# TRISTATE_BANK.net
KiCad netlist of a schematic drawn in Altium Designer
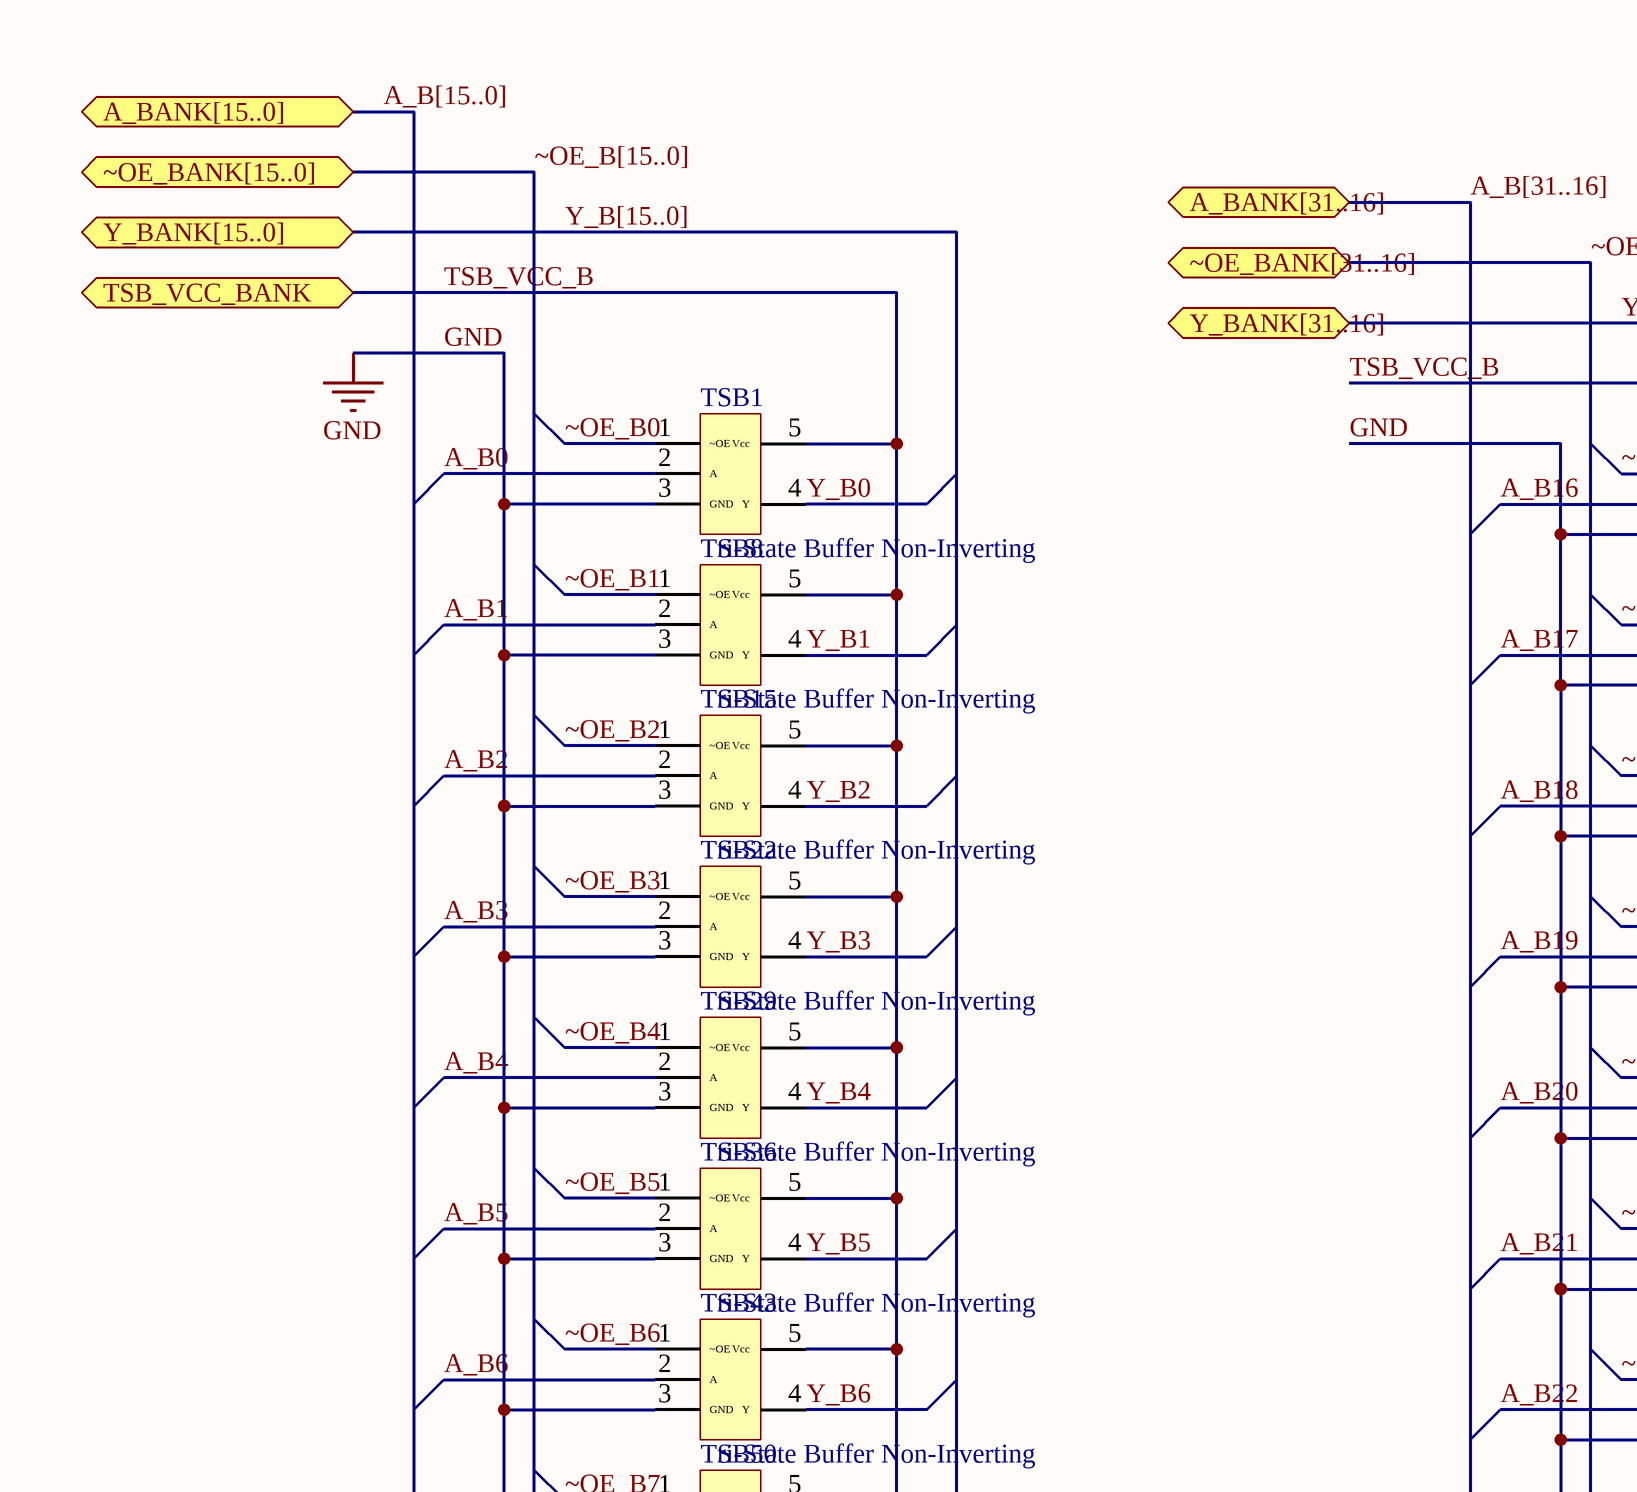
[diagram p0: TRISTATE_BANK.SchDoc, top column 1 of 5]
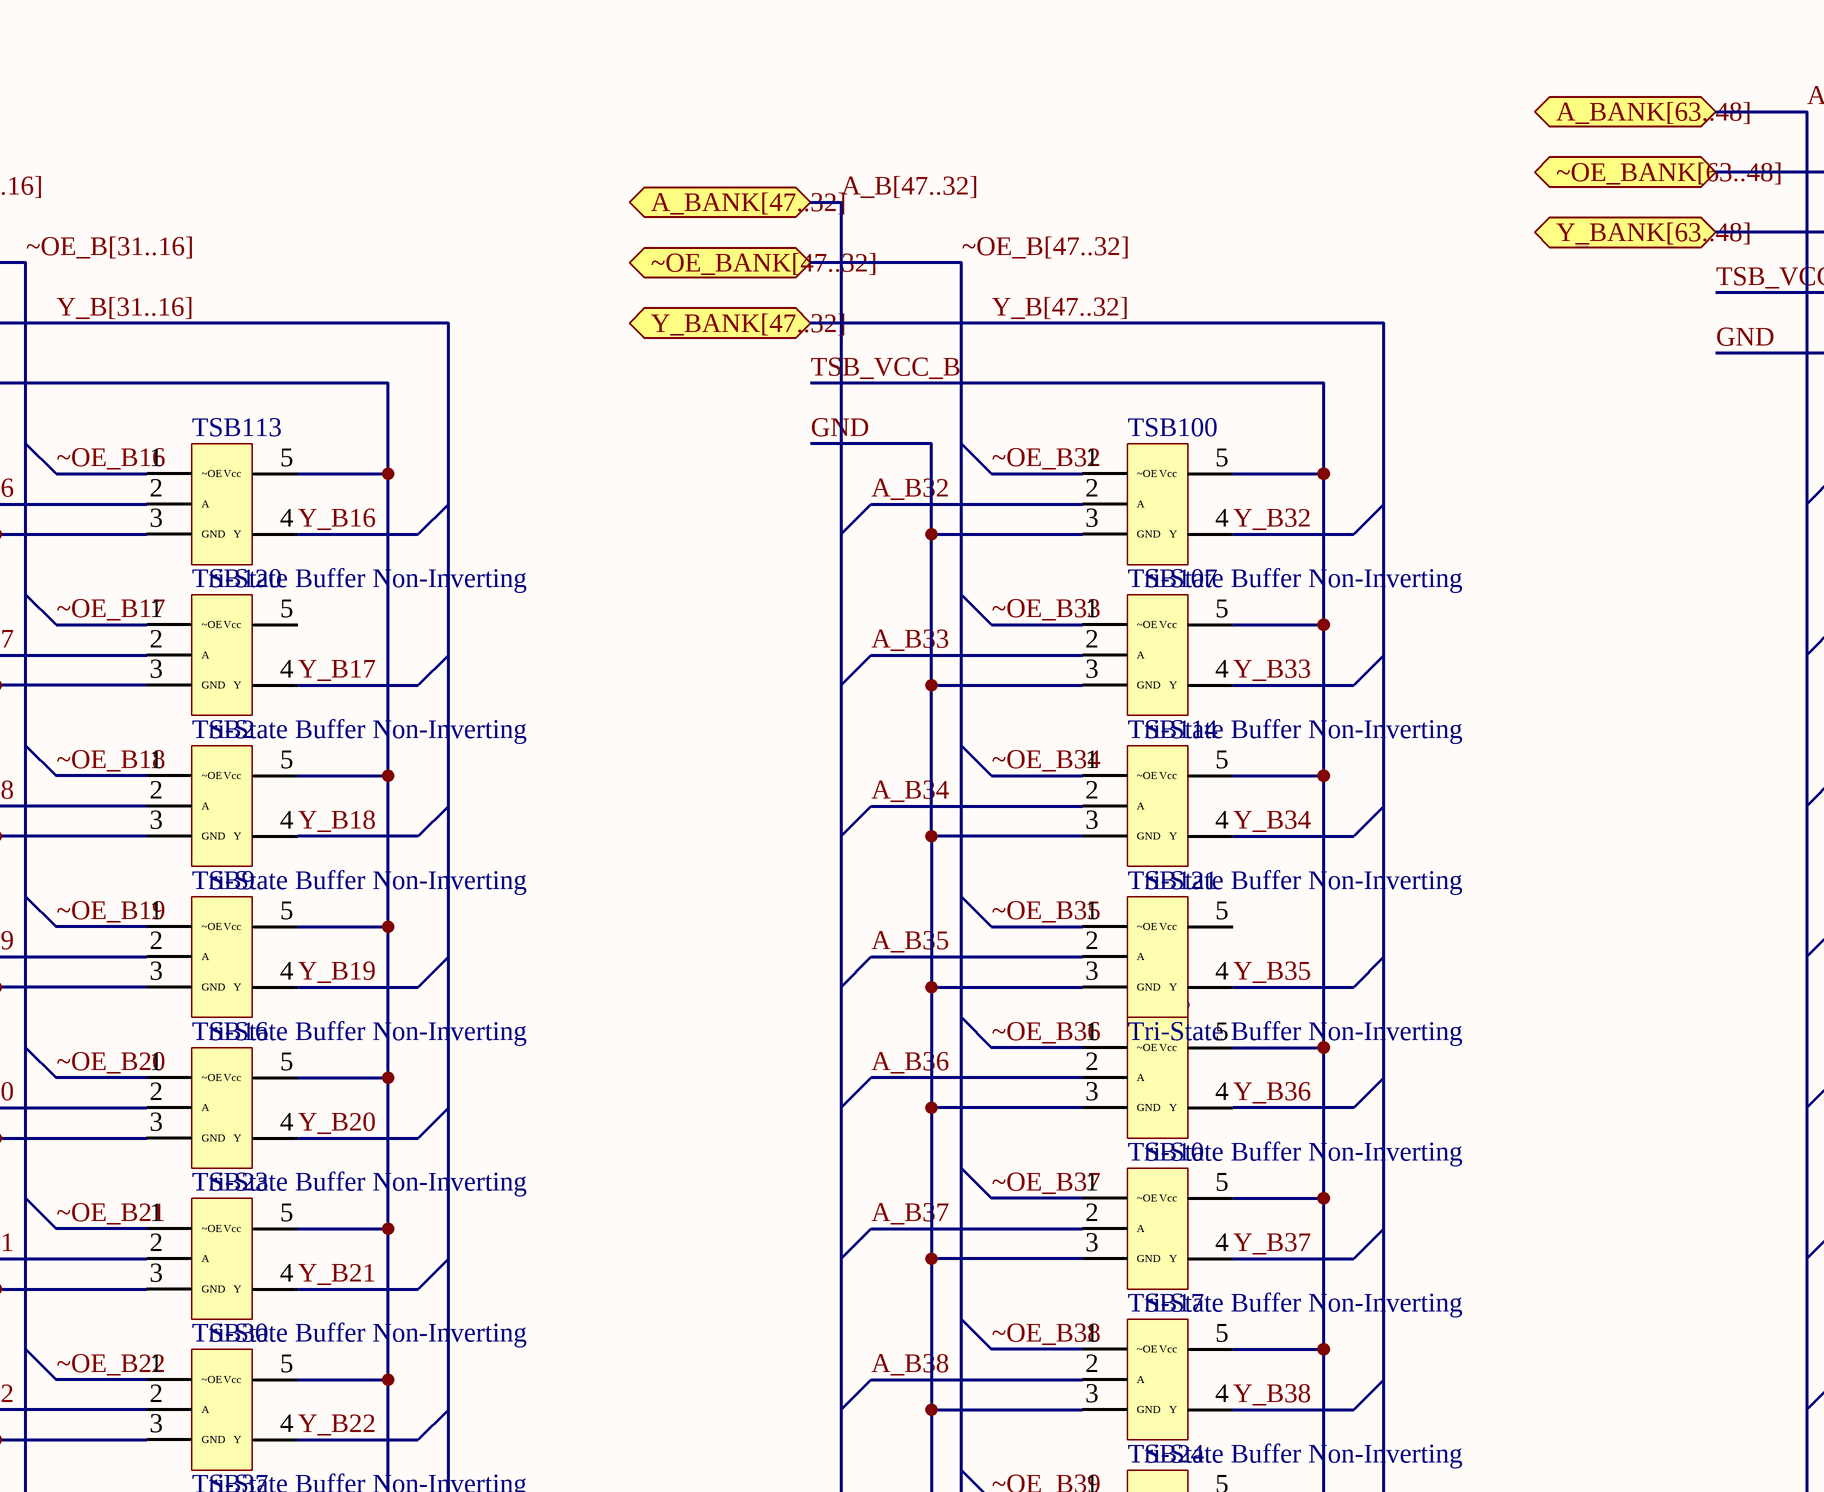
[diagram p1: TRISTATE_BANK.SchDoc, top column 2 of 5]
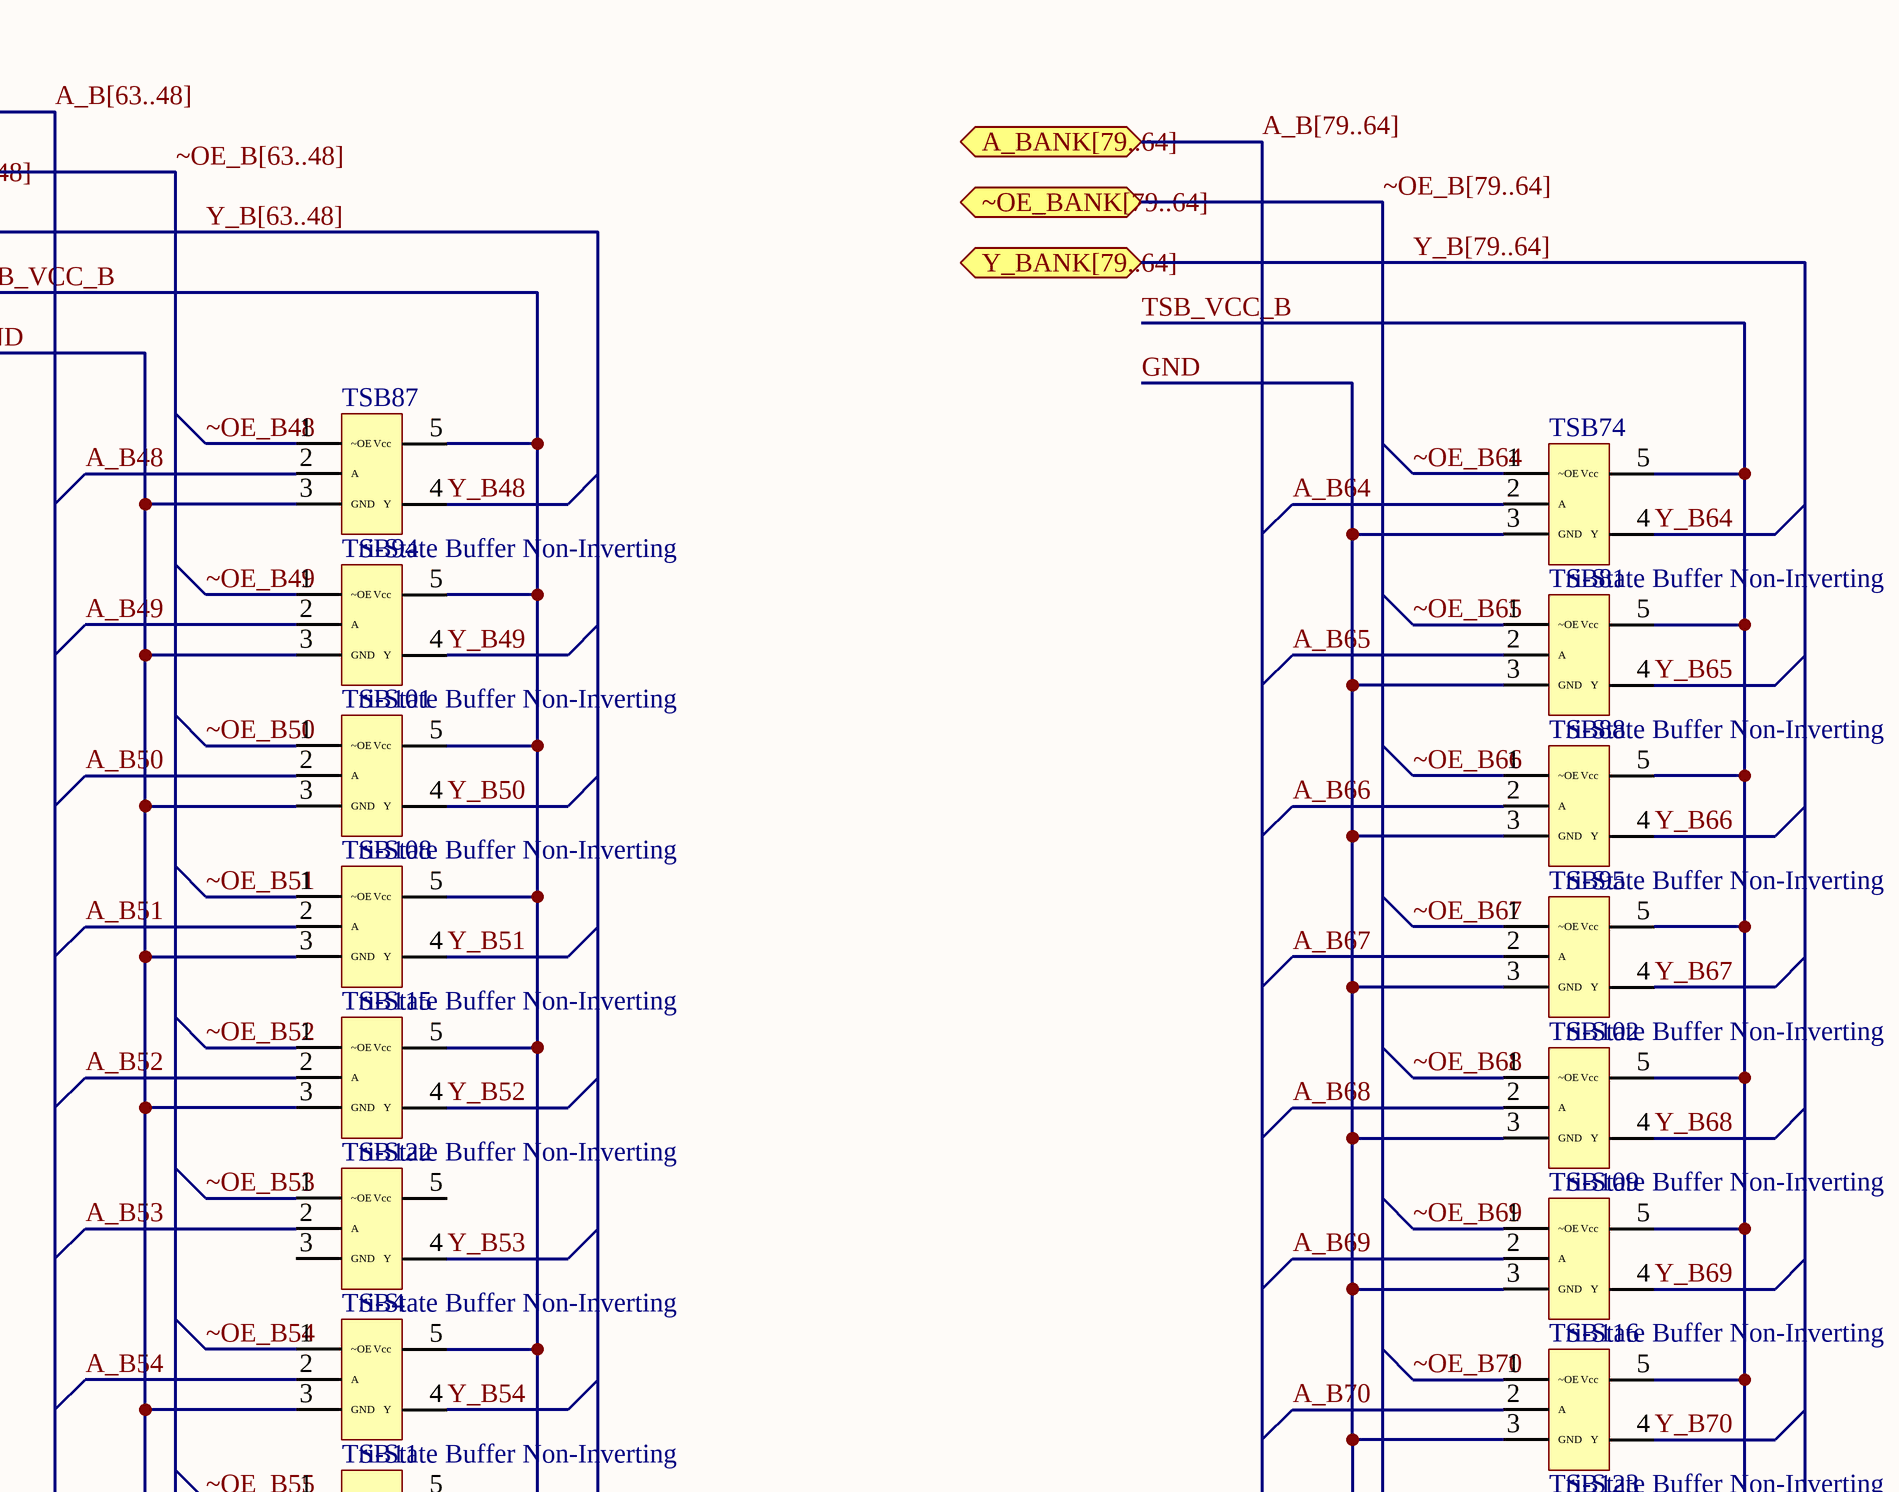
[diagram p2: TRISTATE_BANK.SchDoc, top column 3 of 5]
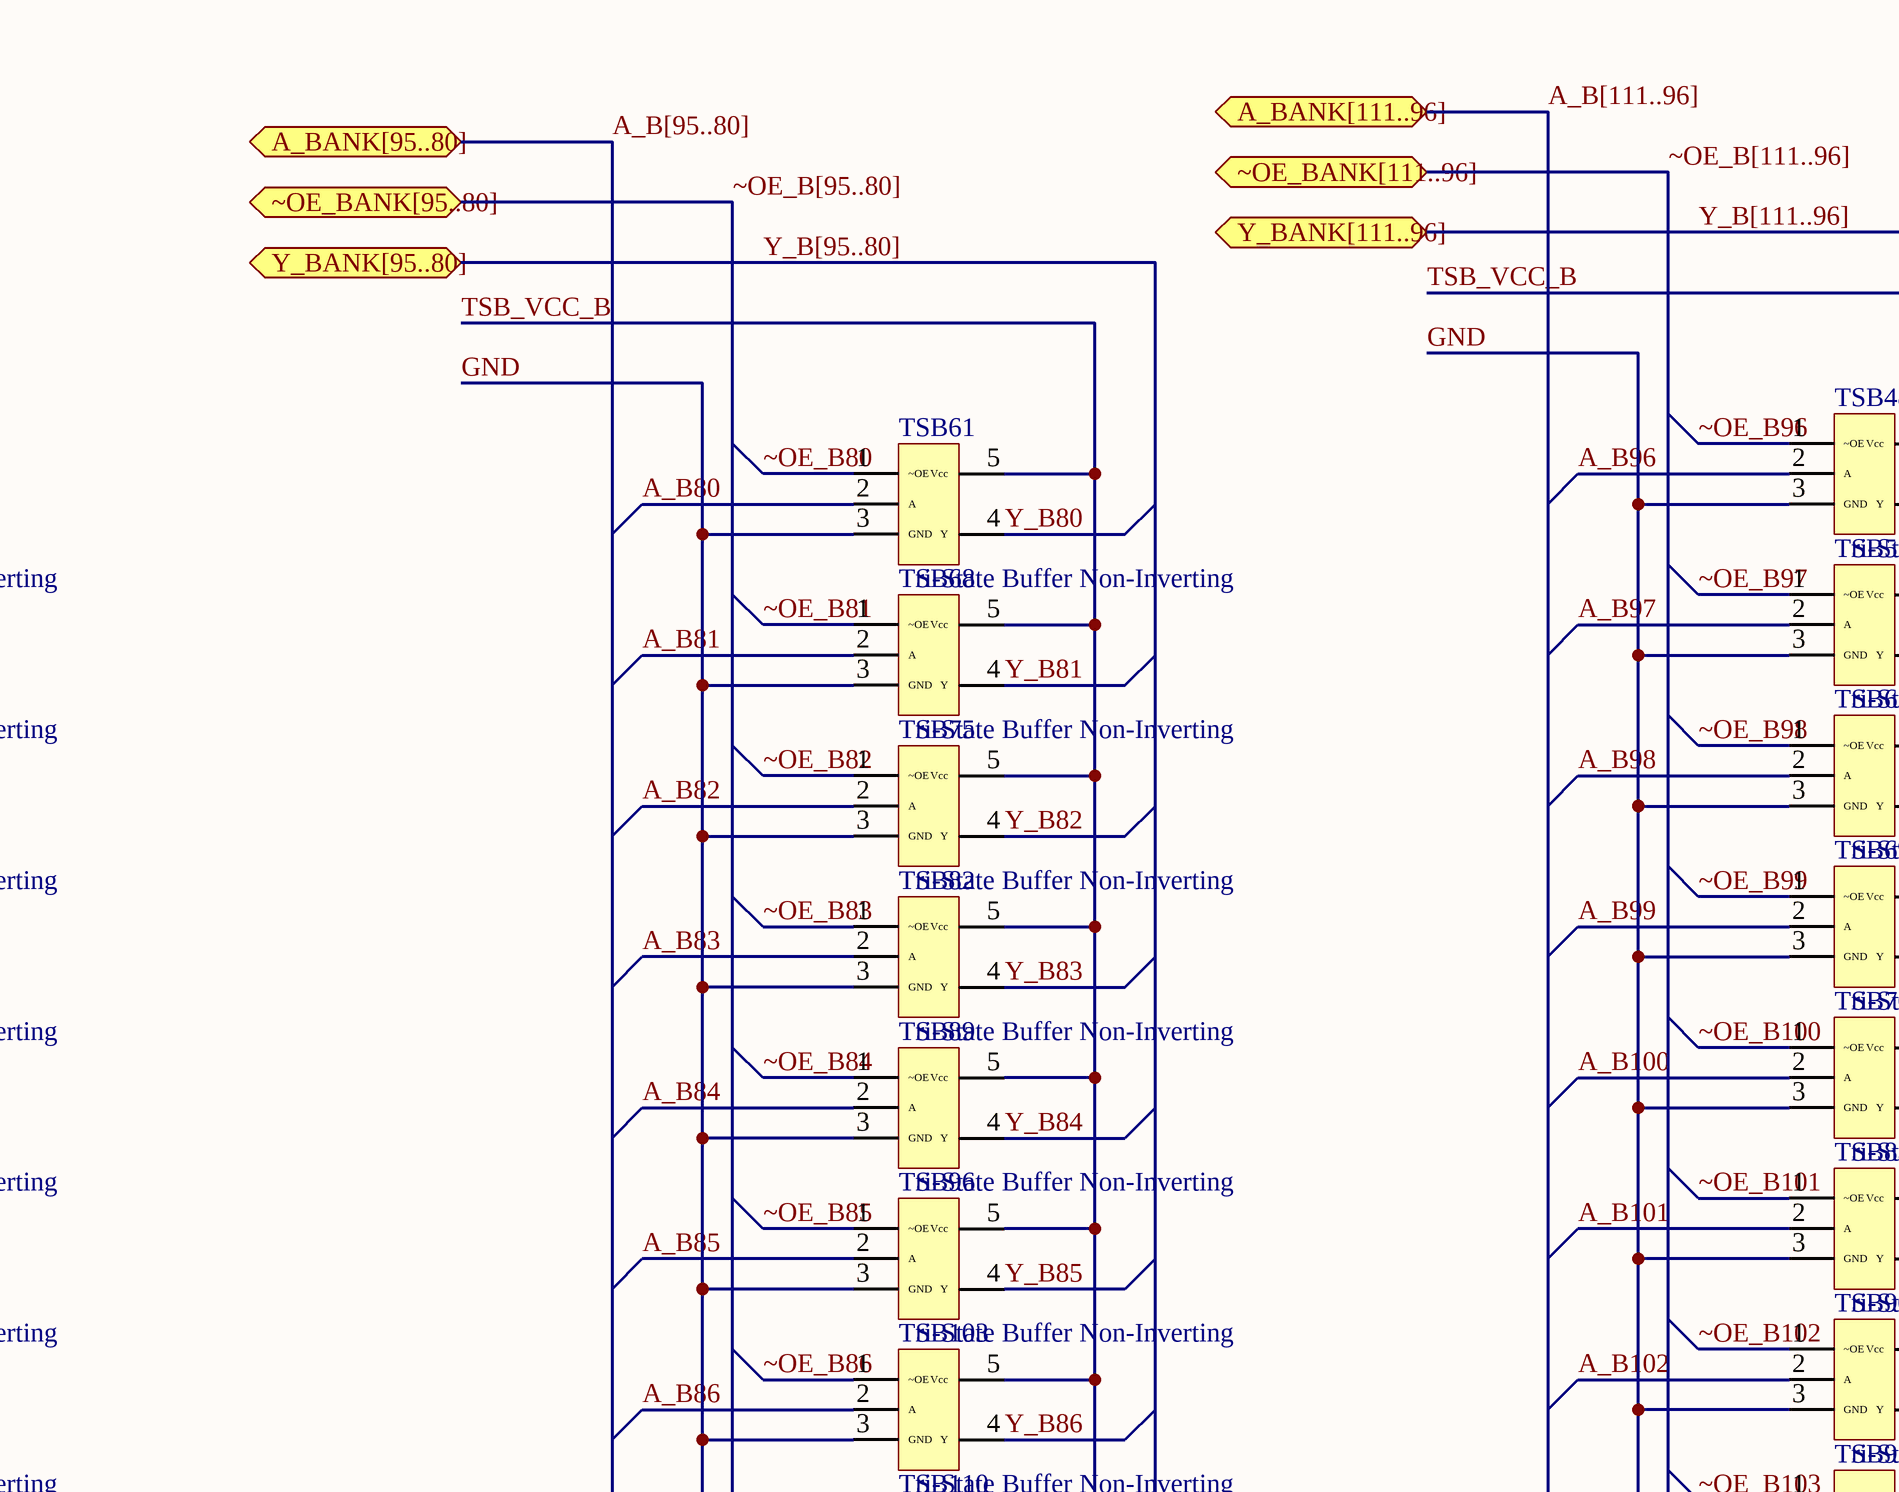
[diagram p3: TRISTATE_BANK.SchDoc, top column 4 of 5]
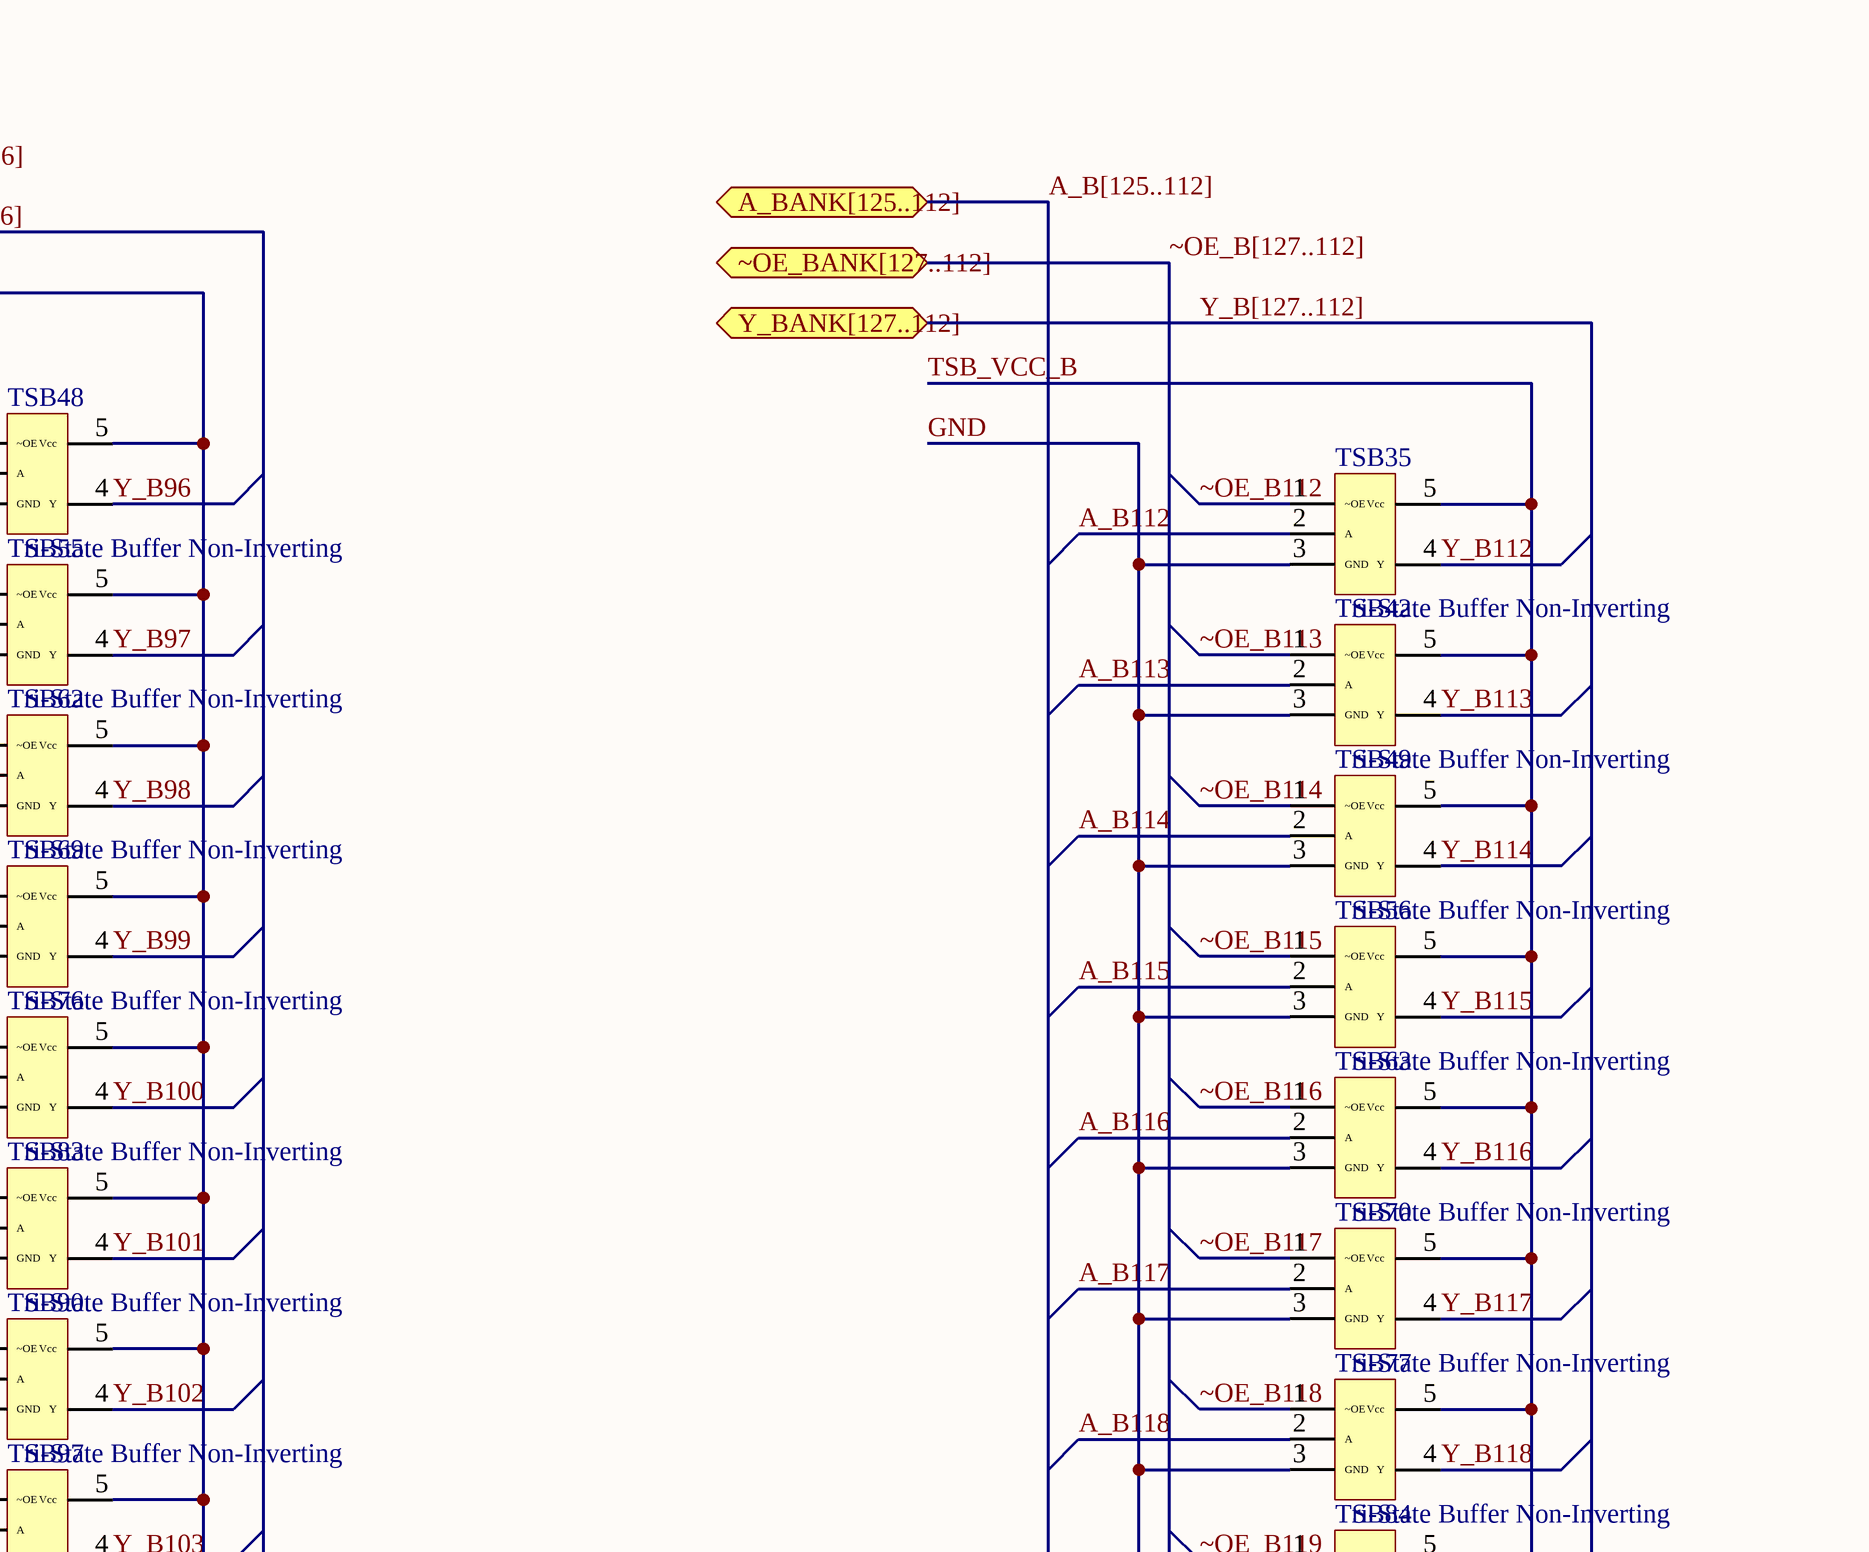
[diagram p4: TRISTATE_BANK.SchDoc, top column 5 of 5]
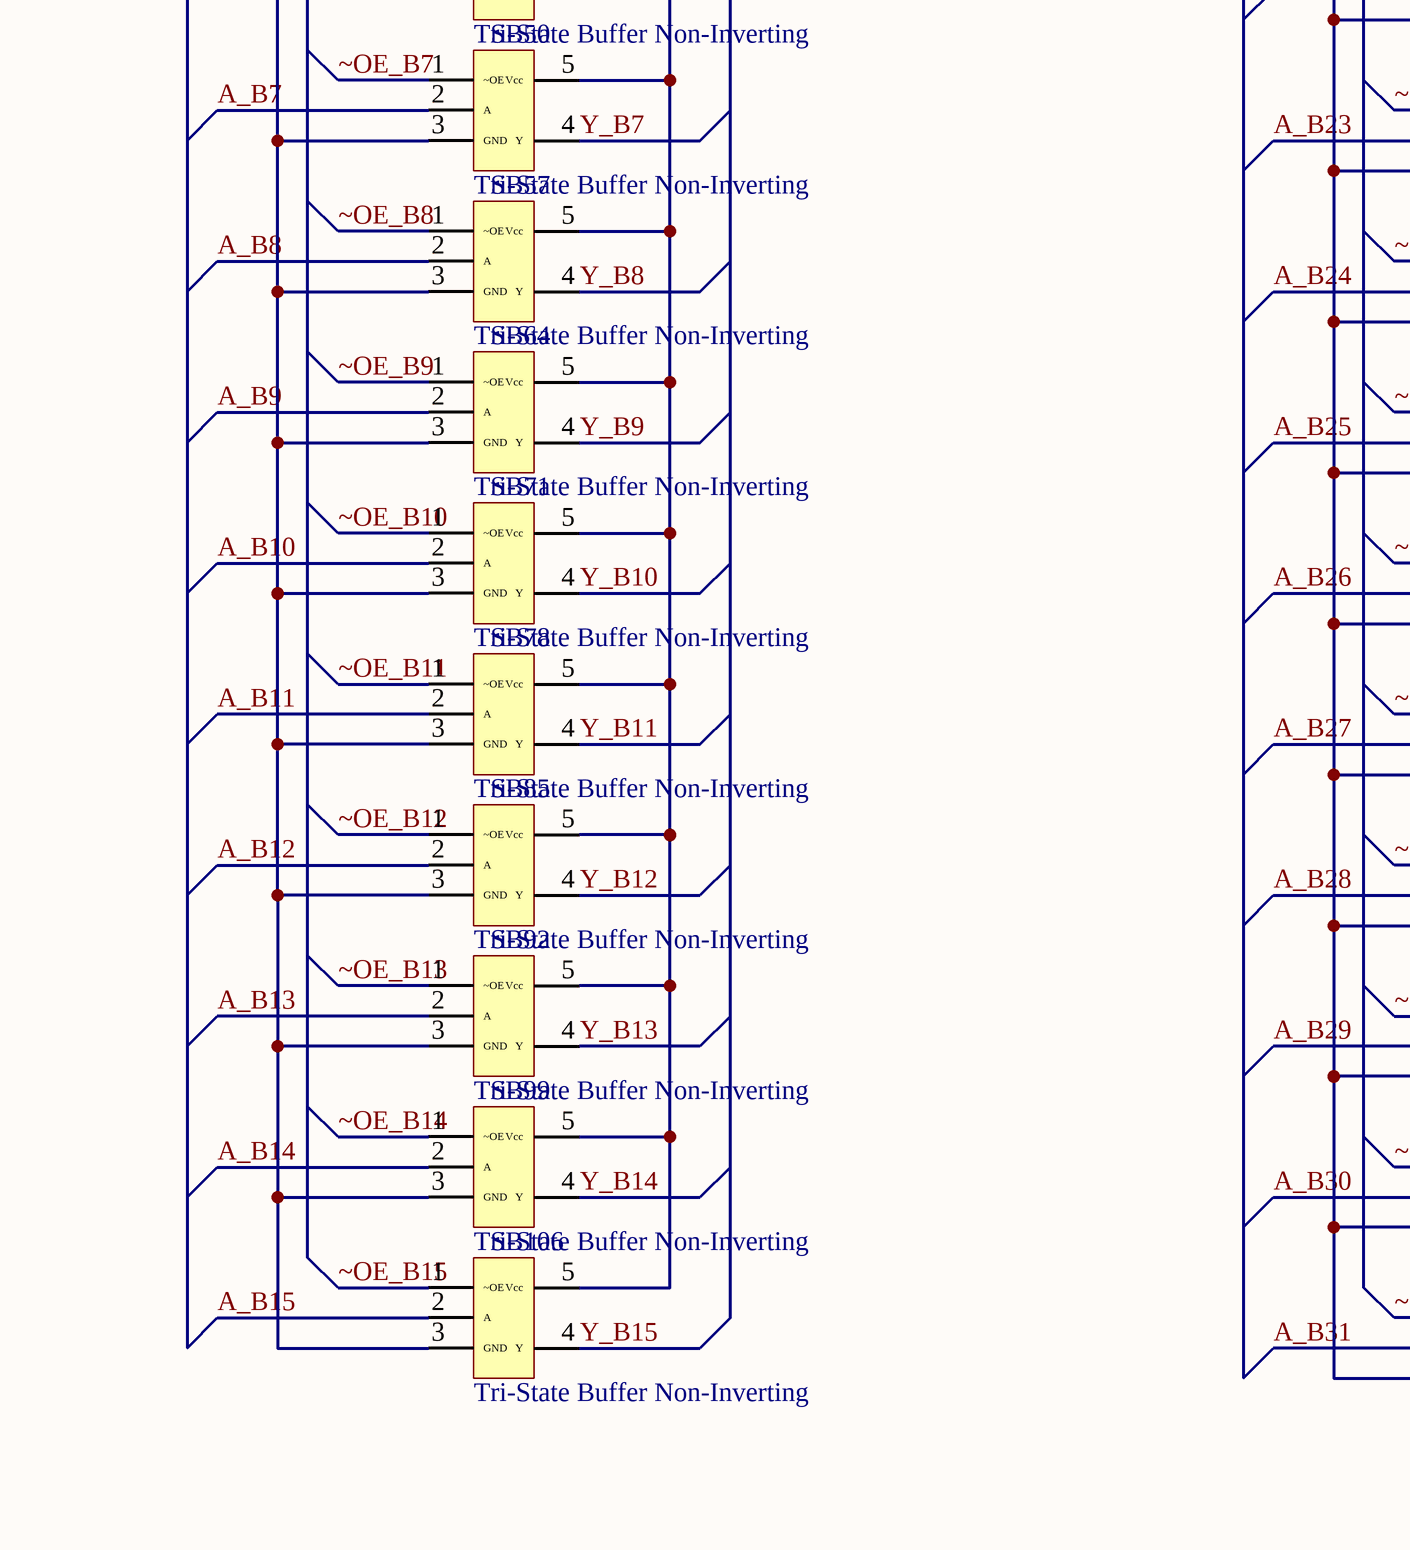
[diagram p5: TRISTATE_BANK.SchDoc, bottom column 1 of 5]
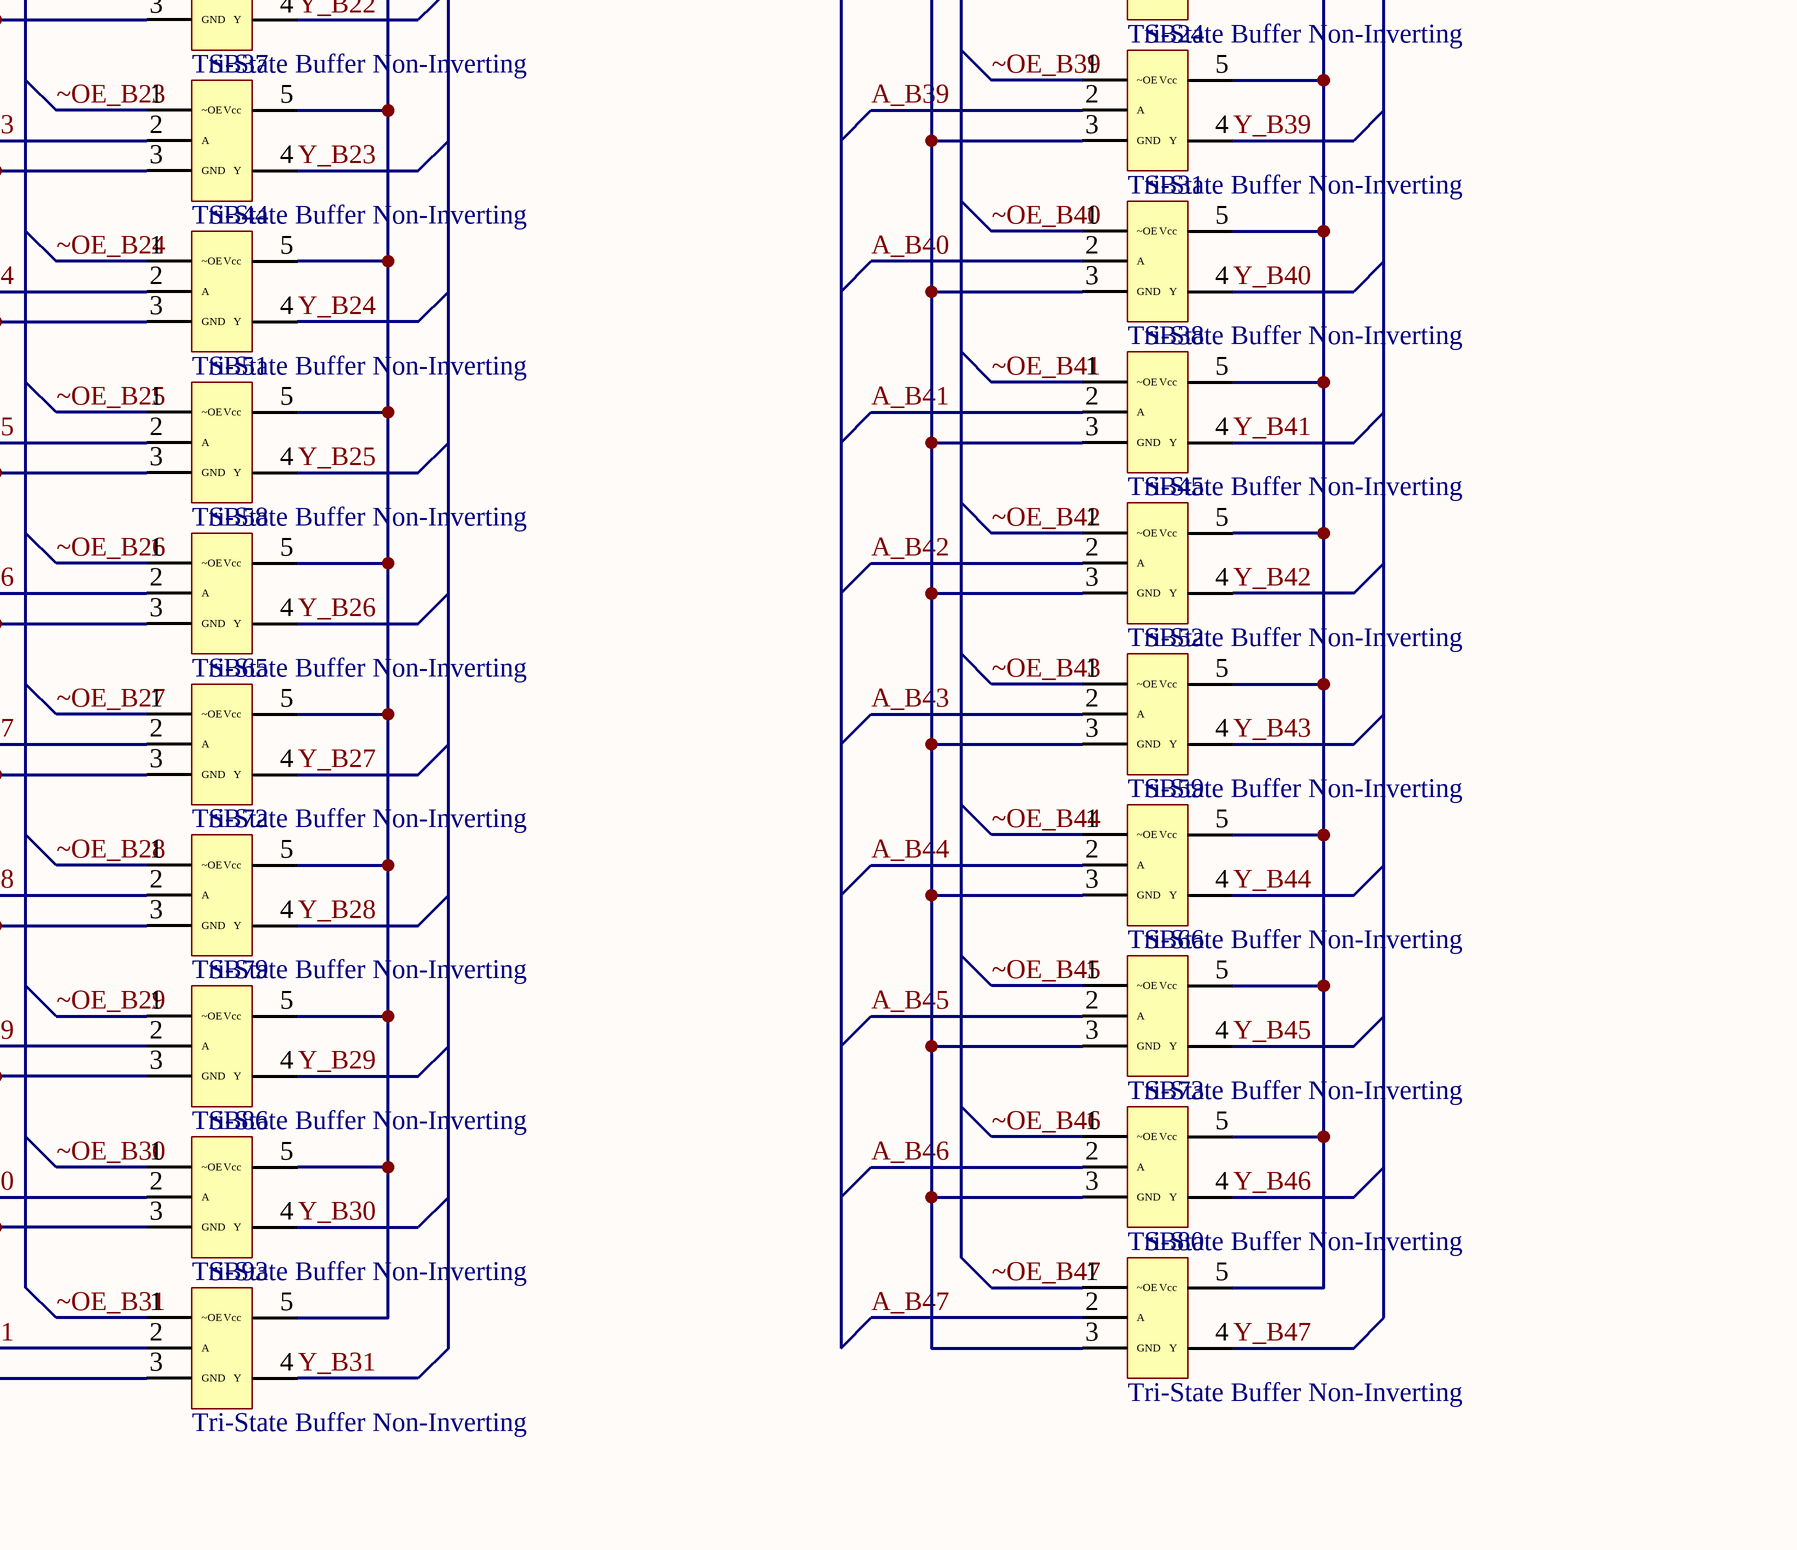
[diagram p6: TRISTATE_BANK.SchDoc, bottom column 2 of 5]
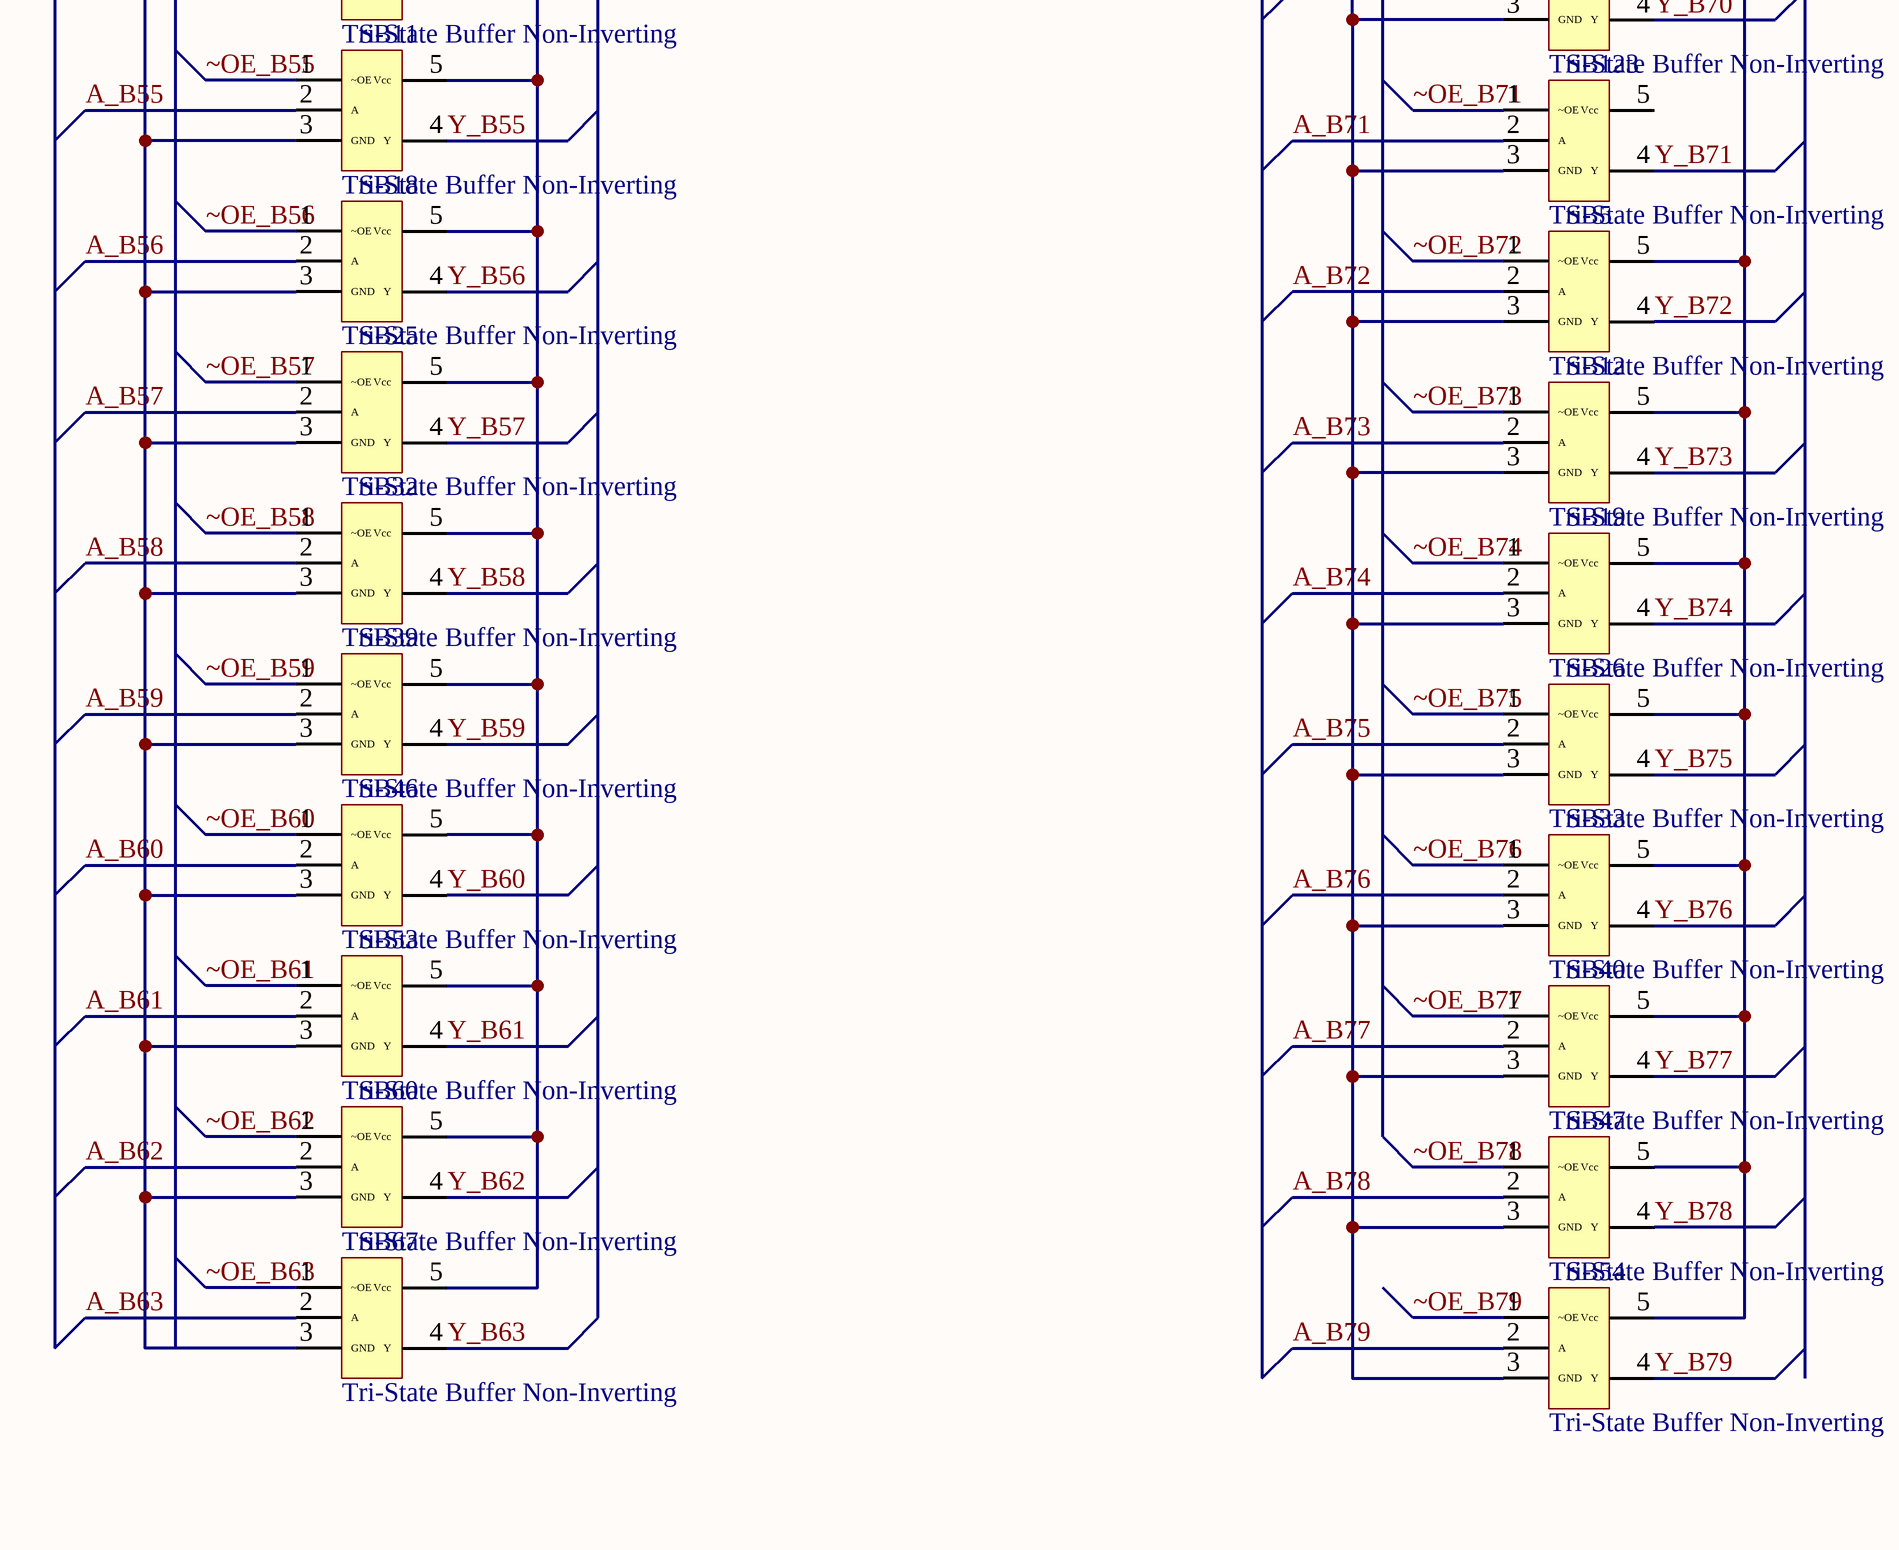
[diagram p7: TRISTATE_BANK.SchDoc, bottom column 3 of 5]
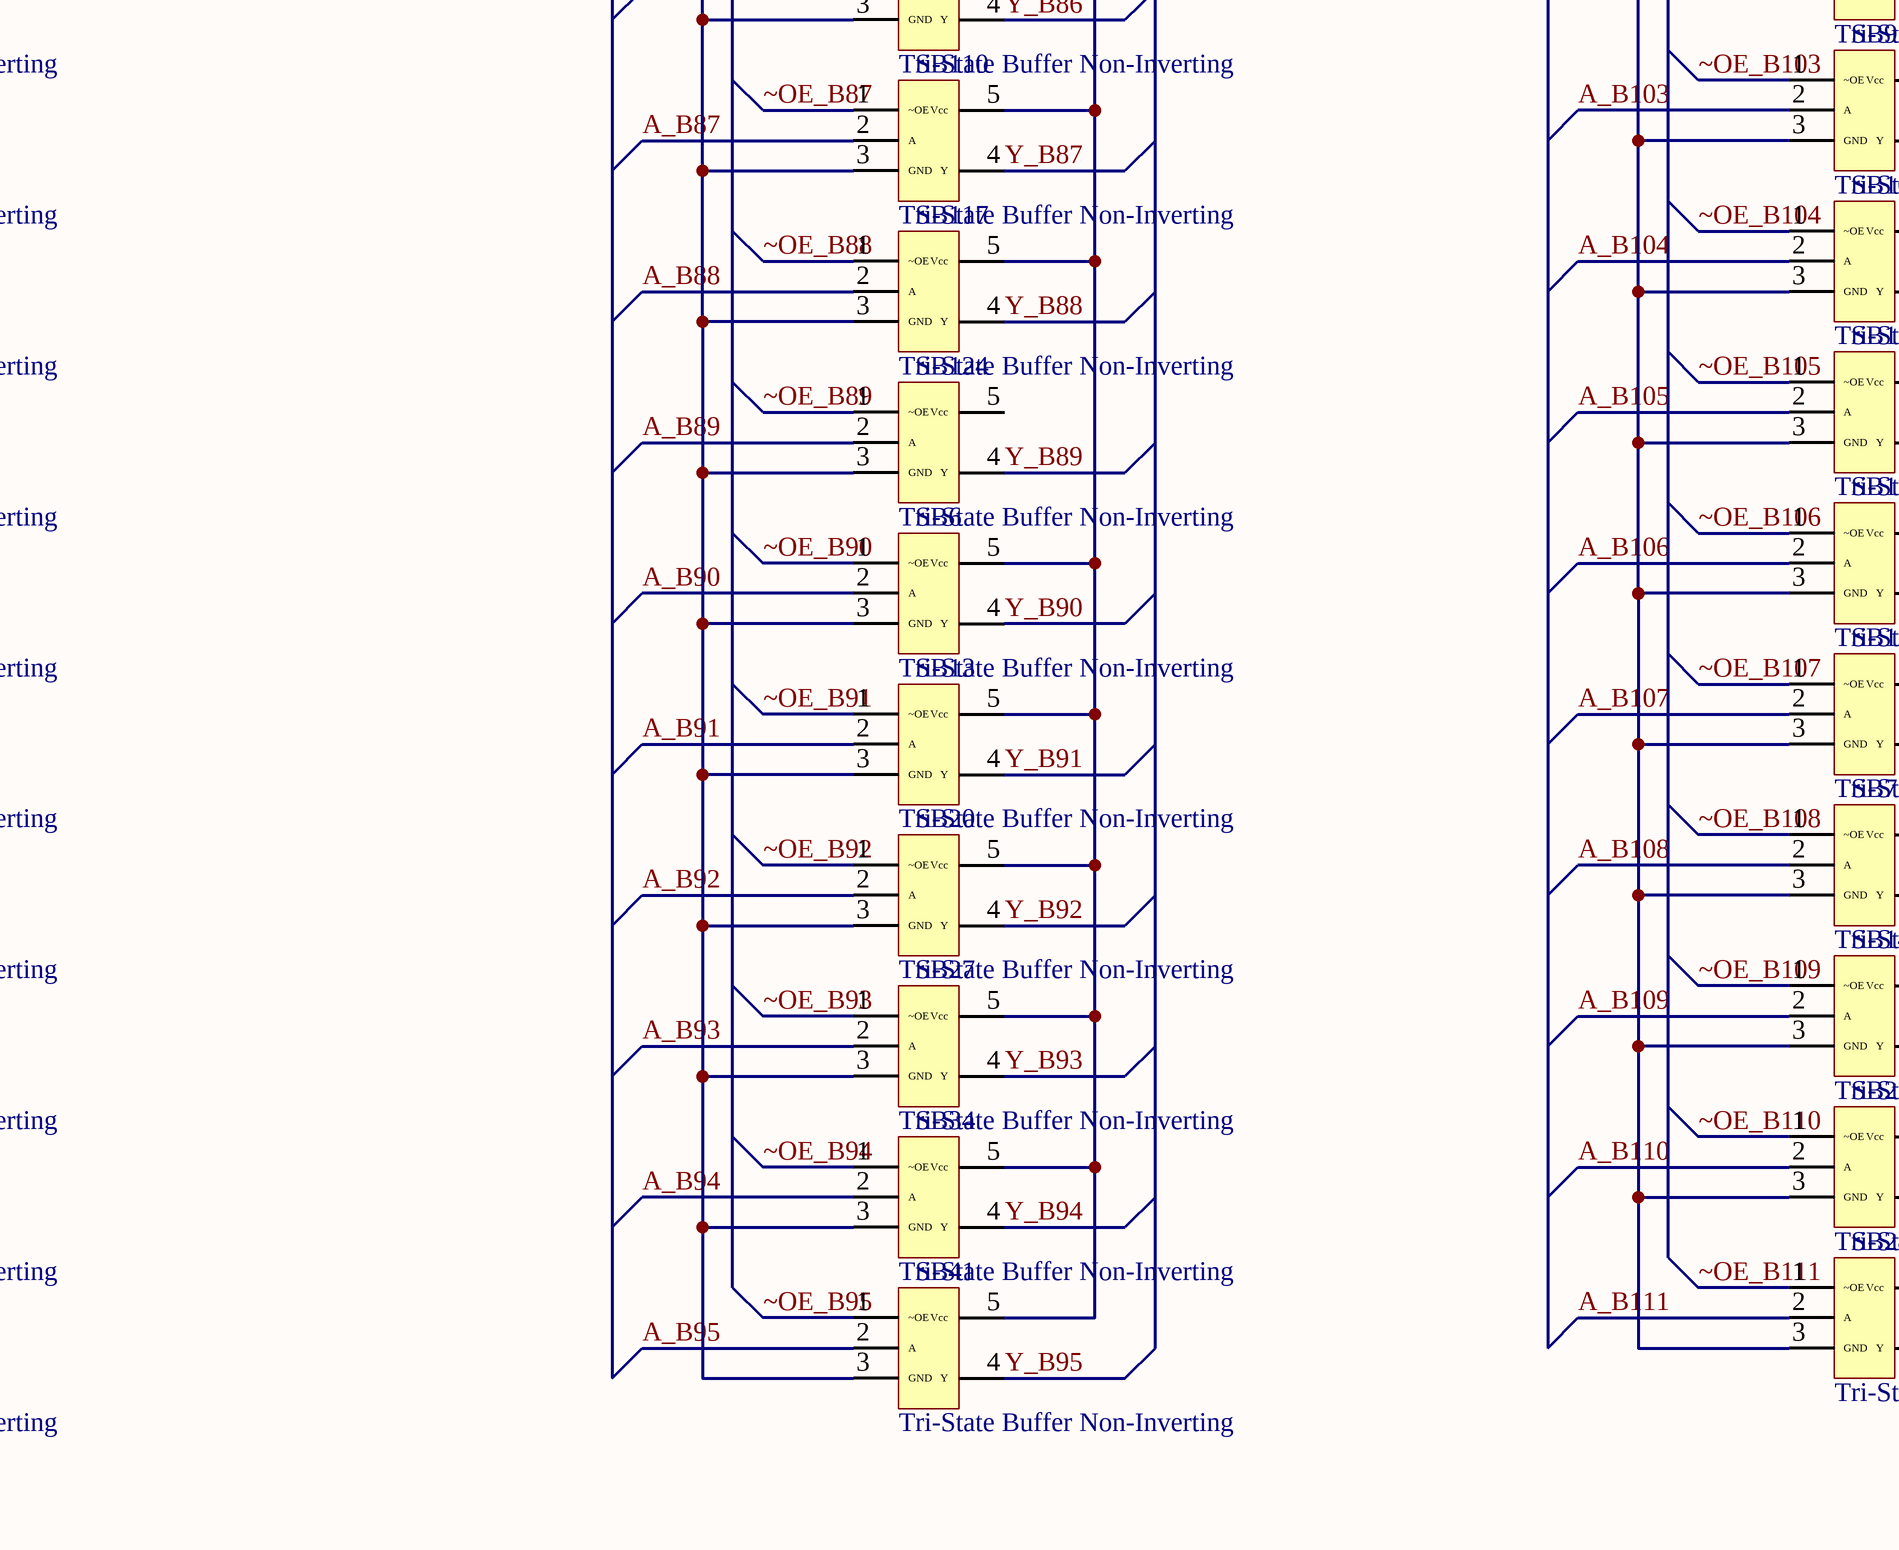
[diagram p8: TRISTATE_BANK.SchDoc, bottom column 4 of 5]
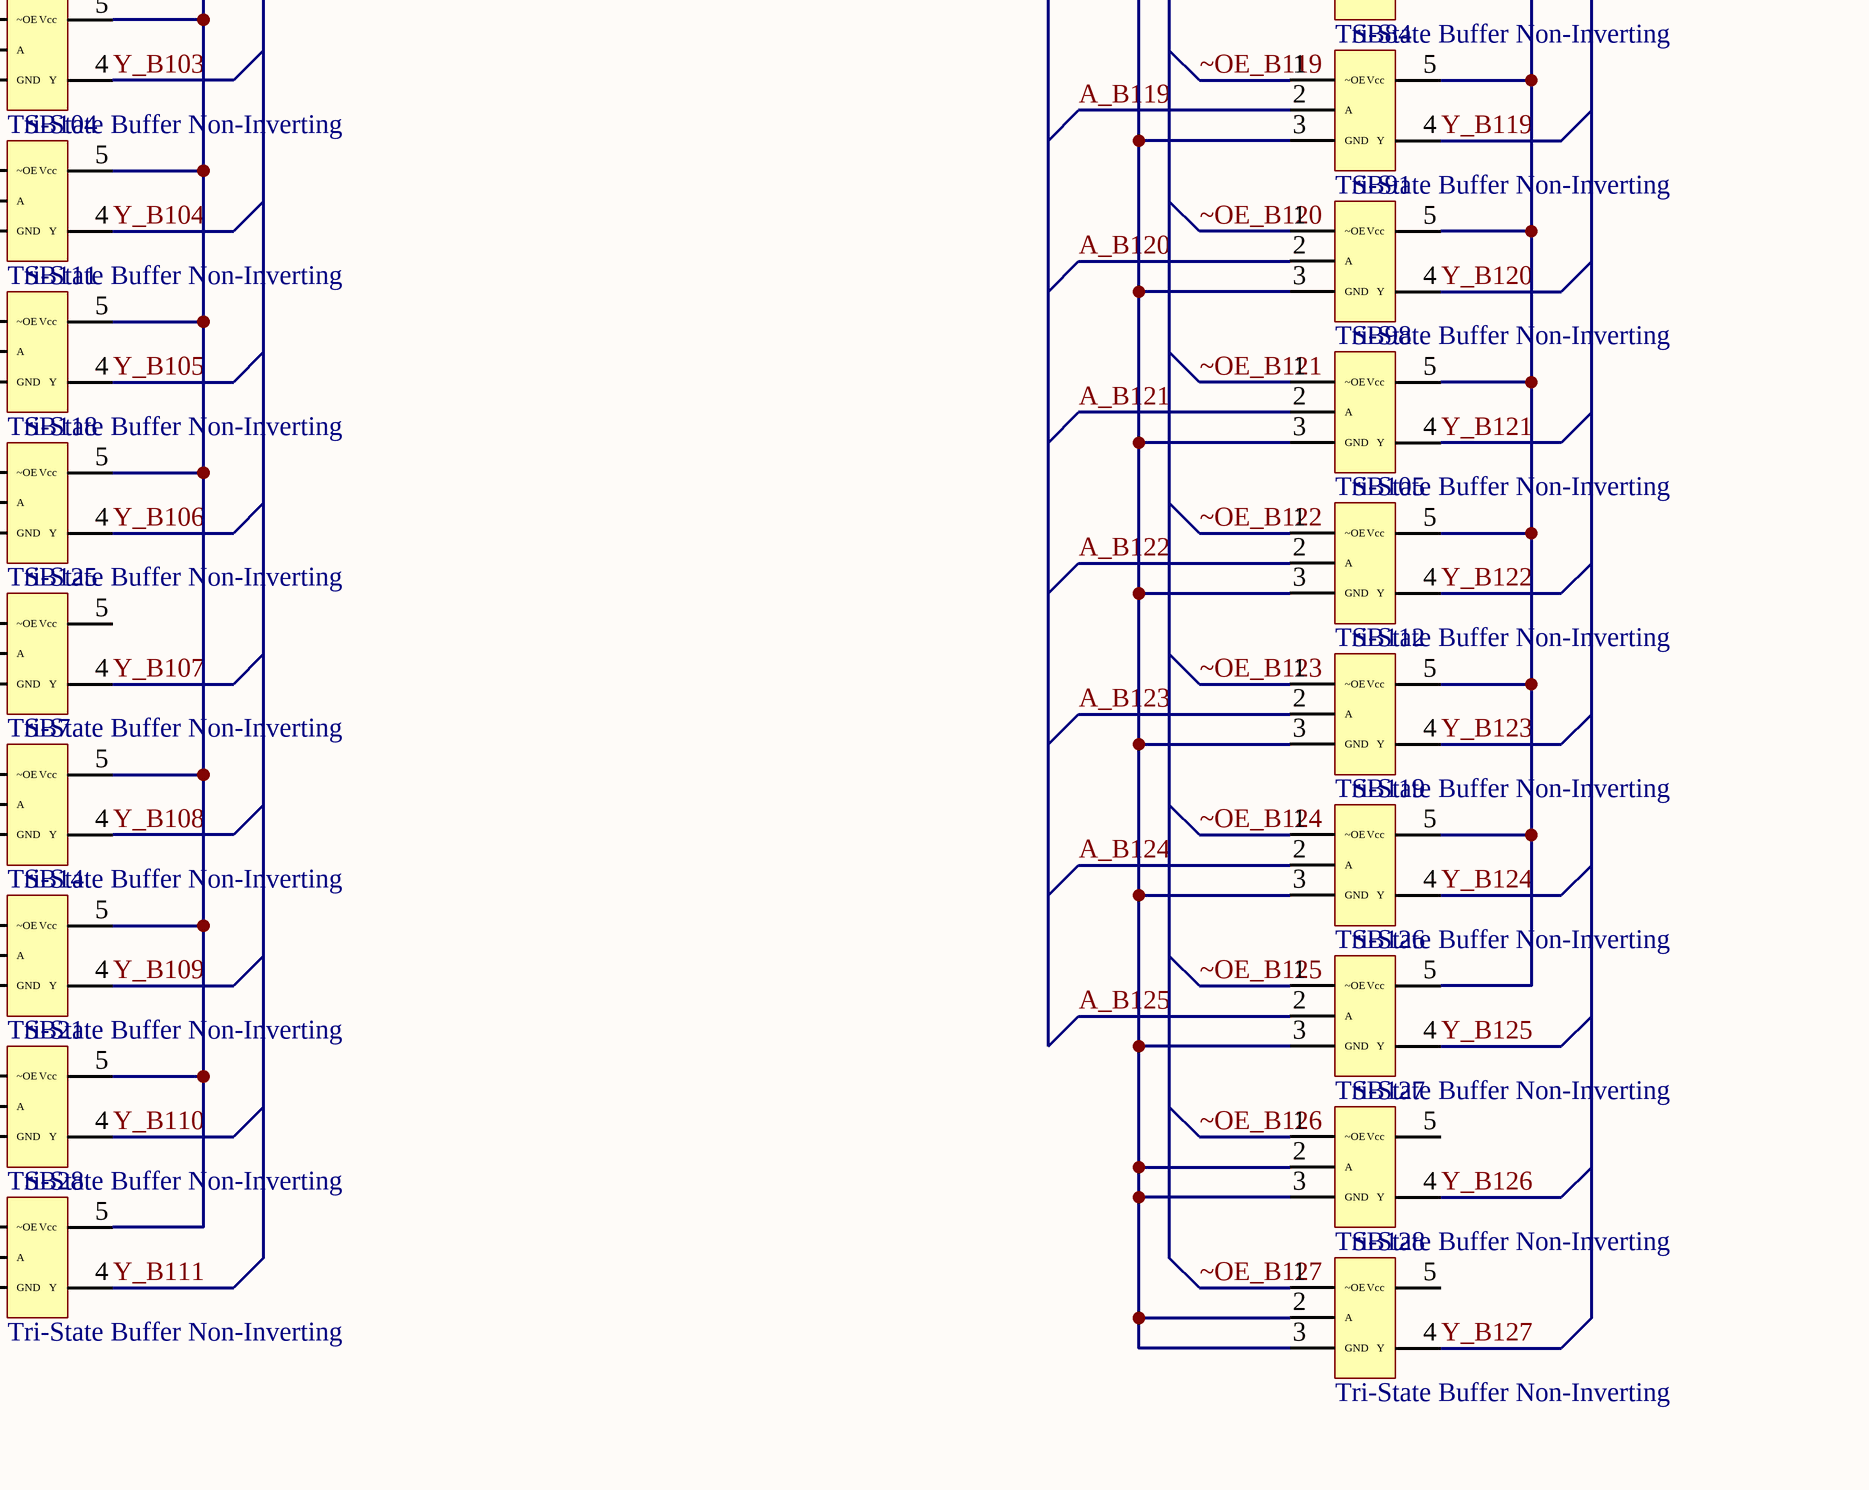
[diagram p9: TRISTATE_BANK.SchDoc, bottom column 5 of 5]

(export (version "E")
  (design (tool "Eeschema 10.0.6"))
  (components
    (comp (ref "TSB1")
      (value "Tri-State Buffer Non-Inverting")
      (footprint "tri_state")
      (description "IC BUFF DVR TRI-ST N-INV 5TSSOP")
      (fields
        (field (name "MANUFACTURER") "NXP Semiconductors")
        (field (name "MANUFACTURER PART NUMBER") "74LVC1G125GW,125")
      )
      (libsource (lib "BBB_Board") (part "Tri-State Buffer Non-Inverting"))
    )
    (comp (ref "TSB2")
      (value "Tri-State Buffer Non-Inverting")
      (footprint "tri_state")
      (description "IC BUFF DVR TRI-ST N-INV 5TSSOP")
      (fields
        (field (name "MANUFACTURER") "NXP Semiconductors")
        (field (name "MANUFACTURER PART NUMBER") "74LVC1G125GW,125")
      )
      (libsource (lib "BBB_Board") (part "Tri-State Buffer Non-Inverting"))
    )
    (comp (ref "TSB3")
      (value "Tri-State Buffer Non-Inverting")
      (footprint "tri_state")
      (description "IC BUFF DVR TRI-ST N-INV 5TSSOP")
      (fields
        (field (name "MANUFACTURER") "NXP Semiconductors")
        (field (name "MANUFACTURER PART NUMBER") "74LVC1G125GW,125")
      )
      (libsource (lib "BBB_Board") (part "Tri-State Buffer Non-Inverting"))
    )
    (comp (ref "TSB4")
      (value "Tri-State Buffer Non-Inverting")
      (footprint "tri_state")
      (description "IC BUFF DVR TRI-ST N-INV 5TSSOP")
      (fields
        (field (name "MANUFACTURER") "NXP Semiconductors")
        (field (name "MANUFACTURER PART NUMBER") "74LVC1G125GW,125")
      )
      (libsource (lib "BBB_Board") (part "Tri-State Buffer Non-Inverting"))
    )
    (comp (ref "TSB5")
      (value "Tri-State Buffer Non-Inverting")
      (footprint "tri_state")
      (description "IC BUFF DVR TRI-ST N-INV 5TSSOP")
      (fields
        (field (name "MANUFACTURER") "NXP Semiconductors")
        (field (name "MANUFACTURER PART NUMBER") "74LVC1G125GW,125")
      )
      (libsource (lib "BBB_Board") (part "Tri-State Buffer Non-Inverting"))
    )
    (comp (ref "TSB6")
      (value "Tri-State Buffer Non-Inverting")
      (footprint "tri_state")
      (description "IC BUFF DVR TRI-ST N-INV 5TSSOP")
      (fields
        (field (name "MANUFACTURER") "NXP Semiconductors")
        (field (name "MANUFACTURER PART NUMBER") "74LVC1G125GW,125")
      )
      (libsource (lib "BBB_Board") (part "Tri-State Buffer Non-Inverting"))
    )
    (comp (ref "TSB7")
      (value "Tri-State Buffer Non-Inverting")
      (footprint "tri_state")
      (description "IC BUFF DVR TRI-ST N-INV 5TSSOP")
      (fields
        (field (name "MANUFACTURER") "NXP Semiconductors")
        (field (name "MANUFACTURER PART NUMBER") "74LVC1G125GW,125")
      )
      (libsource (lib "BBB_Board") (part "Tri-State Buffer Non-Inverting"))
    )
    (comp (ref "TSB8")
      (value "Tri-State Buffer Non-Inverting")
      (footprint "tri_state")
      (description "IC BUFF DVR TRI-ST N-INV 5TSSOP")
      (fields
        (field (name "MANUFACTURER") "NXP Semiconductors")
        (field (name "MANUFACTURER PART NUMBER") "74LVC1G125GW,125")
      )
      (libsource (lib "BBB_Board") (part "Tri-State Buffer Non-Inverting"))
    )
    (comp (ref "TSB9")
      (value "Tri-State Buffer Non-Inverting")
      (footprint "tri_state")
      (description "IC BUFF DVR TRI-ST N-INV 5TSSOP")
      (fields
        (field (name "MANUFACTURER") "NXP Semiconductors")
        (field (name "MANUFACTURER PART NUMBER") "74LVC1G125GW,125")
      )
      (libsource (lib "BBB_Board") (part "Tri-State Buffer Non-Inverting"))
    )
    (comp (ref "TSB10")
      (value "Tri-State Buffer Non-Inverting")
      (footprint "tri_state")
      (description "IC BUFF DVR TRI-ST N-INV 5TSSOP")
      (fields
        (field (name "MANUFACTURER") "NXP Semiconductors")
        (field (name "MANUFACTURER PART NUMBER") "74LVC1G125GW,125")
      )
      (libsource (lib "BBB_Board") (part "Tri-State Buffer Non-Inverting"))
    )
    (comp (ref "TSB11")
      (value "Tri-State Buffer Non-Inverting")
      (footprint "tri_state")
      (description "IC BUFF DVR TRI-ST N-INV 5TSSOP")
      (fields
        (field (name "MANUFACTURER") "NXP Semiconductors")
        (field (name "MANUFACTURER PART NUMBER") "74LVC1G125GW,125")
      )
      (libsource (lib "BBB_Board") (part "Tri-State Buffer Non-Inverting"))
    )
    (comp (ref "TSB12")
      (value "Tri-State Buffer Non-Inverting")
      (footprint "tri_state")
      (description "IC BUFF DVR TRI-ST N-INV 5TSSOP")
      (fields
        (field (name "MANUFACTURER") "NXP Semiconductors")
        (field (name "MANUFACTURER PART NUMBER") "74LVC1G125GW,125")
      )
      (libsource (lib "BBB_Board") (part "Tri-State Buffer Non-Inverting"))
    )
    (comp (ref "TSB13")
      (value "Tri-State Buffer Non-Inverting")
      (footprint "tri_state")
      (description "IC BUFF DVR TRI-ST N-INV 5TSSOP")
      (fields
        (field (name "MANUFACTURER") "NXP Semiconductors")
        (field (name "MANUFACTURER PART NUMBER") "74LVC1G125GW,125")
      )
      (libsource (lib "BBB_Board") (part "Tri-State Buffer Non-Inverting"))
    )
    (comp (ref "TSB14")
      (value "Tri-State Buffer Non-Inverting")
      (footprint "tri_state")
      (description "IC BUFF DVR TRI-ST N-INV 5TSSOP")
      (fields
        (field (name "MANUFACTURER") "NXP Semiconductors")
        (field (name "MANUFACTURER PART NUMBER") "74LVC1G125GW,125")
      )
      (libsource (lib "BBB_Board") (part "Tri-State Buffer Non-Inverting"))
    )
    (comp (ref "TSB15")
      (value "Tri-State Buffer Non-Inverting")
      (footprint "tri_state")
      (description "IC BUFF DVR TRI-ST N-INV 5TSSOP")
      (fields
        (field (name "MANUFACTURER") "NXP Semiconductors")
        (field (name "MANUFACTURER PART NUMBER") "74LVC1G125GW,125")
      )
      (libsource (lib "BBB_Board") (part "Tri-State Buffer Non-Inverting"))
    )
    (comp (ref "TSB16")
      (value "Tri-State Buffer Non-Inverting")
      (footprint "tri_state")
      (description "IC BUFF DVR TRI-ST N-INV 5TSSOP")
      (fields
        (field (name "MANUFACTURER") "NXP Semiconductors")
        (field (name "MANUFACTURER PART NUMBER") "74LVC1G125GW,125")
      )
      (libsource (lib "BBB_Board") (part "Tri-State Buffer Non-Inverting"))
    )
    (comp (ref "TSB17")
      (value "Tri-State Buffer Non-Inverting")
      (footprint "tri_state")
      (description "IC BUFF DVR TRI-ST N-INV 5TSSOP")
      (fields
        (field (name "MANUFACTURER") "NXP Semiconductors")
        (field (name "MANUFACTURER PART NUMBER") "74LVC1G125GW,125")
      )
      (libsource (lib "BBB_Board") (part "Tri-State Buffer Non-Inverting"))
    )
    (comp (ref "TSB18")
      (value "Tri-State Buffer Non-Inverting")
      (footprint "tri_state")
      (description "IC BUFF DVR TRI-ST N-INV 5TSSOP")
      (fields
        (field (name "MANUFACTURER") "NXP Semiconductors")
        (field (name "MANUFACTURER PART NUMBER") "74LVC1G125GW,125")
      )
      (libsource (lib "BBB_Board") (part "Tri-State Buffer Non-Inverting"))
    )
    (comp (ref "TSB19")
      (value "Tri-State Buffer Non-Inverting")
      (footprint "tri_state")
      (description "IC BUFF DVR TRI-ST N-INV 5TSSOP")
      (fields
        (field (name "MANUFACTURER") "NXP Semiconductors")
        (field (name "MANUFACTURER PART NUMBER") "74LVC1G125GW,125")
      )
      (libsource (lib "BBB_Board") (part "Tri-State Buffer Non-Inverting"))
    )
    (comp (ref "TSB20")
      (value "Tri-State Buffer Non-Inverting")
      (footprint "tri_state")
      (description "IC BUFF DVR TRI-ST N-INV 5TSSOP")
      (fields
        (field (name "MANUFACTURER") "NXP Semiconductors")
        (field (name "MANUFACTURER PART NUMBER") "74LVC1G125GW,125")
      )
      (libsource (lib "BBB_Board") (part "Tri-State Buffer Non-Inverting"))
    )
    (comp (ref "TSB21")
      (value "Tri-State Buffer Non-Inverting")
      (footprint "tri_state")
      (description "IC BUFF DVR TRI-ST N-INV 5TSSOP")
      (fields
        (field (name "MANUFACTURER") "NXP Semiconductors")
        (field (name "MANUFACTURER PART NUMBER") "74LVC1G125GW,125")
      )
      (libsource (lib "BBB_Board") (part "Tri-State Buffer Non-Inverting"))
    )
    (comp (ref "TSB22")
      (value "Tri-State Buffer Non-Inverting")
      (footprint "tri_state")
      (description "IC BUFF DVR TRI-ST N-INV 5TSSOP")
      (fields
        (field (name "MANUFACTURER") "NXP Semiconductors")
        (field (name "MANUFACTURER PART NUMBER") "74LVC1G125GW,125")
      )
      (libsource (lib "BBB_Board") (part "Tri-State Buffer Non-Inverting"))
    )
    (comp (ref "TSB23")
      (value "Tri-State Buffer Non-Inverting")
      (footprint "tri_state")
      (description "IC BUFF DVR TRI-ST N-INV 5TSSOP")
      (fields
        (field (name "MANUFACTURER") "NXP Semiconductors")
        (field (name "MANUFACTURER PART NUMBER") "74LVC1G125GW,125")
      )
      (libsource (lib "BBB_Board") (part "Tri-State Buffer Non-Inverting"))
    )
    (comp (ref "TSB24")
      (value "Tri-State Buffer Non-Inverting")
      (footprint "tri_state")
      (description "IC BUFF DVR TRI-ST N-INV 5TSSOP")
      (fields
        (field (name "MANUFACTURER") "NXP Semiconductors")
        (field (name "MANUFACTURER PART NUMBER") "74LVC1G125GW,125")
      )
      (libsource (lib "BBB_Board") (part "Tri-State Buffer Non-Inverting"))
    )
    (comp (ref "TSB25")
      (value "Tri-State Buffer Non-Inverting")
      (footprint "tri_state")
      (description "IC BUFF DVR TRI-ST N-INV 5TSSOP")
      (fields
        (field (name "MANUFACTURER") "NXP Semiconductors")
        (field (name "MANUFACTURER PART NUMBER") "74LVC1G125GW,125")
      )
      (libsource (lib "BBB_Board") (part "Tri-State Buffer Non-Inverting"))
    )
    (comp (ref "TSB26")
      (value "Tri-State Buffer Non-Inverting")
      (footprint "tri_state")
      (description "IC BUFF DVR TRI-ST N-INV 5TSSOP")
      (fields
        (field (name "MANUFACTURER") "NXP Semiconductors")
        (field (name "MANUFACTURER PART NUMBER") "74LVC1G125GW,125")
      )
      (libsource (lib "BBB_Board") (part "Tri-State Buffer Non-Inverting"))
    )
    (comp (ref "TSB27")
      (value "Tri-State Buffer Non-Inverting")
      (footprint "tri_state")
      (description "IC BUFF DVR TRI-ST N-INV 5TSSOP")
      (fields
        (field (name "MANUFACTURER") "NXP Semiconductors")
        (field (name "MANUFACTURER PART NUMBER") "74LVC1G125GW,125")
      )
      (libsource (lib "BBB_Board") (part "Tri-State Buffer Non-Inverting"))
    )
    (comp (ref "TSB28")
      (value "Tri-State Buffer Non-Inverting")
      (footprint "tri_state")
      (description "IC BUFF DVR TRI-ST N-INV 5TSSOP")
      (fields
        (field (name "MANUFACTURER") "NXP Semiconductors")
        (field (name "MANUFACTURER PART NUMBER") "74LVC1G125GW,125")
      )
      (libsource (lib "BBB_Board") (part "Tri-State Buffer Non-Inverting"))
    )
    (comp (ref "TSB29")
      (value "Tri-State Buffer Non-Inverting")
      (footprint "tri_state")
      (description "IC BUFF DVR TRI-ST N-INV 5TSSOP")
      (fields
        (field (name "MANUFACTURER") "NXP Semiconductors")
        (field (name "MANUFACTURER PART NUMBER") "74LVC1G125GW,125")
      )
      (libsource (lib "BBB_Board") (part "Tri-State Buffer Non-Inverting"))
    )
    (comp (ref "TSB30")
      (value "Tri-State Buffer Non-Inverting")
      (footprint "tri_state")
      (description "IC BUFF DVR TRI-ST N-INV 5TSSOP")
      (fields
        (field (name "MANUFACTURER") "NXP Semiconductors")
        (field (name "MANUFACTURER PART NUMBER") "74LVC1G125GW,125")
      )
      (libsource (lib "BBB_Board") (part "Tri-State Buffer Non-Inverting"))
    )
    (comp (ref "TSB31")
      (value "Tri-State Buffer Non-Inverting")
      (footprint "tri_state")
      (description "IC BUFF DVR TRI-ST N-INV 5TSSOP")
      (fields
        (field (name "MANUFACTURER") "NXP Semiconductors")
        (field (name "MANUFACTURER PART NUMBER") "74LVC1G125GW,125")
      )
      (libsource (lib "BBB_Board") (part "Tri-State Buffer Non-Inverting"))
    )
    (comp (ref "TSB32")
      (value "Tri-State Buffer Non-Inverting")
      (footprint "tri_state")
      (description "IC BUFF DVR TRI-ST N-INV 5TSSOP")
      (fields
        (field (name "MANUFACTURER") "NXP Semiconductors")
        (field (name "MANUFACTURER PART NUMBER") "74LVC1G125GW,125")
      )
      (libsource (lib "BBB_Board") (part "Tri-State Buffer Non-Inverting"))
    )
    (comp (ref "TSB33")
      (value "Tri-State Buffer Non-Inverting")
      (footprint "tri_state")
      (description "IC BUFF DVR TRI-ST N-INV 5TSSOP")
      (fields
        (field (name "MANUFACTURER") "NXP Semiconductors")
        (field (name "MANUFACTURER PART NUMBER") "74LVC1G125GW,125")
      )
      (libsource (lib "BBB_Board") (part "Tri-State Buffer Non-Inverting"))
    )
    (comp (ref "TSB34")
      (value "Tri-State Buffer Non-Inverting")
      (footprint "tri_state")
      (description "IC BUFF DVR TRI-ST N-INV 5TSSOP")
      (fields
        (field (name "MANUFACTURER") "NXP Semiconductors")
        (field (name "MANUFACTURER PART NUMBER") "74LVC1G125GW,125")
      )
      (libsource (lib "BBB_Board") (part "Tri-State Buffer Non-Inverting"))
    )
    (comp (ref "TSB35")
      (value "Tri-State Buffer Non-Inverting")
      (footprint "tri_state")
      (description "IC BUFF DVR TRI-ST N-INV 5TSSOP")
      (fields
        (field (name "MANUFACTURER") "NXP Semiconductors")
        (field (name "MANUFACTURER PART NUMBER") "74LVC1G125GW,125")
      )
      (libsource (lib "BBB_Board") (part "Tri-State Buffer Non-Inverting"))
    )
    (comp (ref "TSB36")
      (value "Tri-State Buffer Non-Inverting")
      (footprint "tri_state")
      (description "IC BUFF DVR TRI-ST N-INV 5TSSOP")
      (fields
        (field (name "MANUFACTURER") "NXP Semiconductors")
        (field (name "MANUFACTURER PART NUMBER") "74LVC1G125GW,125")
      )
      (libsource (lib "BBB_Board") (part "Tri-State Buffer Non-Inverting"))
    )
    (comp (ref "TSB37")
      (value "Tri-State Buffer Non-Inverting")
      (footprint "tri_state")
      (description "IC BUFF DVR TRI-ST N-INV 5TSSOP")
      (fields
        (field (name "MANUFACTURER") "NXP Semiconductors")
        (field (name "MANUFACTURER PART NUMBER") "74LVC1G125GW,125")
      )
      (libsource (lib "BBB_Board") (part "Tri-State Buffer Non-Inverting"))
    )
    (comp (ref "TSB38")
      (value "Tri-State Buffer Non-Inverting")
      (footprint "tri_state")
      (description "IC BUFF DVR TRI-ST N-INV 5TSSOP")
      (fields
        (field (name "MANUFACTURER") "NXP Semiconductors")
        (field (name "MANUFACTURER PART NUMBER") "74LVC1G125GW,125")
      )
      (libsource (lib "BBB_Board") (part "Tri-State Buffer Non-Inverting"))
    )
    (comp (ref "TSB39")
      (value "Tri-State Buffer Non-Inverting")
      (footprint "tri_state")
      (description "IC BUFF DVR TRI-ST N-INV 5TSSOP")
      (fields
        (field (name "MANUFACTURER") "NXP Semiconductors")
        (field (name "MANUFACTURER PART NUMBER") "74LVC1G125GW,125")
      )
      (libsource (lib "BBB_Board") (part "Tri-State Buffer Non-Inverting"))
    )
    (comp (ref "TSB40")
      (value "Tri-State Buffer Non-Inverting")
      (footprint "tri_state")
      (description "IC BUFF DVR TRI-ST N-INV 5TSSOP")
      (fields
        (field (name "MANUFACTURER") "NXP Semiconductors")
        (field (name "MANUFACTURER PART NUMBER") "74LVC1G125GW,125")
      )
      (libsource (lib "BBB_Board") (part "Tri-State Buffer Non-Inverting"))
    )
    (comp (ref "TSB41")
      (value "Tri-State Buffer Non-Inverting")
      (footprint "tri_state")
      (description "IC BUFF DVR TRI-ST N-INV 5TSSOP")
      (fields
        (field (name "MANUFACTURER") "NXP Semiconductors")
        (field (name "MANUFACTURER PART NUMBER") "74LVC1G125GW,125")
      )
      (libsource (lib "BBB_Board") (part "Tri-State Buffer Non-Inverting"))
    )
    (comp (ref "TSB42")
      (value "Tri-State Buffer Non-Inverting")
      (footprint "tri_state")
      (description "IC BUFF DVR TRI-ST N-INV 5TSSOP")
      (fields
        (field (name "MANUFACTURER") "NXP Semiconductors")
        (field (name "MANUFACTURER PART NUMBER") "74LVC1G125GW,125")
      )
      (libsource (lib "BBB_Board") (part "Tri-State Buffer Non-Inverting"))
    )
    (comp (ref "TSB43")
      (value "Tri-State Buffer Non-Inverting")
      (footprint "tri_state")
      (description "IC BUFF DVR TRI-ST N-INV 5TSSOP")
      (fields
        (field (name "MANUFACTURER") "NXP Semiconductors")
        (field (name "MANUFACTURER PART NUMBER") "74LVC1G125GW,125")
      )
      (libsource (lib "BBB_Board") (part "Tri-State Buffer Non-Inverting"))
    )
    (comp (ref "TSB44")
      (value "Tri-State Buffer Non-Inverting")
      (footprint "tri_state")
      (description "IC BUFF DVR TRI-ST N-INV 5TSSOP")
      (fields
        (field (name "MANUFACTURER") "NXP Semiconductors")
        (field (name "MANUFACTURER PART NUMBER") "74LVC1G125GW,125")
      )
      (libsource (lib "BBB_Board") (part "Tri-State Buffer Non-Inverting"))
    )
    (comp (ref "TSB45")
      (value "Tri-State Buffer Non-Inverting")
      (footprint "tri_state")
      (description "IC BUFF DVR TRI-ST N-INV 5TSSOP")
      (fields
        (field (name "MANUFACTURER") "NXP Semiconductors")
        (field (name "MANUFACTURER PART NUMBER") "74LVC1G125GW,125")
      )
      (libsource (lib "BBB_Board") (part "Tri-State Buffer Non-Inverting"))
    )
    (comp (ref "TSB46")
      (value "Tri-State Buffer Non-Inverting")
      (footprint "tri_state")
      (description "IC BUFF DVR TRI-ST N-INV 5TSSOP")
      (fields
        (field (name "MANUFACTURER") "NXP Semiconductors")
        (field (name "MANUFACTURER PART NUMBER") "74LVC1G125GW,125")
      )
      (libsource (lib "BBB_Board") (part "Tri-State Buffer Non-Inverting"))
    )
    (comp (ref "TSB47")
      (value "Tri-State Buffer Non-Inverting")
      (footprint "tri_state")
      (description "IC BUFF DVR TRI-ST N-INV 5TSSOP")
      (fields
        (field (name "MANUFACTURER") "NXP Semiconductors")
        (field (name "MANUFACTURER PART NUMBER") "74LVC1G125GW,125")
      )
      (libsource (lib "BBB_Board") (part "Tri-State Buffer Non-Inverting"))
    )
    (comp (ref "TSB48")
      (value "Tri-State Buffer Non-Inverting")
      (footprint "tri_state")
      (description "IC BUFF DVR TRI-ST N-INV 5TSSOP")
      (fields
        (field (name "MANUFACTURER") "NXP Semiconductors")
        (field (name "MANUFACTURER PART NUMBER") "74LVC1G125GW,125")
      )
      (libsource (lib "BBB_Board") (part "Tri-State Buffer Non-Inverting"))
    )
    (comp (ref "TSB49")
      (value "Tri-State Buffer Non-Inverting")
      (footprint "tri_state")
      (description "IC BUFF DVR TRI-ST N-INV 5TSSOP")
      (fields
        (field (name "MANUFACTURER") "NXP Semiconductors")
        (field (name "MANUFACTURER PART NUMBER") "74LVC1G125GW,125")
      )
      (libsource (lib "BBB_Board") (part "Tri-State Buffer Non-Inverting"))
    )
    (comp (ref "TSB50")
      (value "Tri-State Buffer Non-Inverting")
      (footprint "tri_state")
      (description "IC BUFF DVR TRI-ST N-INV 5TSSOP")
      (fields
        (field (name "MANUFACTURER") "NXP Semiconductors")
        (field (name "MANUFACTURER PART NUMBER") "74LVC1G125GW,125")
      )
      (libsource (lib "BBB_Board") (part "Tri-State Buffer Non-Inverting"))
    )
    (comp (ref "TSB51")
      (value "Tri-State Buffer Non-Inverting")
      (footprint "tri_state")
      (description "IC BUFF DVR TRI-ST N-INV 5TSSOP")
      (fields
        (field (name "MANUFACTURER") "NXP Semiconductors")
        (field (name "MANUFACTURER PART NUMBER") "74LVC1G125GW,125")
      )
      (libsource (lib "BBB_Board") (part "Tri-State Buffer Non-Inverting"))
    )
    (comp (ref "TSB52")
      (value "Tri-State Buffer Non-Inverting")
      (footprint "tri_state")
      (description "IC BUFF DVR TRI-ST N-INV 5TSSOP")
      (fields
        (field (name "MANUFACTURER") "NXP Semiconductors")
        (field (name "MANUFACTURER PART NUMBER") "74LVC1G125GW,125")
      )
      (libsource (lib "BBB_Board") (part "Tri-State Buffer Non-Inverting"))
    )
    (comp (ref "TSB53")
      (value "Tri-State Buffer Non-Inverting")
      (footprint "tri_state")
      (description "IC BUFF DVR TRI-ST N-INV 5TSSOP")
      (fields
        (field (name "MANUFACTURER") "NXP Semiconductors")
        (field (name "MANUFACTURER PART NUMBER") "74LVC1G125GW,125")
      )
      (libsource (lib "BBB_Board") (part "Tri-State Buffer Non-Inverting"))
    )
    (comp (ref "TSB54")
      (value "Tri-State Buffer Non-Inverting")
      (footprint "tri_state")
      (description "IC BUFF DVR TRI-ST N-INV 5TSSOP")
      (fields
        (field (name "MANUFACTURER") "NXP Semiconductors")
        (field (name "MANUFACTURER PART NUMBER") "74LVC1G125GW,125")
      )
      (libsource (lib "BBB_Board") (part "Tri-State Buffer Non-Inverting"))
    )
    (comp (ref "TSB55")
      (value "Tri-State Buffer Non-Inverting")
      (footprint "tri_state")
      (description "IC BUFF DVR TRI-ST N-INV 5TSSOP")
      (fields
        (field (name "MANUFACTURER") "NXP Semiconductors")
        (field (name "MANUFACTURER PART NUMBER") "74LVC1G125GW,125")
      )
      (libsource (lib "BBB_Board") (part "Tri-State Buffer Non-Inverting"))
    )
    (comp (ref "TSB56")
      (value "Tri-State Buffer Non-Inverting")
      (footprint "tri_state")
      (description "IC BUFF DVR TRI-ST N-INV 5TSSOP")
      (fields
        (field (name "MANUFACTURER") "NXP Semiconductors")
        (field (name "MANUFACTURER PART NUMBER") "74LVC1G125GW,125")
      )
      (libsource (lib "BBB_Board") (part "Tri-State Buffer Non-Inverting"))
    )
    (comp (ref "TSB57")
      (value "Tri-State Buffer Non-Inverting")
      (footprint "tri_state")
      (description "IC BUFF DVR TRI-ST N-INV 5TSSOP")
      (fields
        (field (name "MANUFACTURER") "NXP Semiconductors")
        (field (name "MANUFACTURER PART NUMBER") "74LVC1G125GW,125")
      )
      (libsource (lib "BBB_Board") (part "Tri-State Buffer Non-Inverting"))
    )
    (comp (ref "TSB58")
      (value "Tri-State Buffer Non-Inverting")
      (footprint "tri_state")
      (description "IC BUFF DVR TRI-ST N-INV 5TSSOP")
      (fields
        (field (name "MANUFACTURER") "NXP Semiconductors")
        (field (name "MANUFACTURER PART NUMBER") "74LVC1G125GW,125")
      )
      (libsource (lib "BBB_Board") (part "Tri-State Buffer Non-Inverting"))
    )
    (comp (ref "TSB59")
      (value "Tri-State Buffer Non-Inverting")
      (footprint "tri_state")
      (description "IC BUFF DVR TRI-ST N-INV 5TSSOP")
      (fields
        (field (name "MANUFACTURER") "NXP Semiconductors")
        (field (name "MANUFACTURER PART NUMBER") "74LVC1G125GW,125")
      )
      (libsource (lib "BBB_Board") (part "Tri-State Buffer Non-Inverting"))
    )
    (comp (ref "TSB60")
      (value "Tri-State Buffer Non-Inverting")
      (footprint "tri_state")
      (description "IC BUFF DVR TRI-ST N-INV 5TSSOP")
      (fields
        (field (name "MANUFACTURER") "NXP Semiconductors")
        (field (name "MANUFACTURER PART NUMBER") "74LVC1G125GW,125")
      )
      (libsource (lib "BBB_Board") (part "Tri-State Buffer Non-Inverting"))
    )
    (comp (ref "TSB61")
      (value "Tri-State Buffer Non-Inverting")
      (footprint "tri_state")
      (description "IC BUFF DVR TRI-ST N-INV 5TSSOP")
      (fields
        (field (name "MANUFACTURER") "NXP Semiconductors")
        (field (name "MANUFACTURER PART NUMBER") "74LVC1G125GW,125")
      )
      (libsource (lib "BBB_Board") (part "Tri-State Buffer Non-Inverting"))
    )
    (comp (ref "TSB62")
      (value "Tri-State Buffer Non-Inverting")
      (footprint "tri_state")
      (description "IC BUFF DVR TRI-ST N-INV 5TSSOP")
      (fields
        (field (name "MANUFACTURER") "NXP Semiconductors")
        (field (name "MANUFACTURER PART NUMBER") "74LVC1G125GW,125")
      )
      (libsource (lib "BBB_Board") (part "Tri-State Buffer Non-Inverting"))
    )
    (comp (ref "TSB63")
      (value "Tri-State Buffer Non-Inverting")
      (footprint "tri_state")
      (description "IC BUFF DVR TRI-ST N-INV 5TSSOP")
      (fields
        (field (name "MANUFACTURER") "NXP Semiconductors")
        (field (name "MANUFACTURER PART NUMBER") "74LVC1G125GW,125")
      )
      (libsource (lib "BBB_Board") (part "Tri-State Buffer Non-Inverting"))
    )
    (comp (ref "TSB64")
      (value "Tri-State Buffer Non-Inverting")
      (footprint "tri_state")
      (description "IC BUFF DVR TRI-ST N-INV 5TSSOP")
      (fields
        (field (name "MANUFACTURER") "NXP Semiconductors")
        (field (name "MANUFACTURER PART NUMBER") "74LVC1G125GW,125")
      )
      (libsource (lib "BBB_Board") (part "Tri-State Buffer Non-Inverting"))
    )
    (comp (ref "TSB65")
      (value "Tri-State Buffer Non-Inverting")
      (footprint "tri_state")
      (description "IC BUFF DVR TRI-ST N-INV 5TSSOP")
      (fields
        (field (name "MANUFACTURER") "NXP Semiconductors")
        (field (name "MANUFACTURER PART NUMBER") "74LVC1G125GW,125")
      )
      (libsource (lib "BBB_Board") (part "Tri-State Buffer Non-Inverting"))
    )
    (comp (ref "TSB66")
      (value "Tri-State Buffer Non-Inverting")
      (footprint "tri_state")
      (description "IC BUFF DVR TRI-ST N-INV 5TSSOP")
      (fields
        (field (name "MANUFACTURER") "NXP Semiconductors")
        (field (name "MANUFACTURER PART NUMBER") "74LVC1G125GW,125")
      )
      (libsource (lib "BBB_Board") (part "Tri-State Buffer Non-Inverting"))
    )
    (comp (ref "TSB67")
      (value "Tri-State Buffer Non-Inverting")
      (footprint "tri_state")
      (description "IC BUFF DVR TRI-ST N-INV 5TSSOP")
      (fields
        (field (name "MANUFACTURER") "NXP Semiconductors")
        (field (name "MANUFACTURER PART NUMBER") "74LVC1G125GW,125")
      )
      (libsource (lib "BBB_Board") (part "Tri-State Buffer Non-Inverting"))
    )
    (comp (ref "TSB68")
      (value "Tri-State Buffer Non-Inverting")
      (footprint "tri_state")
      (description "IC BUFF DVR TRI-ST N-INV 5TSSOP")
      (fields
        (field (name "MANUFACTURER") "NXP Semiconductors")
        (field (name "MANUFACTURER PART NUMBER") "74LVC1G125GW,125")
      )
      (libsource (lib "BBB_Board") (part "Tri-State Buffer Non-Inverting"))
    )
    (comp (ref "TSB69")
      (value "Tri-State Buffer Non-Inverting")
      (footprint "tri_state")
      (description "IC BUFF DVR TRI-ST N-INV 5TSSOP")
      (fields
        (field (name "MANUFACTURER") "NXP Semiconductors")
        (field (name "MANUFACTURER PART NUMBER") "74LVC1G125GW,125")
      )
      (libsource (lib "BBB_Board") (part "Tri-State Buffer Non-Inverting"))
    )
    (comp (ref "TSB70")
      (value "Tri-State Buffer Non-Inverting")
      (footprint "tri_state")
      (description "IC BUFF DVR TRI-ST N-INV 5TSSOP")
      (fields
        (field (name "MANUFACTURER") "NXP Semiconductors")
        (field (name "MANUFACTURER PART NUMBER") "74LVC1G125GW,125")
      )
      (libsource (lib "BBB_Board") (part "Tri-State Buffer Non-Inverting"))
    )
    (comp (ref "TSB71")
      (value "Tri-State Buffer Non-Inverting")
      (footprint "tri_state")
      (description "IC BUFF DVR TRI-ST N-INV 5TSSOP")
      (fields
        (field (name "MANUFACTURER") "NXP Semiconductors")
        (field (name "MANUFACTURER PART NUMBER") "74LVC1G125GW,125")
      )
      (libsource (lib "BBB_Board") (part "Tri-State Buffer Non-Inverting"))
    )
    (comp (ref "TSB72")
      (value "Tri-State Buffer Non-Inverting")
      (footprint "tri_state")
      (description "IC BUFF DVR TRI-ST N-INV 5TSSOP")
      (fields
        (field (name "MANUFACTURER") "NXP Semiconductors")
        (field (name "MANUFACTURER PART NUMBER") "74LVC1G125GW,125")
      )
      (libsource (lib "BBB_Board") (part "Tri-State Buffer Non-Inverting"))
    )
    (comp (ref "TSB73")
      (value "Tri-State Buffer Non-Inverting")
      (footprint "tri_state")
      (description "IC BUFF DVR TRI-ST N-INV 5TSSOP")
      (fields
        (field (name "MANUFACTURER") "NXP Semiconductors")
        (field (name "MANUFACTURER PART NUMBER") "74LVC1G125GW,125")
      )
      (libsource (lib "BBB_Board") (part "Tri-State Buffer Non-Inverting"))
    )
    (comp (ref "TSB74")
      (value "Tri-State Buffer Non-Inverting")
      (footprint "tri_state")
      (description "IC BUFF DVR TRI-ST N-INV 5TSSOP")
      (fields
        (field (name "MANUFACTURER") "NXP Semiconductors")
        (field (name "MANUFACTURER PART NUMBER") "74LVC1G125GW,125")
      )
      (libsource (lib "BBB_Board") (part "Tri-State Buffer Non-Inverting"))
    )
    (comp (ref "TSB75")
      (value "Tri-State Buffer Non-Inverting")
      (footprint "tri_state")
      (description "IC BUFF DVR TRI-ST N-INV 5TSSOP")
      (fields
        (field (name "MANUFACTURER") "NXP Semiconductors")
        (field (name "MANUFACTURER PART NUMBER") "74LVC1G125GW,125")
      )
      (libsource (lib "BBB_Board") (part "Tri-State Buffer Non-Inverting"))
    )
    (comp (ref "TSB76")
      (value "Tri-State Buffer Non-Inverting")
      (footprint "tri_state")
      (description "IC BUFF DVR TRI-ST N-INV 5TSSOP")
      (fields
        (field (name "MANUFACTURER") "NXP Semiconductors")
        (field (name "MANUFACTURER PART NUMBER") "74LVC1G125GW,125")
      )
      (libsource (lib "BBB_Board") (part "Tri-State Buffer Non-Inverting"))
    )
    (comp (ref "TSB77")
      (value "Tri-State Buffer Non-Inverting")
      (footprint "tri_state")
      (description "IC BUFF DVR TRI-ST N-INV 5TSSOP")
      (fields
        (field (name "MANUFACTURER") "NXP Semiconductors")
        (field (name "MANUFACTURER PART NUMBER") "74LVC1G125GW,125")
      )
      (libsource (lib "BBB_Board") (part "Tri-State Buffer Non-Inverting"))
    )
    (comp (ref "TSB78")
      (value "Tri-State Buffer Non-Inverting")
      (footprint "tri_state")
      (description "IC BUFF DVR TRI-ST N-INV 5TSSOP")
      (fields
        (field (name "MANUFACTURER") "NXP Semiconductors")
        (field (name "MANUFACTURER PART NUMBER") "74LVC1G125GW,125")
      )
      (libsource (lib "BBB_Board") (part "Tri-State Buffer Non-Inverting"))
    )
    (comp (ref "TSB79")
      (value "Tri-State Buffer Non-Inverting")
      (footprint "tri_state")
      (description "IC BUFF DVR TRI-ST N-INV 5TSSOP")
      (fields
        (field (name "MANUFACTURER") "NXP Semiconductors")
        (field (name "MANUFACTURER PART NUMBER") "74LVC1G125GW,125")
      )
      (libsource (lib "BBB_Board") (part "Tri-State Buffer Non-Inverting"))
    )
    (comp (ref "TSB80")
      (value "Tri-State Buffer Non-Inverting")
      (footprint "tri_state")
      (description "IC BUFF DVR TRI-ST N-INV 5TSSOP")
      (fields
        (field (name "MANUFACTURER") "NXP Semiconductors")
        (field (name "MANUFACTURER PART NUMBER") "74LVC1G125GW,125")
      )
      (libsource (lib "BBB_Board") (part "Tri-State Buffer Non-Inverting"))
    )
    (comp (ref "TSB81")
      (value "Tri-State Buffer Non-Inverting")
      (footprint "tri_state")
      (description "IC BUFF DVR TRI-ST N-INV 5TSSOP")
      (fields
        (field (name "MANUFACTURER") "NXP Semiconductors")
        (field (name "MANUFACTURER PART NUMBER") "74LVC1G125GW,125")
      )
      (libsource (lib "BBB_Board") (part "Tri-State Buffer Non-Inverting"))
    )
    (comp (ref "TSB82")
      (value "Tri-State Buffer Non-Inverting")
      (footprint "tri_state")
      (description "IC BUFF DVR TRI-ST N-INV 5TSSOP")
      (fields
        (field (name "MANUFACTURER") "NXP Semiconductors")
        (field (name "MANUFACTURER PART NUMBER") "74LVC1G125GW,125")
      )
      (libsource (lib "BBB_Board") (part "Tri-State Buffer Non-Inverting"))
    )
    (comp (ref "TSB83")
      (value "Tri-State Buffer Non-Inverting")
      (footprint "tri_state")
      (description "IC BUFF DVR TRI-ST N-INV 5TSSOP")
      (fields
        (field (name "MANUFACTURER") "NXP Semiconductors")
        (field (name "MANUFACTURER PART NUMBER") "74LVC1G125GW,125")
      )
      (libsource (lib "BBB_Board") (part "Tri-State Buffer Non-Inverting"))
    )
    (comp (ref "TSB84")
      (value "Tri-State Buffer Non-Inverting")
      (footprint "tri_state")
      (description "IC BUFF DVR TRI-ST N-INV 5TSSOP")
      (fields
        (field (name "MANUFACTURER") "NXP Semiconductors")
        (field (name "MANUFACTURER PART NUMBER") "74LVC1G125GW,125")
      )
      (libsource (lib "BBB_Board") (part "Tri-State Buffer Non-Inverting"))
    )
    (comp (ref "TSB85")
      (value "Tri-State Buffer Non-Inverting")
      (footprint "tri_state")
      (description "IC BUFF DVR TRI-ST N-INV 5TSSOP")
      (fields
        (field (name "MANUFACTURER") "NXP Semiconductors")
        (field (name "MANUFACTURER PART NUMBER") "74LVC1G125GW,125")
      )
      (libsource (lib "BBB_Board") (part "Tri-State Buffer Non-Inverting"))
    )
    (comp (ref "TSB86")
      (value "Tri-State Buffer Non-Inverting")
      (footprint "tri_state")
      (description "IC BUFF DVR TRI-ST N-INV 5TSSOP")
      (fields
        (field (name "MANUFACTURER") "NXP Semiconductors")
        (field (name "MANUFACTURER PART NUMBER") "74LVC1G125GW,125")
      )
      (libsource (lib "BBB_Board") (part "Tri-State Buffer Non-Inverting"))
    )
    (comp (ref "TSB87")
      (value "Tri-State Buffer Non-Inverting")
      (footprint "tri_state")
      (description "IC BUFF DVR TRI-ST N-INV 5TSSOP")
      (fields
        (field (name "MANUFACTURER") "NXP Semiconductors")
        (field (name "MANUFACTURER PART NUMBER") "74LVC1G125GW,125")
      )
      (libsource (lib "BBB_Board") (part "Tri-State Buffer Non-Inverting"))
    )
    (comp (ref "TSB88")
      (value "Tri-State Buffer Non-Inverting")
      (footprint "tri_state")
      (description "IC BUFF DVR TRI-ST N-INV 5TSSOP")
      (fields
        (field (name "MANUFACTURER") "NXP Semiconductors")
        (field (name "MANUFACTURER PART NUMBER") "74LVC1G125GW,125")
      )
      (libsource (lib "BBB_Board") (part "Tri-State Buffer Non-Inverting"))
    )
    (comp (ref "TSB89")
      (value "Tri-State Buffer Non-Inverting")
      (footprint "tri_state")
      (description "IC BUFF DVR TRI-ST N-INV 5TSSOP")
      (fields
        (field (name "MANUFACTURER") "NXP Semiconductors")
        (field (name "MANUFACTURER PART NUMBER") "74LVC1G125GW,125")
      )
      (libsource (lib "BBB_Board") (part "Tri-State Buffer Non-Inverting"))
    )
    (comp (ref "TSB90")
      (value "Tri-State Buffer Non-Inverting")
      (footprint "tri_state")
      (description "IC BUFF DVR TRI-ST N-INV 5TSSOP")
      (fields
        (field (name "MANUFACTURER") "NXP Semiconductors")
        (field (name "MANUFACTURER PART NUMBER") "74LVC1G125GW,125")
      )
      (libsource (lib "BBB_Board") (part "Tri-State Buffer Non-Inverting"))
    )
    (comp (ref "TSB91")
      (value "Tri-State Buffer Non-Inverting")
      (footprint "tri_state")
      (description "IC BUFF DVR TRI-ST N-INV 5TSSOP")
      (fields
        (field (name "MANUFACTURER") "NXP Semiconductors")
        (field (name "MANUFACTURER PART NUMBER") "74LVC1G125GW,125")
      )
      (libsource (lib "BBB_Board") (part "Tri-State Buffer Non-Inverting"))
    )
    (comp (ref "TSB92")
      (value "Tri-State Buffer Non-Inverting")
      (footprint "tri_state")
      (description "IC BUFF DVR TRI-ST N-INV 5TSSOP")
      (fields
        (field (name "MANUFACTURER") "NXP Semiconductors")
        (field (name "MANUFACTURER PART NUMBER") "74LVC1G125GW,125")
      )
      (libsource (lib "BBB_Board") (part "Tri-State Buffer Non-Inverting"))
    )
    (comp (ref "TSB93")
      (value "Tri-State Buffer Non-Inverting")
      (footprint "tri_state")
      (description "IC BUFF DVR TRI-ST N-INV 5TSSOP")
      (fields
        (field (name "MANUFACTURER") "NXP Semiconductors")
        (field (name "MANUFACTURER PART NUMBER") "74LVC1G125GW,125")
      )
      (libsource (lib "BBB_Board") (part "Tri-State Buffer Non-Inverting"))
    )
    (comp (ref "TSB94")
      (value "Tri-State Buffer Non-Inverting")
      (footprint "tri_state")
      (description "IC BUFF DVR TRI-ST N-INV 5TSSOP")
      (fields
        (field (name "MANUFACTURER") "NXP Semiconductors")
        (field (name "MANUFACTURER PART NUMBER") "74LVC1G125GW,125")
      )
      (libsource (lib "BBB_Board") (part "Tri-State Buffer Non-Inverting"))
    )
    (comp (ref "TSB95")
      (value "Tri-State Buffer Non-Inverting")
      (footprint "tri_state")
      (description "IC BUFF DVR TRI-ST N-INV 5TSSOP")
      (fields
        (field (name "MANUFACTURER") "NXP Semiconductors")
        (field (name "MANUFACTURER PART NUMBER") "74LVC1G125GW,125")
      )
      (libsource (lib "BBB_Board") (part "Tri-State Buffer Non-Inverting"))
    )
    (comp (ref "TSB96")
      (value "Tri-State Buffer Non-Inverting")
      (footprint "tri_state")
      (description "IC BUFF DVR TRI-ST N-INV 5TSSOP")
      (fields
        (field (name "MANUFACTURER") "NXP Semiconductors")
        (field (name "MANUFACTURER PART NUMBER") "74LVC1G125GW,125")
      )
      (libsource (lib "BBB_Board") (part "Tri-State Buffer Non-Inverting"))
    )
    (comp (ref "TSB97")
      (value "Tri-State Buffer Non-Inverting")
      (footprint "tri_state")
      (description "IC BUFF DVR TRI-ST N-INV 5TSSOP")
      (fields
        (field (name "MANUFACTURER") "NXP Semiconductors")
        (field (name "MANUFACTURER PART NUMBER") "74LVC1G125GW,125")
      )
      (libsource (lib "BBB_Board") (part "Tri-State Buffer Non-Inverting"))
    )
    (comp (ref "TSB98")
      (value "Tri-State Buffer Non-Inverting")
      (footprint "tri_state")
      (description "IC BUFF DVR TRI-ST N-INV 5TSSOP")
      (fields
        (field (name "MANUFACTURER") "NXP Semiconductors")
        (field (name "MANUFACTURER PART NUMBER") "74LVC1G125GW,125")
      )
      (libsource (lib "BBB_Board") (part "Tri-State Buffer Non-Inverting"))
    )
    (comp (ref "TSB99")
      (value "Tri-State Buffer Non-Inverting")
      (footprint "tri_state")
      (description "IC BUFF DVR TRI-ST N-INV 5TSSOP")
      (fields
        (field (name "MANUFACTURER") "NXP Semiconductors")
        (field (name "MANUFACTURER PART NUMBER") "74LVC1G125GW,125")
      )
      (libsource (lib "BBB_Board") (part "Tri-State Buffer Non-Inverting"))
    )
    (comp (ref "TSB100")
      (value "Tri-State Buffer Non-Inverting")
      (footprint "tri_state")
      (description "IC BUFF DVR TRI-ST N-INV 5TSSOP")
      (fields
        (field (name "MANUFACTURER") "NXP Semiconductors")
        (field (name "MANUFACTURER PART NUMBER") "74LVC1G125GW,125")
      )
      (libsource (lib "BBB_Board") (part "Tri-State Buffer Non-Inverting"))
    )
    (comp (ref "TSB101")
      (value "Tri-State Buffer Non-Inverting")
      (footprint "tri_state")
      (description "IC BUFF DVR TRI-ST N-INV 5TSSOP")
      (fields
        (field (name "MANUFACTURER") "NXP Semiconductors")
        (field (name "MANUFACTURER PART NUMBER") "74LVC1G125GW,125")
      )
      (libsource (lib "BBB_Board") (part "Tri-State Buffer Non-Inverting"))
    )
    (comp (ref "TSB102")
      (value "Tri-State Buffer Non-Inverting")
      (footprint "tri_state")
      (description "IC BUFF DVR TRI-ST N-INV 5TSSOP")
      (fields
        (field (name "MANUFACTURER") "NXP Semiconductors")
        (field (name "MANUFACTURER PART NUMBER") "74LVC1G125GW,125")
      )
      (libsource (lib "BBB_Board") (part "Tri-State Buffer Non-Inverting"))
    )
    (comp (ref "TSB103")
      (value "Tri-State Buffer Non-Inverting")
      (footprint "tri_state")
      (description "IC BUFF DVR TRI-ST N-INV 5TSSOP")
      (fields
        (field (name "MANUFACTURER") "NXP Semiconductors")
        (field (name "MANUFACTURER PART NUMBER") "74LVC1G125GW,125")
      )
      (libsource (lib "BBB_Board") (part "Tri-State Buffer Non-Inverting"))
    )
    (comp (ref "TSB104")
      (value "Tri-State Buffer Non-Inverting")
      (footprint "tri_state")
      (description "IC BUFF DVR TRI-ST N-INV 5TSSOP")
      (fields
        (field (name "MANUFACTURER") "NXP Semiconductors")
        (field (name "MANUFACTURER PART NUMBER") "74LVC1G125GW,125")
      )
      (libsource (lib "BBB_Board") (part "Tri-State Buffer Non-Inverting"))
    )
    (comp (ref "TSB105")
      (value "Tri-State Buffer Non-Inverting")
      (footprint "tri_state")
      (description "IC BUFF DVR TRI-ST N-INV 5TSSOP")
      (fields
        (field (name "MANUFACTURER") "NXP Semiconductors")
        (field (name "MANUFACTURER PART NUMBER") "74LVC1G125GW,125")
      )
      (libsource (lib "BBB_Board") (part "Tri-State Buffer Non-Inverting"))
    )
    (comp (ref "TSB106")
      (value "Tri-State Buffer Non-Inverting")
      (footprint "tri_state")
      (description "IC BUFF DVR TRI-ST N-INV 5TSSOP")
      (fields
        (field (name "MANUFACTURER") "NXP Semiconductors")
        (field (name "MANUFACTURER PART NUMBER") "74LVC1G125GW,125")
      )
      (libsource (lib "BBB_Board") (part "Tri-State Buffer Non-Inverting"))
    )
    (comp (ref "TSB107")
      (value "Tri-State Buffer Non-Inverting")
      (footprint "tri_state")
      (description "IC BUFF DVR TRI-ST N-INV 5TSSOP")
      (fields
        (field (name "MANUFACTURER") "NXP Semiconductors")
        (field (name "MANUFACTURER PART NUMBER") "74LVC1G125GW,125")
      )
      (libsource (lib "BBB_Board") (part "Tri-State Buffer Non-Inverting"))
    )
    (comp (ref "TSB108")
      (value "Tri-State Buffer Non-Inverting")
      (footprint "tri_state")
      (description "IC BUFF DVR TRI-ST N-INV 5TSSOP")
      (fields
        (field (name "MANUFACTURER") "NXP Semiconductors")
        (field (name "MANUFACTURER PART NUMBER") "74LVC1G125GW,125")
      )
      (libsource (lib "BBB_Board") (part "Tri-State Buffer Non-Inverting"))
    )
    (comp (ref "TSB109")
      (value "Tri-State Buffer Non-Inverting")
      (footprint "tri_state")
      (description "IC BUFF DVR TRI-ST N-INV 5TSSOP")
      (fields
        (field (name "MANUFACTURER") "NXP Semiconductors")
        (field (name "MANUFACTURER PART NUMBER") "74LVC1G125GW,125")
      )
      (libsource (lib "BBB_Board") (part "Tri-State Buffer Non-Inverting"))
    )
    (comp (ref "TSB110")
      (value "Tri-State Buffer Non-Inverting")
      (footprint "tri_state")
      (description "IC BUFF DVR TRI-ST N-INV 5TSSOP")
      (fields
        (field (name "MANUFACTURER") "NXP Semiconductors")
        (field (name "MANUFACTURER PART NUMBER") "74LVC1G125GW,125")
      )
      (libsource (lib "BBB_Board") (part "Tri-State Buffer Non-Inverting"))
    )
    (comp (ref "TSB111")
      (value "Tri-State Buffer Non-Inverting")
      (footprint "tri_state")
      (description "IC BUFF DVR TRI-ST N-INV 5TSSOP")
      (fields
        (field (name "MANUFACTURER") "NXP Semiconductors")
        (field (name "MANUFACTURER PART NUMBER") "74LVC1G125GW,125")
      )
      (libsource (lib "BBB_Board") (part "Tri-State Buffer Non-Inverting"))
    )
    (comp (ref "TSB112")
      (value "Tri-State Buffer Non-Inverting")
      (footprint "tri_state")
      (description "IC BUFF DVR TRI-ST N-INV 5TSSOP")
      (fields
        (field (name "MANUFACTURER") "NXP Semiconductors")
        (field (name "MANUFACTURER PART NUMBER") "74LVC1G125GW,125")
      )
      (libsource (lib "BBB_Board") (part "Tri-State Buffer Non-Inverting"))
    )
    (comp (ref "TSB113")
      (value "Tri-State Buffer Non-Inverting")
      (footprint "tri_state")
      (description "IC BUFF DVR TRI-ST N-INV 5TSSOP")
      (fields
        (field (name "MANUFACTURER") "NXP Semiconductors")
        (field (name "MANUFACTURER PART NUMBER") "74LVC1G125GW,125")
      )
      (libsource (lib "BBB_Board") (part "Tri-State Buffer Non-Inverting"))
    )
    (comp (ref "TSB114")
      (value "Tri-State Buffer Non-Inverting")
      (footprint "tri_state")
      (description "IC BUFF DVR TRI-ST N-INV 5TSSOP")
      (fields
        (field (name "MANUFACTURER") "NXP Semiconductors")
        (field (name "MANUFACTURER PART NUMBER") "74LVC1G125GW,125")
      )
      (libsource (lib "BBB_Board") (part "Tri-State Buffer Non-Inverting"))
    )
    (comp (ref "TSB115")
      (value "Tri-State Buffer Non-Inverting")
      (footprint "tri_state")
      (description "IC BUFF DVR TRI-ST N-INV 5TSSOP")
      (fields
        (field (name "MANUFACTURER") "NXP Semiconductors")
        (field (name "MANUFACTURER PART NUMBER") "74LVC1G125GW,125")
      )
      (libsource (lib "BBB_Board") (part "Tri-State Buffer Non-Inverting"))
    )
    (comp (ref "TSB116")
      (value "Tri-State Buffer Non-Inverting")
      (footprint "tri_state")
      (description "IC BUFF DVR TRI-ST N-INV 5TSSOP")
      (fields
        (field (name "MANUFACTURER") "NXP Semiconductors")
        (field (name "MANUFACTURER PART NUMBER") "74LVC1G125GW,125")
      )
      (libsource (lib "BBB_Board") (part "Tri-State Buffer Non-Inverting"))
    )
    (comp (ref "TSB117")
      (value "Tri-State Buffer Non-Inverting")
      (footprint "tri_state")
      (description "IC BUFF DVR TRI-ST N-INV 5TSSOP")
      (fields
        (field (name "MANUFACTURER") "NXP Semiconductors")
        (field (name "MANUFACTURER PART NUMBER") "74LVC1G125GW,125")
      )
      (libsource (lib "BBB_Board") (part "Tri-State Buffer Non-Inverting"))
    )
    (comp (ref "TSB118")
      (value "Tri-State Buffer Non-Inverting")
      (footprint "tri_state")
      (description "IC BUFF DVR TRI-ST N-INV 5TSSOP")
      (fields
        (field (name "MANUFACTURER") "NXP Semiconductors")
        (field (name "MANUFACTURER PART NUMBER") "74LVC1G125GW,125")
      )
      (libsource (lib "BBB_Board") (part "Tri-State Buffer Non-Inverting"))
    )
    (comp (ref "TSB119")
      (value "Tri-State Buffer Non-Inverting")
      (footprint "tri_state")
      (description "IC BUFF DVR TRI-ST N-INV 5TSSOP")
      (fields
        (field (name "MANUFACTURER") "NXP Semiconductors")
        (field (name "MANUFACTURER PART NUMBER") "74LVC1G125GW,125")
      )
      (libsource (lib "BBB_Board") (part "Tri-State Buffer Non-Inverting"))
    )
    (comp (ref "TSB120")
      (value "Tri-State Buffer Non-Inverting")
      (footprint "tri_state")
      (description "IC BUFF DVR TRI-ST N-INV 5TSSOP")
      (fields
        (field (name "MANUFACTURER") "NXP Semiconductors")
        (field (name "MANUFACTURER PART NUMBER") "74LVC1G125GW,125")
      )
      (libsource (lib "BBB_Board") (part "Tri-State Buffer Non-Inverting"))
    )
    (comp (ref "TSB121")
      (value "Tri-State Buffer Non-Inverting")
      (footprint "tri_state")
      (description "IC BUFF DVR TRI-ST N-INV 5TSSOP")
      (fields
        (field (name "MANUFACTURER") "NXP Semiconductors")
        (field (name "MANUFACTURER PART NUMBER") "74LVC1G125GW,125")
      )
      (libsource (lib "BBB_Board") (part "Tri-State Buffer Non-Inverting"))
    )
    (comp (ref "TSB122")
      (value "Tri-State Buffer Non-Inverting")
      (footprint "tri_state")
      (description "IC BUFF DVR TRI-ST N-INV 5TSSOP")
      (fields
        (field (name "MANUFACTURER") "NXP Semiconductors")
        (field (name "MANUFACTURER PART NUMBER") "74LVC1G125GW,125")
      )
      (libsource (lib "BBB_Board") (part "Tri-State Buffer Non-Inverting"))
    )
    (comp (ref "TSB123")
      (value "Tri-State Buffer Non-Inverting")
      (footprint "tri_state")
      (description "IC BUFF DVR TRI-ST N-INV 5TSSOP")
      (fields
        (field (name "MANUFACTURER") "NXP Semiconductors")
        (field (name "MANUFACTURER PART NUMBER") "74LVC1G125GW,125")
      )
      (libsource (lib "BBB_Board") (part "Tri-State Buffer Non-Inverting"))
    )
    (comp (ref "TSB124")
      (value "Tri-State Buffer Non-Inverting")
      (footprint "tri_state")
      (description "IC BUFF DVR TRI-ST N-INV 5TSSOP")
      (fields
        (field (name "MANUFACTURER") "NXP Semiconductors")
        (field (name "MANUFACTURER PART NUMBER") "74LVC1G125GW,125")
      )
      (libsource (lib "BBB_Board") (part "Tri-State Buffer Non-Inverting"))
    )
    (comp (ref "TSB125")
      (value "Tri-State Buffer Non-Inverting")
      (footprint "tri_state")
      (description "IC BUFF DVR TRI-ST N-INV 5TSSOP")
      (fields
        (field (name "MANUFACTURER") "NXP Semiconductors")
        (field (name "MANUFACTURER PART NUMBER") "74LVC1G125GW,125")
      )
      (libsource (lib "BBB_Board") (part "Tri-State Buffer Non-Inverting"))
    )
    (comp (ref "TSB126")
      (value "Tri-State Buffer Non-Inverting")
      (footprint "tri_state")
      (description "IC BUFF DVR TRI-ST N-INV 5TSSOP")
      (fields
        (field (name "MANUFACTURER") "NXP Semiconductors")
        (field (name "MANUFACTURER PART NUMBER") "74LVC1G125GW,125")
      )
      (libsource (lib "BBB_Board") (part "Tri-State Buffer Non-Inverting"))
    )
    (comp (ref "TSB127")
      (value "Tri-State Buffer Non-Inverting")
      (footprint "tri_state")
      (description "IC BUFF DVR TRI-ST N-INV 5TSSOP")
      (fields
        (field (name "MANUFACTURER") "NXP Semiconductors")
        (field (name "MANUFACTURER PART NUMBER") "74LVC1G125GW,125")
      )
      (libsource (lib "BBB_Board") (part "Tri-State Buffer Non-Inverting"))
    )
    (comp (ref "TSB128")
      (value "Tri-State Buffer Non-Inverting")
      (footprint "tri_state")
      (description "IC BUFF DVR TRI-ST N-INV 5TSSOP")
      (fields
        (field (name "MANUFACTURER") "NXP Semiconductors")
        (field (name "MANUFACTURER PART NUMBER") "74LVC1G125GW,125")
      )
      (libsource (lib "BBB_Board") (part "Tri-State Buffer Non-Inverting"))
    )
  )
  (nets
    (net (code "1") (name "/A_B0") (class "Default")
      (node (ref "TSB1") (pin "2") (pinfunction "A_2") (pintype "passive"))
    )
    (net (code "2") (name "/A_B1") (class "Default")
      (node (ref "TSB8") (pin "2") (pinfunction "A_2") (pintype "passive"))
    )
    (net (code "3") (name "/A_B2") (class "Default")
      (node (ref "TSB15") (pin "2") (pinfunction "A_2") (pintype "passive"))
    )
    (net (code "4") (name "/A_B3") (class "Default")
      (node (ref "TSB22") (pin "2") (pinfunction "A_2") (pintype "passive"))
    )
    (net (code "5") (name "/A_B4") (class "Default")
      (node (ref "TSB29") (pin "2") (pinfunction "A_2") (pintype "passive"))
    )
    (net (code "6") (name "/A_B5") (class "Default")
      (node (ref "TSB36") (pin "2") (pinfunction "A_2") (pintype "passive"))
    )
    (net (code "7") (name "/A_B6") (class "Default")
      (node (ref "TSB43") (pin "2") (pinfunction "A_2") (pintype "passive"))
    )
    (net (code "8") (name "/A_B7") (class "Default")
      (node (ref "TSB50") (pin "2") (pinfunction "A_2") (pintype "passive"))
    )
    (net (code "9") (name "/A_B8") (class "Default")
      (node (ref "TSB57") (pin "2") (pinfunction "A_2") (pintype "passive"))
    )
    (net (code "10") (name "/A_B9") (class "Default")
      (node (ref "TSB64") (pin "2") (pinfunction "A_2") (pintype "passive"))
    )
    (net (code "11") (name "/A_B10") (class "Default")
      (node (ref "TSB71") (pin "2") (pinfunction "A_2") (pintype "passive"))
    )
    (net (code "12") (name "/A_B11") (class "Default")
      (node (ref "TSB78") (pin "2") (pinfunction "A_2") (pintype "passive"))
    )
    (net (code "13") (name "/A_B12") (class "Default")
      (node (ref "TSB85") (pin "2") (pinfunction "A_2") (pintype "passive"))
    )
    (net (code "14") (name "/A_B13") (class "Default")
      (node (ref "TSB92") (pin "2") (pinfunction "A_2") (pintype "passive"))
    )
    (net (code "15") (name "/A_B14") (class "Default")
      (node (ref "TSB99") (pin "2") (pinfunction "A_2") (pintype "passive"))
    )
    (net (code "16") (name "/A_B15") (class "Default")
      (node (ref "TSB106") (pin "2") (pinfunction "A_2") (pintype "passive"))
    )
    (net (code "17") (name "/A_B16") (class "Default")
      (node (ref "TSB113") (pin "2") (pinfunction "A_2") (pintype "passive"))
    )
    (net (code "18") (name "/A_B17") (class "Default")
      (node (ref "TSB120") (pin "2") (pinfunction "A_2") (pintype "passive"))
    )
    (net (code "19") (name "/A_B18") (class "Default")
      (node (ref "TSB2") (pin "2") (pinfunction "A_2") (pintype "passive"))
    )
    (net (code "20") (name "/A_B19") (class "Default")
      (node (ref "TSB9") (pin "2") (pinfunction "A_2") (pintype "passive"))
    )
    (net (code "21") (name "/A_B20") (class "Default")
      (node (ref "TSB16") (pin "2") (pinfunction "A_2") (pintype "passive"))
    )
    (net (code "22") (name "/A_B21") (class "Default")
      (node (ref "TSB23") (pin "2") (pinfunction "A_2") (pintype "passive"))
    )
    (net (code "23") (name "/A_B22") (class "Default")
      (node (ref "TSB30") (pin "2") (pinfunction "A_2") (pintype "passive"))
    )
    (net (code "24") (name "/A_B23") (class "Default")
      (node (ref "TSB37") (pin "2") (pinfunction "A_2") (pintype "passive"))
    )
    (net (code "25") (name "/A_B24") (class "Default")
      (node (ref "TSB44") (pin "2") (pinfunction "A_2") (pintype "passive"))
    )
    (net (code "26") (name "/A_B25") (class "Default")
      (node (ref "TSB51") (pin "2") (pinfunction "A_2") (pintype "passive"))
    )
    (net (code "27") (name "/A_B26") (class "Default")
      (node (ref "TSB58") (pin "2") (pinfunction "A_2") (pintype "passive"))
    )
    (net (code "28") (name "/A_B27") (class "Default")
      (node (ref "TSB65") (pin "2") (pinfunction "A_2") (pintype "passive"))
    )
    (net (code "29") (name "/A_B28") (class "Default")
      (node (ref "TSB72") (pin "2") (pinfunction "A_2") (pintype "passive"))
    )
    (net (code "30") (name "/A_B29") (class "Default")
      (node (ref "TSB79") (pin "2") (pinfunction "A_2") (pintype "passive"))
    )
    (net (code "31") (name "/A_B30") (class "Default")
      (node (ref "TSB86") (pin "2") (pinfunction "A_2") (pintype "passive"))
    )
    (net (code "32") (name "/A_B31") (class "Default")
      (node (ref "TSB93") (pin "2") (pinfunction "A_2") (pintype "passive"))
    )
    (net (code "33") (name "/A_B32") (class "Default")
      (node (ref "TSB100") (pin "2") (pinfunction "A_2") (pintype "passive"))
    )
    (net (code "34") (name "/A_B33") (class "Default")
      (node (ref "TSB107") (pin "2") (pinfunction "A_2") (pintype "passive"))
    )
    (net (code "35") (name "/A_B34") (class "Default")
      (node (ref "TSB114") (pin "2") (pinfunction "A_2") (pintype "passive"))
    )
    (net (code "36") (name "/A_B35") (class "Default")
      (node (ref "TSB121") (pin "2") (pinfunction "A_2") (pintype "passive"))
    )
    (net (code "37") (name "/A_B36") (class "Default")
      (node (ref "TSB3") (pin "2") (pinfunction "A_2") (pintype "passive"))
    )
    (net (code "38") (name "/A_B37") (class "Default")
      (node (ref "TSB10") (pin "2") (pinfunction "A_2") (pintype "passive"))
    )
    (net (code "39") (name "/A_B38") (class "Default")
      (node (ref "TSB17") (pin "2") (pinfunction "A_2") (pintype "passive"))
    )
    (net (code "40") (name "/A_B39") (class "Default")
      (node (ref "TSB24") (pin "2") (pinfunction "A_2") (pintype "passive"))
    )
    (net (code "41") (name "/A_B40") (class "Default")
      (node (ref "TSB31") (pin "2") (pinfunction "A_2") (pintype "passive"))
    )
    (net (code "42") (name "/A_B41") (class "Default")
      (node (ref "TSB38") (pin "2") (pinfunction "A_2") (pintype "passive"))
    )
    (net (code "43") (name "/A_B42") (class "Default")
      (node (ref "TSB45") (pin "2") (pinfunction "A_2") (pintype "passive"))
    )
    (net (code "44") (name "/A_B43") (class "Default")
      (node (ref "TSB52") (pin "2") (pinfunction "A_2") (pintype "passive"))
    )
    (net (code "45") (name "/A_B44") (class "Default")
      (node (ref "TSB59") (pin "2") (pinfunction "A_2") (pintype "passive"))
    )
    (net (code "46") (name "/A_B45") (class "Default")
      (node (ref "TSB66") (pin "2") (pinfunction "A_2") (pintype "passive"))
    )
    (net (code "47") (name "/A_B46") (class "Default")
      (node (ref "TSB73") (pin "2") (pinfunction "A_2") (pintype "passive"))
    )
    (net (code "48") (name "/A_B47") (class "Default")
      (node (ref "TSB80") (pin "2") (pinfunction "A_2") (pintype "passive"))
    )
    (net (code "49") (name "/A_B48") (class "Default")
      (node (ref "TSB87") (pin "2") (pinfunction "A_2") (pintype "passive"))
    )
    (net (code "50") (name "/A_B49") (class "Default")
      (node (ref "TSB94") (pin "2") (pinfunction "A_2") (pintype "passive"))
    )
    (net (code "51") (name "/A_B50") (class "Default")
      (node (ref "TSB101") (pin "2") (pinfunction "A_2") (pintype "passive"))
    )
    (net (code "52") (name "/A_B51") (class "Default")
      (node (ref "TSB108") (pin "2") (pinfunction "A_2") (pintype "passive"))
    )
    (net (code "53") (name "/A_B52") (class "Default")
      (node (ref "TSB115") (pin "2") (pinfunction "A_2") (pintype "passive"))
    )
    (net (code "54") (name "/A_B53") (class "Default")
      (node (ref "TSB122") (pin "2") (pinfunction "A_2") (pintype "passive"))
    )
    (net (code "55") (name "/A_B54") (class "Default")
      (node (ref "TSB4") (pin "2") (pinfunction "A_2") (pintype "passive"))
    )
    (net (code "56") (name "/A_B55") (class "Default")
      (node (ref "TSB11") (pin "2") (pinfunction "A_2") (pintype "passive"))
    )
    (net (code "57") (name "/A_B56") (class "Default")
      (node (ref "TSB18") (pin "2") (pinfunction "A_2") (pintype "passive"))
    )
    (net (code "58") (name "/A_B57") (class "Default")
      (node (ref "TSB25") (pin "2") (pinfunction "A_2") (pintype "passive"))
    )
    (net (code "59") (name "/A_B58") (class "Default")
      (node (ref "TSB32") (pin "2") (pinfunction "A_2") (pintype "passive"))
    )
    (net (code "60") (name "/A_B59") (class "Default")
      (node (ref "TSB39") (pin "2") (pinfunction "A_2") (pintype "passive"))
    )
    (net (code "61") (name "/A_B60") (class "Default")
      (node (ref "TSB46") (pin "2") (pinfunction "A_2") (pintype "passive"))
    )
    (net (code "62") (name "/A_B61") (class "Default")
      (node (ref "TSB53") (pin "2") (pinfunction "A_2") (pintype "passive"))
    )
    (net (code "63") (name "/A_B62") (class "Default")
      (node (ref "TSB60") (pin "2") (pinfunction "A_2") (pintype "passive"))
    )
    (net (code "64") (name "/A_B63") (class "Default")
      (node (ref "TSB67") (pin "2") (pinfunction "A_2") (pintype "passive"))
    )
    (net (code "65") (name "/A_B64") (class "Default")
      (node (ref "TSB74") (pin "2") (pinfunction "A_2") (pintype "passive"))
    )
    (net (code "66") (name "/A_B65") (class "Default")
      (node (ref "TSB81") (pin "2") (pinfunction "A_2") (pintype "passive"))
    )
    (net (code "67") (name "/A_B66") (class "Default")
      (node (ref "TSB88") (pin "2") (pinfunction "A_2") (pintype "passive"))
    )
    (net (code "68") (name "/A_B67") (class "Default")
      (node (ref "TSB95") (pin "2") (pinfunction "A_2") (pintype "passive"))
    )
    (net (code "69") (name "/A_B68") (class "Default")
      (node (ref "TSB102") (pin "2") (pinfunction "A_2") (pintype "passive"))
    )
    (net (code "70") (name "/A_B69") (class "Default")
      (node (ref "TSB109") (pin "2") (pinfunction "A_2") (pintype "passive"))
    )
    (net (code "71") (name "/A_B70") (class "Default")
      (node (ref "TSB116") (pin "2") (pinfunction "A_2") (pintype "passive"))
    )
    (net (code "72") (name "/A_B71") (class "Default")
      (node (ref "TSB123") (pin "2") (pinfunction "A_2") (pintype "passive"))
    )
    (net (code "73") (name "/A_B72") (class "Default")
      (node (ref "TSB5") (pin "2") (pinfunction "A_2") (pintype "passive"))
    )
    (net (code "74") (name "/A_B73") (class "Default")
      (node (ref "TSB12") (pin "2") (pinfunction "A_2") (pintype "passive"))
    )
    (net (code "75") (name "/A_B74") (class "Default")
      (node (ref "TSB19") (pin "2") (pinfunction "A_2") (pintype "passive"))
    )
    (net (code "76") (name "/A_B75") (class "Default")
      (node (ref "TSB26") (pin "2") (pinfunction "A_2") (pintype "passive"))
    )
    (net (code "77") (name "/A_B76") (class "Default")
      (node (ref "TSB33") (pin "2") (pinfunction "A_2") (pintype "passive"))
    )
    (net (code "78") (name "/A_B77") (class "Default")
      (node (ref "TSB40") (pin "2") (pinfunction "A_2") (pintype "passive"))
    )
    (net (code "79") (name "/A_B78") (class "Default")
      (node (ref "TSB47") (pin "2") (pinfunction "A_2") (pintype "passive"))
    )
    (net (code "80") (name "/A_B79") (class "Default")
      (node (ref "TSB54") (pin "2") (pinfunction "A_2") (pintype "passive"))
    )
    (net (code "81") (name "/A_B80") (class "Default")
      (node (ref "TSB61") (pin "2") (pinfunction "A_2") (pintype "passive"))
    )
    (net (code "82") (name "/A_B81") (class "Default")
      (node (ref "TSB68") (pin "2") (pinfunction "A_2") (pintype "passive"))
    )
    (net (code "83") (name "/A_B82") (class "Default")
      (node (ref "TSB75") (pin "2") (pinfunction "A_2") (pintype "passive"))
    )
    (net (code "84") (name "/A_B83") (class "Default")
      (node (ref "TSB82") (pin "2") (pinfunction "A_2") (pintype "passive"))
    )
    (net (code "85") (name "/A_B84") (class "Default")
      (node (ref "TSB89") (pin "2") (pinfunction "A_2") (pintype "passive"))
    )
    (net (code "86") (name "/A_B85") (class "Default")
      (node (ref "TSB96") (pin "2") (pinfunction "A_2") (pintype "passive"))
    )
    (net (code "87") (name "/A_B86") (class "Default")
      (node (ref "TSB103") (pin "2") (pinfunction "A_2") (pintype "passive"))
    )
    (net (code "88") (name "/A_B87") (class "Default")
      (node (ref "TSB110") (pin "2") (pinfunction "A_2") (pintype "passive"))
    )
    (net (code "89") (name "/A_B88") (class "Default")
      (node (ref "TSB117") (pin "2") (pinfunction "A_2") (pintype "passive"))
    )
    (net (code "90") (name "/A_B89") (class "Default")
      (node (ref "TSB124") (pin "2") (pinfunction "A_2") (pintype "passive"))
    )
    (net (code "91") (name "/A_B90") (class "Default")
      (node (ref "TSB6") (pin "2") (pinfunction "A_2") (pintype "passive"))
    )
    (net (code "92") (name "/A_B91") (class "Default")
      (node (ref "TSB13") (pin "2") (pinfunction "A_2") (pintype "passive"))
    )
    (net (code "93") (name "/A_B92") (class "Default")
      (node (ref "TSB20") (pin "2") (pinfunction "A_2") (pintype "passive"))
    )
    (net (code "94") (name "/A_B93") (class "Default")
      (node (ref "TSB27") (pin "2") (pinfunction "A_2") (pintype "passive"))
    )
    (net (code "95") (name "/A_B94") (class "Default")
      (node (ref "TSB34") (pin "2") (pinfunction "A_2") (pintype "passive"))
    )
    (net (code "96") (name "/A_B95") (class "Default")
      (node (ref "TSB41") (pin "2") (pinfunction "A_2") (pintype "passive"))
    )
    (net (code "97") (name "/A_B96") (class "Default")
      (node (ref "TSB48") (pin "2") (pinfunction "A_2") (pintype "passive"))
    )
    (net (code "98") (name "/A_B97") (class "Default")
      (node (ref "TSB55") (pin "2") (pinfunction "A_2") (pintype "passive"))
    )
    (net (code "99") (name "/A_B98") (class "Default")
      (node (ref "TSB62") (pin "2") (pinfunction "A_2") (pintype "passive"))
    )
    (net (code "100") (name "/A_B99") (class "Default")
      (node (ref "TSB69") (pin "2") (pinfunction "A_2") (pintype "passive"))
    )
    (net (code "101") (name "/A_B100") (class "Default")
      (node (ref "TSB76") (pin "2") (pinfunction "A_2") (pintype "passive"))
    )
    (net (code "102") (name "/A_B101") (class "Default")
      (node (ref "TSB83") (pin "2") (pinfunction "A_2") (pintype "passive"))
    )
    (net (code "103") (name "/A_B102") (class "Default")
      (node (ref "TSB90") (pin "2") (pinfunction "A_2") (pintype "passive"))
    )
    (net (code "104") (name "/A_B103") (class "Default")
      (node (ref "TSB97") (pin "2") (pinfunction "A_2") (pintype "passive"))
    )
    (net (code "105") (name "/A_B104") (class "Default")
      (node (ref "TSB104") (pin "2") (pinfunction "A_2") (pintype "passive"))
    )
    (net (code "106") (name "/A_B105") (class "Default")
      (node (ref "TSB111") (pin "2") (pinfunction "A_2") (pintype "passive"))
    )
    (net (code "107") (name "/A_B106") (class "Default")
      (node (ref "TSB118") (pin "2") (pinfunction "A_2") (pintype "passive"))
    )
    (net (code "108") (name "/A_B107") (class "Default")
      (node (ref "TSB125") (pin "2") (pinfunction "A_2") (pintype "passive"))
    )
    (net (code "109") (name "/A_B108") (class "Default")
      (node (ref "TSB7") (pin "2") (pinfunction "A_2") (pintype "passive"))
    )
    (net (code "110") (name "/A_B109") (class "Default")
      (node (ref "TSB14") (pin "2") (pinfunction "A_2") (pintype "passive"))
    )
    (net (code "111") (name "/A_B110") (class "Default")
      (node (ref "TSB21") (pin "2") (pinfunction "A_2") (pintype "passive"))
    )
    (net (code "112") (name "/A_B111") (class "Default")
      (node (ref "TSB28") (pin "2") (pinfunction "A_2") (pintype "passive"))
    )
    (net (code "113") (name "/A_B112") (class "Default")
      (node (ref "TSB35") (pin "2") (pinfunction "A_2") (pintype "passive"))
    )
    (net (code "114") (name "/A_B113") (class "Default")
      (node (ref "TSB42") (pin "2") (pinfunction "A_2") (pintype "passive"))
    )
    (net (code "115") (name "/A_B114") (class "Default")
      (node (ref "TSB49") (pin "2") (pinfunction "A_2") (pintype "passive"))
    )
    (net (code "116") (name "/A_B115") (class "Default")
      (node (ref "TSB56") (pin "2") (pinfunction "A_2") (pintype "passive"))
    )
    (net (code "117") (name "/A_B116") (class "Default")
      (node (ref "TSB63") (pin "2") (pinfunction "A_2") (pintype "passive"))
    )
    (net (code "118") (name "/A_B117") (class "Default")
      (node (ref "TSB70") (pin "2") (pinfunction "A_2") (pintype "passive"))
    )
    (net (code "119") (name "/A_B118") (class "Default")
      (node (ref "TSB77") (pin "2") (pinfunction "A_2") (pintype "passive"))
    )
    (net (code "120") (name "/A_B119") (class "Default")
      (node (ref "TSB84") (pin "2") (pinfunction "A_2") (pintype "passive"))
    )
    (net (code "121") (name "/A_B120") (class "Default")
      (node (ref "TSB91") (pin "2") (pinfunction "A_2") (pintype "passive"))
    )
    (net (code "122") (name "/A_B121") (class "Default")
      (node (ref "TSB98") (pin "2") (pinfunction "A_2") (pintype "passive"))
    )
    (net (code "123") (name "/A_B122") (class "Default")
      (node (ref "TSB105") (pin "2") (pinfunction "A_2") (pintype "passive"))
    )
    (net (code "124") (name "/A_B123") (class "Default")
      (node (ref "TSB112") (pin "2") (pinfunction "A_2") (pintype "passive"))
    )
    (net (code "125") (name "/A_B124") (class "Default")
      (node (ref "TSB119") (pin "2") (pinfunction "A_2") (pintype "passive"))
    )
    (net (code "126") (name "/A_B125") (class "Default")
      (node (ref "TSB126") (pin "2") (pinfunction "A_2") (pintype "passive"))
    )
    (net (code "135") (name "/TSB_VCC_B") (class "Default")
      (node (ref "TSB1") (pin "5") (pinfunction "Vcc_5") (pintype "passive"))
      (node (ref "TSB10") (pin "5") (pinfunction "Vcc_5") (pintype "passive"))
      (node (ref "TSB100") (pin "5") (pinfunction "Vcc_5") (pintype "passive"))
      (node (ref "TSB101") (pin "5") (pinfunction "Vcc_5") (pintype "passive"))
      (node (ref "TSB102") (pin "5") (pinfunction "Vcc_5") (pintype "passive"))
      (node (ref "TSB103") (pin "5") (pinfunction "Vcc_5") (pintype "passive"))
      (node (ref "TSB104") (pin "5") (pinfunction "Vcc_5") (pintype "passive"))
      (node (ref "TSB105") (pin "5") (pinfunction "Vcc_5") (pintype "passive"))
      (node (ref "TSB106") (pin "5") (pinfunction "Vcc_5") (pintype "passive"))
      (node (ref "TSB107") (pin "5") (pinfunction "Vcc_5") (pintype "passive"))
      (node (ref "TSB108") (pin "5") (pinfunction "Vcc_5") (pintype "passive"))
      (node (ref "TSB109") (pin "5") (pinfunction "Vcc_5") (pintype "passive"))
      (node (ref "TSB11") (pin "5") (pinfunction "Vcc_5") (pintype "passive"))
      (node (ref "TSB110") (pin "5") (pinfunction "Vcc_5") (pintype "passive"))
      (node (ref "TSB111") (pin "5") (pinfunction "Vcc_5") (pintype "passive"))
      (node (ref "TSB112") (pin "5") (pinfunction "Vcc_5") (pintype "passive"))
      (node (ref "TSB113") (pin "5") (pinfunction "Vcc_5") (pintype "passive"))
      (node (ref "TSB114") (pin "5") (pinfunction "Vcc_5") (pintype "passive"))
      (node (ref "TSB115") (pin "5") (pinfunction "Vcc_5") (pintype "passive"))
      (node (ref "TSB116") (pin "5") (pinfunction "Vcc_5") (pintype "passive"))
      (node (ref "TSB117") (pin "5") (pinfunction "Vcc_5") (pintype "passive"))
      (node (ref "TSB118") (pin "5") (pinfunction "Vcc_5") (pintype "passive"))
      (node (ref "TSB119") (pin "5") (pinfunction "Vcc_5") (pintype "passive"))
      (node (ref "TSB12") (pin "5") (pinfunction "Vcc_5") (pintype "passive"))
      (node (ref "TSB126") (pin "5") (pinfunction "Vcc_5") (pintype "passive"))
      (node (ref "TSB13") (pin "5") (pinfunction "Vcc_5") (pintype "passive"))
      (node (ref "TSB14") (pin "5") (pinfunction "Vcc_5") (pintype "passive"))
      (node (ref "TSB15") (pin "5") (pinfunction "Vcc_5") (pintype "passive"))
      (node (ref "TSB16") (pin "5") (pinfunction "Vcc_5") (pintype "passive"))
      (node (ref "TSB17") (pin "5") (pinfunction "Vcc_5") (pintype "passive"))
      (node (ref "TSB18") (pin "5") (pinfunction "Vcc_5") (pintype "passive"))
      (node (ref "TSB19") (pin "5") (pinfunction "Vcc_5") (pintype "passive"))
      (node (ref "TSB2") (pin "5") (pinfunction "Vcc_5") (pintype "passive"))
      (node (ref "TSB20") (pin "5") (pinfunction "Vcc_5") (pintype "passive"))
      (node (ref "TSB21") (pin "5") (pinfunction "Vcc_5") (pintype "passive"))
      (node (ref "TSB22") (pin "5") (pinfunction "Vcc_5") (pintype "passive"))
      (node (ref "TSB23") (pin "5") (pinfunction "Vcc_5") (pintype "passive"))
      (node (ref "TSB24") (pin "5") (pinfunction "Vcc_5") (pintype "passive"))
      (node (ref "TSB25") (pin "5") (pinfunction "Vcc_5") (pintype "passive"))
      (node (ref "TSB26") (pin "5") (pinfunction "Vcc_5") (pintype "passive"))
      (node (ref "TSB27") (pin "5") (pinfunction "Vcc_5") (pintype "passive"))
      (node (ref "TSB28") (pin "5") (pinfunction "Vcc_5") (pintype "passive"))
      (node (ref "TSB29") (pin "5") (pinfunction "Vcc_5") (pintype "passive"))
      (node (ref "TSB3") (pin "5") (pinfunction "Vcc_5") (pintype "passive"))
      (node (ref "TSB30") (pin "5") (pinfunction "Vcc_5") (pintype "passive"))
      (node (ref "TSB31") (pin "5") (pinfunction "Vcc_5") (pintype "passive"))
      (node (ref "TSB32") (pin "5") (pinfunction "Vcc_5") (pintype "passive"))
      (node (ref "TSB33") (pin "5") (pinfunction "Vcc_5") (pintype "passive"))
      (node (ref "TSB34") (pin "5") (pinfunction "Vcc_5") (pintype "passive"))
      (node (ref "TSB35") (pin "5") (pinfunction "Vcc_5") (pintype "passive"))
      (node (ref "TSB36") (pin "5") (pinfunction "Vcc_5") (pintype "passive"))
      (node (ref "TSB37") (pin "5") (pinfunction "Vcc_5") (pintype "passive"))
      (node (ref "TSB38") (pin "5") (pinfunction "Vcc_5") (pintype "passive"))
      (node (ref "TSB39") (pin "5") (pinfunction "Vcc_5") (pintype "passive"))
      (node (ref "TSB4") (pin "5") (pinfunction "Vcc_5") (pintype "passive"))
      (node (ref "TSB40") (pin "5") (pinfunction "Vcc_5") (pintype "passive"))
      (node (ref "TSB41") (pin "5") (pinfunction "Vcc_5") (pintype "passive"))
      (node (ref "TSB42") (pin "5") (pinfunction "Vcc_5") (pintype "passive"))
      (node (ref "TSB43") (pin "5") (pinfunction "Vcc_5") (pintype "passive"))
      (node (ref "TSB44") (pin "5") (pinfunction "Vcc_5") (pintype "passive"))
      (node (ref "TSB45") (pin "5") (pinfunction "Vcc_5") (pintype "passive"))
      (node (ref "TSB46") (pin "5") (pinfunction "Vcc_5") (pintype "passive"))
      (node (ref "TSB47") (pin "5") (pinfunction "Vcc_5") (pintype "passive"))
      (node (ref "TSB48") (pin "5") (pinfunction "Vcc_5") (pintype "passive"))
      (node (ref "TSB49") (pin "5") (pinfunction "Vcc_5") (pintype "passive"))
      (node (ref "TSB5") (pin "5") (pinfunction "Vcc_5") (pintype "passive"))
      (node (ref "TSB50") (pin "5") (pinfunction "Vcc_5") (pintype "passive"))
      (node (ref "TSB51") (pin "5") (pinfunction "Vcc_5") (pintype "passive"))
      (node (ref "TSB52") (pin "5") (pinfunction "Vcc_5") (pintype "passive"))
      (node (ref "TSB53") (pin "5") (pinfunction "Vcc_5") (pintype "passive"))
      (node (ref "TSB54") (pin "5") (pinfunction "Vcc_5") (pintype "passive"))
      (node (ref "TSB55") (pin "5") (pinfunction "Vcc_5") (pintype "passive"))
      (node (ref "TSB56") (pin "5") (pinfunction "Vcc_5") (pintype "passive"))
      (node (ref "TSB57") (pin "5") (pinfunction "Vcc_5") (pintype "passive"))
      (node (ref "TSB58") (pin "5") (pinfunction "Vcc_5") (pintype "passive"))
      (node (ref "TSB59") (pin "5") (pinfunction "Vcc_5") (pintype "passive"))
      (node (ref "TSB6") (pin "5") (pinfunction "Vcc_5") (pintype "passive"))
      (node (ref "TSB60") (pin "5") (pinfunction "Vcc_5") (pintype "passive"))
      (node (ref "TSB61") (pin "5") (pinfunction "Vcc_5") (pintype "passive"))
      (node (ref "TSB62") (pin "5") (pinfunction "Vcc_5") (pintype "passive"))
      (node (ref "TSB63") (pin "5") (pinfunction "Vcc_5") (pintype "passive"))
      (node (ref "TSB64") (pin "5") (pinfunction "Vcc_5") (pintype "passive"))
      (node (ref "TSB65") (pin "5") (pinfunction "Vcc_5") (pintype "passive"))
      (node (ref "TSB66") (pin "5") (pinfunction "Vcc_5") (pintype "passive"))
      (node (ref "TSB67") (pin "5") (pinfunction "Vcc_5") (pintype "passive"))
      (node (ref "TSB68") (pin "5") (pinfunction "Vcc_5") (pintype "passive"))
      (node (ref "TSB69") (pin "5") (pinfunction "Vcc_5") (pintype "passive"))
      (node (ref "TSB7") (pin "5") (pinfunction "Vcc_5") (pintype "passive"))
      (node (ref "TSB70") (pin "5") (pinfunction "Vcc_5") (pintype "passive"))
      (node (ref "TSB71") (pin "5") (pinfunction "Vcc_5") (pintype "passive"))
      (node (ref "TSB72") (pin "5") (pinfunction "Vcc_5") (pintype "passive"))
      (node (ref "TSB73") (pin "5") (pinfunction "Vcc_5") (pintype "passive"))
      (node (ref "TSB74") (pin "5") (pinfunction "Vcc_5") (pintype "passive"))
      (node (ref "TSB75") (pin "5") (pinfunction "Vcc_5") (pintype "passive"))
      (node (ref "TSB76") (pin "5") (pinfunction "Vcc_5") (pintype "passive"))
      (node (ref "TSB77") (pin "5") (pinfunction "Vcc_5") (pintype "passive"))
      (node (ref "TSB78") (pin "5") (pinfunction "Vcc_5") (pintype "passive"))
      (node (ref "TSB79") (pin "5") (pinfunction "Vcc_5") (pintype "passive"))
      (node (ref "TSB8") (pin "5") (pinfunction "Vcc_5") (pintype "passive"))
      (node (ref "TSB80") (pin "5") (pinfunction "Vcc_5") (pintype "passive"))
      (node (ref "TSB81") (pin "5") (pinfunction "Vcc_5") (pintype "passive"))
      (node (ref "TSB82") (pin "5") (pinfunction "Vcc_5") (pintype "passive"))
      (node (ref "TSB83") (pin "5") (pinfunction "Vcc_5") (pintype "passive"))
      (node (ref "TSB84") (pin "5") (pinfunction "Vcc_5") (pintype "passive"))
      (node (ref "TSB85") (pin "5") (pinfunction "Vcc_5") (pintype "passive"))
      (node (ref "TSB86") (pin "5") (pinfunction "Vcc_5") (pintype "passive"))
      (node (ref "TSB87") (pin "5") (pinfunction "Vcc_5") (pintype "passive"))
      (node (ref "TSB88") (pin "5") (pinfunction "Vcc_5") (pintype "passive"))
      (node (ref "TSB89") (pin "5") (pinfunction "Vcc_5") (pintype "passive"))
      (node (ref "TSB9") (pin "5") (pinfunction "Vcc_5") (pintype "passive"))
      (node (ref "TSB90") (pin "5") (pinfunction "Vcc_5") (pintype "passive"))
      (node (ref "TSB91") (pin "5") (pinfunction "Vcc_5") (pintype "passive"))
      (node (ref "TSB92") (pin "5") (pinfunction "Vcc_5") (pintype "passive"))
      (node (ref "TSB93") (pin "5") (pinfunction "Vcc_5") (pintype "passive"))
      (node (ref "TSB94") (pin "5") (pinfunction "Vcc_5") (pintype "passive"))
      (node (ref "TSB95") (pin "5") (pinfunction "Vcc_5") (pintype "passive"))
      (node (ref "TSB96") (pin "5") (pinfunction "Vcc_5") (pintype "passive"))
      (node (ref "TSB97") (pin "5") (pinfunction "Vcc_5") (pintype "passive"))
      (node (ref "TSB98") (pin "5") (pinfunction "Vcc_5") (pintype "passive"))
      (node (ref "TSB99") (pin "5") (pinfunction "Vcc_5") (pintype "passive"))
    )
    (net (code "136") (name "/Y_B0") (class "Default")
      (node (ref "TSB1") (pin "4") (pinfunction "Y_4") (pintype "passive"))
    )
    (net (code "137") (name "/Y_B1") (class "Default")
      (node (ref "TSB8") (pin "4") (pinfunction "Y_4") (pintype "passive"))
    )
    (net (code "138") (name "/Y_B2") (class "Default")
      (node (ref "TSB15") (pin "4") (pinfunction "Y_4") (pintype "passive"))
    )
    (net (code "139") (name "/Y_B3") (class "Default")
      (node (ref "TSB22") (pin "4") (pinfunction "Y_4") (pintype "passive"))
    )
    (net (code "140") (name "/Y_B4") (class "Default")
      (node (ref "TSB29") (pin "4") (pinfunction "Y_4") (pintype "passive"))
    )
    (net (code "141") (name "/Y_B5") (class "Default")
      (node (ref "TSB36") (pin "4") (pinfunction "Y_4") (pintype "passive"))
    )
    (net (code "142") (name "/Y_B6") (class "Default")
      (node (ref "TSB43") (pin "4") (pinfunction "Y_4") (pintype "passive"))
    )
    (net (code "143") (name "/Y_B7") (class "Default")
      (node (ref "TSB50") (pin "4") (pinfunction "Y_4") (pintype "passive"))
    )
    (net (code "144") (name "/Y_B8") (class "Default")
      (node (ref "TSB57") (pin "4") (pinfunction "Y_4") (pintype "passive"))
    )
    (net (code "145") (name "/Y_B9") (class "Default")
      (node (ref "TSB64") (pin "4") (pinfunction "Y_4") (pintype "passive"))
    )
    (net (code "146") (name "/Y_B10") (class "Default")
      (node (ref "TSB71") (pin "4") (pinfunction "Y_4") (pintype "passive"))
    )
    (net (code "147") (name "/Y_B11") (class "Default")
      (node (ref "TSB78") (pin "4") (pinfunction "Y_4") (pintype "passive"))
    )
    (net (code "148") (name "/Y_B12") (class "Default")
      (node (ref "TSB85") (pin "4") (pinfunction "Y_4") (pintype "passive"))
    )
    (net (code "149") (name "/Y_B13") (class "Default")
      (node (ref "TSB92") (pin "4") (pinfunction "Y_4") (pintype "passive"))
    )
    (net (code "150") (name "/Y_B14") (class "Default")
      (node (ref "TSB99") (pin "4") (pinfunction "Y_4") (pintype "passive"))
    )
    (net (code "151") (name "/Y_B15") (class "Default")
      (node (ref "TSB106") (pin "4") (pinfunction "Y_4") (pintype "passive"))
    )
    (net (code "152") (name "/Y_B16") (class "Default")
      (node (ref "TSB113") (pin "4") (pinfunction "Y_4") (pintype "passive"))
    )
    (net (code "153") (name "/Y_B17") (class "Default")
      (node (ref "TSB120") (pin "4") (pinfunction "Y_4") (pintype "passive"))
    )
    (net (code "154") (name "/Y_B18") (class "Default")
      (node (ref "TSB2") (pin "4") (pinfunction "Y_4") (pintype "passive"))
    )
    (net (code "155") (name "/Y_B19") (class "Default")
      (node (ref "TSB9") (pin "4") (pinfunction "Y_4") (pintype "passive"))
    )
    (net (code "156") (name "/Y_B20") (class "Default")
      (node (ref "TSB16") (pin "4") (pinfunction "Y_4") (pintype "passive"))
    )
    (net (code "157") (name "/Y_B21") (class "Default")
      (node (ref "TSB23") (pin "4") (pinfunction "Y_4") (pintype "passive"))
    )
    (net (code "158") (name "/Y_B22") (class "Default")
      (node (ref "TSB30") (pin "4") (pinfunction "Y_4") (pintype "passive"))
    )
    (net (code "159") (name "/Y_B23") (class "Default")
      (node (ref "TSB37") (pin "4") (pinfunction "Y_4") (pintype "passive"))
    )
    (net (code "160") (name "/Y_B24") (class "Default")
      (node (ref "TSB44") (pin "4") (pinfunction "Y_4") (pintype "passive"))
    )
    (net (code "161") (name "/Y_B25") (class "Default")
      (node (ref "TSB51") (pin "4") (pinfunction "Y_4") (pintype "passive"))
    )
    (net (code "162") (name "/Y_B26") (class "Default")
      (node (ref "TSB58") (pin "4") (pinfunction "Y_4") (pintype "passive"))
    )
    (net (code "163") (name "/Y_B27") (class "Default")
      (node (ref "TSB65") (pin "4") (pinfunction "Y_4") (pintype "passive"))
    )
    (net (code "164") (name "/Y_B28") (class "Default")
      (node (ref "TSB72") (pin "4") (pinfunction "Y_4") (pintype "passive"))
    )
    (net (code "165") (name "/Y_B29") (class "Default")
      (node (ref "TSB79") (pin "4") (pinfunction "Y_4") (pintype "passive"))
    )
    (net (code "166") (name "/Y_B30") (class "Default")
      (node (ref "TSB86") (pin "4") (pinfunction "Y_4") (pintype "passive"))
    )
    (net (code "167") (name "/Y_B31") (class "Default")
      (node (ref "TSB93") (pin "4") (pinfunction "Y_4") (pintype "passive"))
    )
    (net (code "168") (name "/Y_B32") (class "Default")
      (node (ref "TSB100") (pin "4") (pinfunction "Y_4") (pintype "passive"))
    )
    (net (code "169") (name "/Y_B33") (class "Default")
      (node (ref "TSB107") (pin "4") (pinfunction "Y_4") (pintype "passive"))
    )
    (net (code "170") (name "/Y_B34") (class "Default")
      (node (ref "TSB114") (pin "4") (pinfunction "Y_4") (pintype "passive"))
    )
    (net (code "171") (name "/Y_B35") (class "Default")
      (node (ref "TSB121") (pin "4") (pinfunction "Y_4") (pintype "passive"))
    )
    (net (code "172") (name "/Y_B36") (class "Default")
      (node (ref "TSB3") (pin "4") (pinfunction "Y_4") (pintype "passive"))
    )
    (net (code "173") (name "/Y_B37") (class "Default")
      (node (ref "TSB10") (pin "4") (pinfunction "Y_4") (pintype "passive"))
    )
    (net (code "174") (name "/Y_B38") (class "Default")
      (node (ref "TSB17") (pin "4") (pinfunction "Y_4") (pintype "passive"))
    )
    (net (code "175") (name "/Y_B39") (class "Default")
      (node (ref "TSB24") (pin "4") (pinfunction "Y_4") (pintype "passive"))
    )
    (net (code "176") (name "/Y_B40") (class "Default")
      (node (ref "TSB31") (pin "4") (pinfunction "Y_4") (pintype "passive"))
    )
    (net (code "177") (name "/Y_B41") (class "Default")
      (node (ref "TSB38") (pin "4") (pinfunction "Y_4") (pintype "passive"))
    )
    (net (code "178") (name "/Y_B42") (class "Default")
      (node (ref "TSB45") (pin "4") (pinfunction "Y_4") (pintype "passive"))
    )
    (net (code "179") (name "/Y_B43") (class "Default")
      (node (ref "TSB52") (pin "4") (pinfunction "Y_4") (pintype "passive"))
    )
    (net (code "180") (name "/Y_B44") (class "Default")
      (node (ref "TSB59") (pin "4") (pinfunction "Y_4") (pintype "passive"))
    )
    (net (code "181") (name "/Y_B45") (class "Default")
      (node (ref "TSB66") (pin "4") (pinfunction "Y_4") (pintype "passive"))
    )
    (net (code "182") (name "/Y_B46") (class "Default")
      (node (ref "TSB73") (pin "4") (pinfunction "Y_4") (pintype "passive"))
    )
    (net (code "183") (name "/Y_B47") (class "Default")
      (node (ref "TSB80") (pin "4") (pinfunction "Y_4") (pintype "passive"))
    )
    (net (code "184") (name "/Y_B48") (class "Default")
      (node (ref "TSB87") (pin "4") (pinfunction "Y_4") (pintype "passive"))
    )
    (net (code "185") (name "/Y_B49") (class "Default")
      (node (ref "TSB94") (pin "4") (pinfunction "Y_4") (pintype "passive"))
    )
    (net (code "186") (name "/Y_B50") (class "Default")
      (node (ref "TSB101") (pin "4") (pinfunction "Y_4") (pintype "passive"))
    )
    (net (code "187") (name "/Y_B51") (class "Default")
      (node (ref "TSB108") (pin "4") (pinfunction "Y_4") (pintype "passive"))
    )
    (net (code "188") (name "/Y_B52") (class "Default")
      (node (ref "TSB115") (pin "4") (pinfunction "Y_4") (pintype "passive"))
    )
    (net (code "189") (name "/Y_B53") (class "Default")
      (node (ref "TSB122") (pin "4") (pinfunction "Y_4") (pintype "passive"))
    )
    (net (code "190") (name "/Y_B54") (class "Default")
      (node (ref "TSB4") (pin "4") (pinfunction "Y_4") (pintype "passive"))
    )
    (net (code "191") (name "/Y_B55") (class "Default")
      (node (ref "TSB11") (pin "4") (pinfunction "Y_4") (pintype "passive"))
    )
    (net (code "192") (name "/Y_B56") (class "Default")
      (node (ref "TSB18") (pin "4") (pinfunction "Y_4") (pintype "passive"))
    )
    (net (code "193") (name "/Y_B57") (class "Default")
      (node (ref "TSB25") (pin "4") (pinfunction "Y_4") (pintype "passive"))
    )
    (net (code "194") (name "/Y_B58") (class "Default")
      (node (ref "TSB32") (pin "4") (pinfunction "Y_4") (pintype "passive"))
    )
    (net (code "195") (name "/Y_B59") (class "Default")
      (node (ref "TSB39") (pin "4") (pinfunction "Y_4") (pintype "passive"))
    )
    (net (code "196") (name "/Y_B60") (class "Default")
      (node (ref "TSB46") (pin "4") (pinfunction "Y_4") (pintype "passive"))
    )
    (net (code "197") (name "/Y_B61") (class "Default")
      (node (ref "TSB53") (pin "4") (pinfunction "Y_4") (pintype "passive"))
    )
    (net (code "198") (name "/Y_B62") (class "Default")
      (node (ref "TSB60") (pin "4") (pinfunction "Y_4") (pintype "passive"))
    )
    (net (code "199") (name "/Y_B63") (class "Default")
      (node (ref "TSB67") (pin "4") (pinfunction "Y_4") (pintype "passive"))
    )
    (net (code "200") (name "/Y_B64") (class "Default")
      (node (ref "TSB74") (pin "4") (pinfunction "Y_4") (pintype "passive"))
    )
    (net (code "201") (name "/Y_B65") (class "Default")
      (node (ref "TSB81") (pin "4") (pinfunction "Y_4") (pintype "passive"))
    )
    (net (code "202") (name "/Y_B66") (class "Default")
      (node (ref "TSB88") (pin "4") (pinfunction "Y_4") (pintype "passive"))
    )
    (net (code "203") (name "/Y_B67") (class "Default")
      (node (ref "TSB95") (pin "4") (pinfunction "Y_4") (pintype "passive"))
    )
    (net (code "204") (name "/Y_B68") (class "Default")
      (node (ref "TSB102") (pin "4") (pinfunction "Y_4") (pintype "passive"))
    )
    (net (code "205") (name "/Y_B69") (class "Default")
      (node (ref "TSB109") (pin "4") (pinfunction "Y_4") (pintype "passive"))
    )
    (net (code "206") (name "/Y_B70") (class "Default")
      (node (ref "TSB116") (pin "4") (pinfunction "Y_4") (pintype "passive"))
    )
    (net (code "207") (name "/Y_B71") (class "Default")
      (node (ref "TSB123") (pin "4") (pinfunction "Y_4") (pintype "passive"))
    )
    (net (code "208") (name "/Y_B72") (class "Default")
      (node (ref "TSB5") (pin "4") (pinfunction "Y_4") (pintype "passive"))
    )
    (net (code "209") (name "/Y_B73") (class "Default")
      (node (ref "TSB12") (pin "4") (pinfunction "Y_4") (pintype "passive"))
    )
    (net (code "210") (name "/Y_B74") (class "Default")
      (node (ref "TSB19") (pin "4") (pinfunction "Y_4") (pintype "passive"))
    )
    (net (code "211") (name "/Y_B75") (class "Default")
      (node (ref "TSB26") (pin "4") (pinfunction "Y_4") (pintype "passive"))
    )
    (net (code "212") (name "/Y_B76") (class "Default")
      (node (ref "TSB33") (pin "4") (pinfunction "Y_4") (pintype "passive"))
    )
    (net (code "213") (name "/Y_B77") (class "Default")
      (node (ref "TSB40") (pin "4") (pinfunction "Y_4") (pintype "passive"))
    )
    (net (code "214") (name "/Y_B78") (class "Default")
      (node (ref "TSB47") (pin "4") (pinfunction "Y_4") (pintype "passive"))
    )
    (net (code "215") (name "/Y_B79") (class "Default")
      (node (ref "TSB54") (pin "4") (pinfunction "Y_4") (pintype "passive"))
    )
    (net (code "216") (name "/Y_B80") (class "Default")
      (node (ref "TSB61") (pin "4") (pinfunction "Y_4") (pintype "passive"))
    )
    (net (code "217") (name "/Y_B81") (class "Default")
      (node (ref "TSB68") (pin "4") (pinfunction "Y_4") (pintype "passive"))
    )
    (net (code "218") (name "/Y_B82") (class "Default")
      (node (ref "TSB75") (pin "4") (pinfunction "Y_4") (pintype "passive"))
    )
    (net (code "219") (name "/Y_B83") (class "Default")
      (node (ref "TSB82") (pin "4") (pinfunction "Y_4") (pintype "passive"))
    )
    (net (code "220") (name "/Y_B84") (class "Default")
      (node (ref "TSB89") (pin "4") (pinfunction "Y_4") (pintype "passive"))
    )
    (net (code "221") (name "/Y_B85") (class "Default")
      (node (ref "TSB96") (pin "4") (pinfunction "Y_4") (pintype "passive"))
    )
    (net (code "222") (name "/Y_B86") (class "Default")
      (node (ref "TSB103") (pin "4") (pinfunction "Y_4") (pintype "passive"))
    )
    (net (code "223") (name "/Y_B87") (class "Default")
      (node (ref "TSB110") (pin "4") (pinfunction "Y_4") (pintype "passive"))
    )
    (net (code "224") (name "/Y_B88") (class "Default")
      (node (ref "TSB117") (pin "4") (pinfunction "Y_4") (pintype "passive"))
    )
    (net (code "225") (name "/Y_B89") (class "Default")
      (node (ref "TSB124") (pin "4") (pinfunction "Y_4") (pintype "passive"))
    )
    (net (code "226") (name "/Y_B90") (class "Default")
      (node (ref "TSB6") (pin "4") (pinfunction "Y_4") (pintype "passive"))
    )
    (net (code "227") (name "/Y_B91") (class "Default")
      (node (ref "TSB13") (pin "4") (pinfunction "Y_4") (pintype "passive"))
    )
    (net (code "228") (name "/Y_B92") (class "Default")
      (node (ref "TSB20") (pin "4") (pinfunction "Y_4") (pintype "passive"))
    )
    (net (code "229") (name "/Y_B93") (class "Default")
      (node (ref "TSB27") (pin "4") (pinfunction "Y_4") (pintype "passive"))
    )
    (net (code "230") (name "/Y_B94") (class "Default")
      (node (ref "TSB34") (pin "4") (pinfunction "Y_4") (pintype "passive"))
    )
    (net (code "231") (name "/Y_B95") (class "Default")
      (node (ref "TSB41") (pin "4") (pinfunction "Y_4") (pintype "passive"))
    )
    (net (code "232") (name "/Y_B96") (class "Default")
      (node (ref "TSB48") (pin "4") (pinfunction "Y_4") (pintype "passive"))
    )
    (net (code "233") (name "/Y_B97") (class "Default")
      (node (ref "TSB55") (pin "4") (pinfunction "Y_4") (pintype "passive"))
    )
    (net (code "234") (name "/Y_B98") (class "Default")
      (node (ref "TSB62") (pin "4") (pinfunction "Y_4") (pintype "passive"))
    )
    (net (code "235") (name "/Y_B99") (class "Default")
      (node (ref "TSB69") (pin "4") (pinfunction "Y_4") (pintype "passive"))
    )
    (net (code "236") (name "/Y_B100") (class "Default")
      (node (ref "TSB76") (pin "4") (pinfunction "Y_4") (pintype "passive"))
    )
    (net (code "237") (name "/Y_B101") (class "Default")
      (node (ref "TSB83") (pin "4") (pinfunction "Y_4") (pintype "passive"))
    )
    (net (code "238") (name "/Y_B102") (class "Default")
      (node (ref "TSB90") (pin "4") (pinfunction "Y_4") (pintype "passive"))
    )
    (net (code "239") (name "/Y_B103") (class "Default")
      (node (ref "TSB97") (pin "4") (pinfunction "Y_4") (pintype "passive"))
    )
    (net (code "240") (name "/Y_B104") (class "Default")
      (node (ref "TSB104") (pin "4") (pinfunction "Y_4") (pintype "passive"))
    )
    (net (code "241") (name "/Y_B105") (class "Default")
      (node (ref "TSB111") (pin "4") (pinfunction "Y_4") (pintype "passive"))
    )
    (net (code "242") (name "/Y_B106") (class "Default")
      (node (ref "TSB118") (pin "4") (pinfunction "Y_4") (pintype "passive"))
    )
    (net (code "243") (name "/Y_B107") (class "Default")
      (node (ref "TSB125") (pin "4") (pinfunction "Y_4") (pintype "passive"))
    )
    (net (code "244") (name "/Y_B108") (class "Default")
      (node (ref "TSB7") (pin "4") (pinfunction "Y_4") (pintype "passive"))
    )
    (net (code "245") (name "/Y_B109") (class "Default")
      (node (ref "TSB14") (pin "4") (pinfunction "Y_4") (pintype "passive"))
    )
    (net (code "246") (name "/Y_B110") (class "Default")
      (node (ref "TSB21") (pin "4") (pinfunction "Y_4") (pintype "passive"))
    )
    (net (code "247") (name "/Y_B111") (class "Default")
      (node (ref "TSB28") (pin "4") (pinfunction "Y_4") (pintype "passive"))
    )
    (net (code "248") (name "/Y_B112") (class "Default")
      (node (ref "TSB35") (pin "4") (pinfunction "Y_4") (pintype "passive"))
    )
    (net (code "249") (name "/Y_B113") (class "Default")
      (node (ref "TSB42") (pin "4") (pinfunction "Y_4") (pintype "passive"))
    )
    (net (code "250") (name "/Y_B114") (class "Default")
      (node (ref "TSB49") (pin "4") (pinfunction "Y_4") (pintype "passive"))
    )
    (net (code "251") (name "/Y_B115") (class "Default")
      (node (ref "TSB56") (pin "4") (pinfunction "Y_4") (pintype "passive"))
    )
    (net (code "252") (name "/Y_B116") (class "Default")
      (node (ref "TSB63") (pin "4") (pinfunction "Y_4") (pintype "passive"))
    )
    (net (code "253") (name "/Y_B117") (class "Default")
      (node (ref "TSB70") (pin "4") (pinfunction "Y_4") (pintype "passive"))
    )
    (net (code "254") (name "/Y_B118") (class "Default")
      (node (ref "TSB77") (pin "4") (pinfunction "Y_4") (pintype "passive"))
    )
    (net (code "255") (name "/Y_B119") (class "Default")
      (node (ref "TSB84") (pin "4") (pinfunction "Y_4") (pintype "passive"))
    )
    (net (code "256") (name "/Y_B120") (class "Default")
      (node (ref "TSB91") (pin "4") (pinfunction "Y_4") (pintype "passive"))
    )
    (net (code "257") (name "/Y_B121") (class "Default")
      (node (ref "TSB98") (pin "4") (pinfunction "Y_4") (pintype "passive"))
    )
    (net (code "258") (name "/Y_B122") (class "Default")
      (node (ref "TSB105") (pin "4") (pinfunction "Y_4") (pintype "passive"))
    )
    (net (code "259") (name "/Y_B123") (class "Default")
      (node (ref "TSB112") (pin "4") (pinfunction "Y_4") (pintype "passive"))
    )
    (net (code "260") (name "/Y_B124") (class "Default")
      (node (ref "TSB119") (pin "4") (pinfunction "Y_4") (pintype "passive"))
    )
    (net (code "261") (name "/Y_B125") (class "Default")
      (node (ref "TSB126") (pin "4") (pinfunction "Y_4") (pintype "passive"))
    )
    (net (code "262") (name "/Y_B126") (class "Default")
      (node (ref "TSB127") (pin "4") (pinfunction "Y_4") (pintype "passive"))
    )
    (net (code "263") (name "/Y_B127") (class "Default")
      (node (ref "TSB128") (pin "4") (pinfunction "Y_4") (pintype "passive"))
    )
    (net (code "272") (name "/~OE_B0") (class "Default")
      (node (ref "TSB1") (pin "1") (pinfunction "~OE_1") (pintype "passive"))
    )
    (net (code "273") (name "/~OE_B1") (class "Default")
      (node (ref "TSB8") (pin "1") (pinfunction "~OE_1") (pintype "passive"))
    )
    (net (code "274") (name "/~OE_B2") (class "Default")
      (node (ref "TSB15") (pin "1") (pinfunction "~OE_1") (pintype "passive"))
    )
    (net (code "275") (name "/~OE_B3") (class "Default")
      (node (ref "TSB22") (pin "1") (pinfunction "~OE_1") (pintype "passive"))
    )
    (net (code "276") (name "/~OE_B4") (class "Default")
      (node (ref "TSB29") (pin "1") (pinfunction "~OE_1") (pintype "passive"))
    )
    (net (code "277") (name "/~OE_B5") (class "Default")
      (node (ref "TSB36") (pin "1") (pinfunction "~OE_1") (pintype "passive"))
    )
    (net (code "278") (name "/~OE_B6") (class "Default")
      (node (ref "TSB43") (pin "1") (pinfunction "~OE_1") (pintype "passive"))
    )
    (net (code "279") (name "/~OE_B7") (class "Default")
      (node (ref "TSB50") (pin "1") (pinfunction "~OE_1") (pintype "passive"))
    )
    (net (code "280") (name "/~OE_B8") (class "Default")
      (node (ref "TSB57") (pin "1") (pinfunction "~OE_1") (pintype "passive"))
    )
    (net (code "281") (name "/~OE_B9") (class "Default")
      (node (ref "TSB64") (pin "1") (pinfunction "~OE_1") (pintype "passive"))
    )
    (net (code "282") (name "/~OE_B10") (class "Default")
      (node (ref "TSB71") (pin "1") (pinfunction "~OE_1") (pintype "passive"))
    )
    (net (code "283") (name "/~OE_B11") (class "Default")
      (node (ref "TSB78") (pin "1") (pinfunction "~OE_1") (pintype "passive"))
    )
    (net (code "284") (name "/~OE_B12") (class "Default")
      (node (ref "TSB85") (pin "1") (pinfunction "~OE_1") (pintype "passive"))
    )
    (net (code "285") (name "/~OE_B13") (class "Default")
      (node (ref "TSB92") (pin "1") (pinfunction "~OE_1") (pintype "passive"))
    )
    (net (code "286") (name "/~OE_B14") (class "Default")
      (node (ref "TSB99") (pin "1") (pinfunction "~OE_1") (pintype "passive"))
    )
    (net (code "287") (name "/~OE_B15") (class "Default")
      (node (ref "TSB106") (pin "1") (pinfunction "~OE_1") (pintype "passive"))
    )
    (net (code "288") (name "/~OE_B16") (class "Default")
      (node (ref "TSB113") (pin "1") (pinfunction "~OE_1") (pintype "passive"))
    )
    (net (code "289") (name "/~OE_B17") (class "Default")
      (node (ref "TSB120") (pin "1") (pinfunction "~OE_1") (pintype "passive"))
    )
    (net (code "290") (name "/~OE_B18") (class "Default")
      (node (ref "TSB2") (pin "1") (pinfunction "~OE_1") (pintype "passive"))
    )
    (net (code "291") (name "/~OE_B19") (class "Default")
      (node (ref "TSB9") (pin "1") (pinfunction "~OE_1") (pintype "passive"))
    )
    (net (code "292") (name "/~OE_B20") (class "Default")
      (node (ref "TSB16") (pin "1") (pinfunction "~OE_1") (pintype "passive"))
    )
    (net (code "293") (name "/~OE_B21") (class "Default")
      (node (ref "TSB23") (pin "1") (pinfunction "~OE_1") (pintype "passive"))
    )
    (net (code "294") (name "/~OE_B22") (class "Default")
      (node (ref "TSB30") (pin "1") (pinfunction "~OE_1") (pintype "passive"))
    )
    (net (code "295") (name "/~OE_B23") (class "Default")
      (node (ref "TSB37") (pin "1") (pinfunction "~OE_1") (pintype "passive"))
    )
    (net (code "296") (name "/~OE_B24") (class "Default")
      (node (ref "TSB44") (pin "1") (pinfunction "~OE_1") (pintype "passive"))
    )
    (net (code "297") (name "/~OE_B25") (class "Default")
      (node (ref "TSB51") (pin "1") (pinfunction "~OE_1") (pintype "passive"))
    )
    (net (code "298") (name "/~OE_B26") (class "Default")
      (node (ref "TSB58") (pin "1") (pinfunction "~OE_1") (pintype "passive"))
    )
    (net (code "299") (name "/~OE_B27") (class "Default")
      (node (ref "TSB65") (pin "1") (pinfunction "~OE_1") (pintype "passive"))
    )
    (net (code "300") (name "/~OE_B28") (class "Default")
      (node (ref "TSB72") (pin "1") (pinfunction "~OE_1") (pintype "passive"))
    )
    (net (code "301") (name "/~OE_B29") (class "Default")
      (node (ref "TSB79") (pin "1") (pinfunction "~OE_1") (pintype "passive"))
    )
    (net (code "302") (name "/~OE_B30") (class "Default")
      (node (ref "TSB86") (pin "1") (pinfunction "~OE_1") (pintype "passive"))
    )
    (net (code "303") (name "/~OE_B31") (class "Default")
      (node (ref "TSB93") (pin "1") (pinfunction "~OE_1") (pintype "passive"))
    )
    (net (code "304") (name "/~OE_B32") (class "Default")
      (node (ref "TSB100") (pin "1") (pinfunction "~OE_1") (pintype "passive"))
    )
    (net (code "305") (name "/~OE_B33") (class "Default")
      (node (ref "TSB107") (pin "1") (pinfunction "~OE_1") (pintype "passive"))
    )
    (net (code "306") (name "/~OE_B34") (class "Default")
      (node (ref "TSB114") (pin "1") (pinfunction "~OE_1") (pintype "passive"))
    )
    (net (code "307") (name "/~OE_B35") (class "Default")
      (node (ref "TSB121") (pin "1") (pinfunction "~OE_1") (pintype "passive"))
    )
    (net (code "308") (name "/~OE_B36") (class "Default")
      (node (ref "TSB3") (pin "1") (pinfunction "~OE_1") (pintype "passive"))
    )
    (net (code "309") (name "/~OE_B37") (class "Default")
      (node (ref "TSB10") (pin "1") (pinfunction "~OE_1") (pintype "passive"))
    )
    (net (code "310") (name "/~OE_B38") (class "Default")
      (node (ref "TSB17") (pin "1") (pinfunction "~OE_1") (pintype "passive"))
    )
    (net (code "311") (name "/~OE_B39") (class "Default")
      (node (ref "TSB24") (pin "1") (pinfunction "~OE_1") (pintype "passive"))
    )
    (net (code "312") (name "/~OE_B40") (class "Default")
      (node (ref "TSB31") (pin "1") (pinfunction "~OE_1") (pintype "passive"))
    )
    (net (code "313") (name "/~OE_B41") (class "Default")
      (node (ref "TSB38") (pin "1") (pinfunction "~OE_1") (pintype "passive"))
    )
    (net (code "314") (name "/~OE_B42") (class "Default")
      (node (ref "TSB45") (pin "1") (pinfunction "~OE_1") (pintype "passive"))
    )
    (net (code "315") (name "/~OE_B43") (class "Default")
      (node (ref "TSB52") (pin "1") (pinfunction "~OE_1") (pintype "passive"))
    )
    (net (code "316") (name "/~OE_B44") (class "Default")
      (node (ref "TSB59") (pin "1") (pinfunction "~OE_1") (pintype "passive"))
    )
    (net (code "317") (name "/~OE_B45") (class "Default")
      (node (ref "TSB66") (pin "1") (pinfunction "~OE_1") (pintype "passive"))
    )
    (net (code "318") (name "/~OE_B46") (class "Default")
      (node (ref "TSB73") (pin "1") (pinfunction "~OE_1") (pintype "passive"))
    )
    (net (code "319") (name "/~OE_B47") (class "Default")
      (node (ref "TSB80") (pin "1") (pinfunction "~OE_1") (pintype "passive"))
    )
    (net (code "320") (name "/~OE_B48") (class "Default")
      (node (ref "TSB87") (pin "1") (pinfunction "~OE_1") (pintype "passive"))
    )
    (net (code "321") (name "/~OE_B49") (class "Default")
      (node (ref "TSB94") (pin "1") (pinfunction "~OE_1") (pintype "passive"))
    )
    (net (code "322") (name "/~OE_B50") (class "Default")
      (node (ref "TSB101") (pin "1") (pinfunction "~OE_1") (pintype "passive"))
    )
    (net (code "323") (name "/~OE_B51") (class "Default")
      (node (ref "TSB108") (pin "1") (pinfunction "~OE_1") (pintype "passive"))
    )
    (net (code "324") (name "/~OE_B52") (class "Default")
      (node (ref "TSB115") (pin "1") (pinfunction "~OE_1") (pintype "passive"))
    )
    (net (code "325") (name "/~OE_B53") (class "Default")
      (node (ref "TSB122") (pin "1") (pinfunction "~OE_1") (pintype "passive"))
    )
    (net (code "326") (name "/~OE_B54") (class "Default")
      (node (ref "TSB4") (pin "1") (pinfunction "~OE_1") (pintype "passive"))
    )
    (net (code "327") (name "/~OE_B55") (class "Default")
      (node (ref "TSB11") (pin "1") (pinfunction "~OE_1") (pintype "passive"))
    )
    (net (code "328") (name "/~OE_B56") (class "Default")
      (node (ref "TSB18") (pin "1") (pinfunction "~OE_1") (pintype "passive"))
    )
    (net (code "329") (name "/~OE_B57") (class "Default")
      (node (ref "TSB25") (pin "1") (pinfunction "~OE_1") (pintype "passive"))
    )
    (net (code "330") (name "/~OE_B58") (class "Default")
      (node (ref "TSB32") (pin "1") (pinfunction "~OE_1") (pintype "passive"))
    )
    (net (code "331") (name "/~OE_B59") (class "Default")
      (node (ref "TSB39") (pin "1") (pinfunction "~OE_1") (pintype "passive"))
    )
    (net (code "332") (name "/~OE_B60") (class "Default")
      (node (ref "TSB46") (pin "1") (pinfunction "~OE_1") (pintype "passive"))
    )
    (net (code "333") (name "/~OE_B61") (class "Default")
      (node (ref "TSB53") (pin "1") (pinfunction "~OE_1") (pintype "passive"))
    )
    (net (code "334") (name "/~OE_B62") (class "Default")
      (node (ref "TSB60") (pin "1") (pinfunction "~OE_1") (pintype "passive"))
    )
    (net (code "335") (name "/~OE_B63") (class "Default")
      (node (ref "TSB67") (pin "1") (pinfunction "~OE_1") (pintype "passive"))
    )
    (net (code "336") (name "/~OE_B64") (class "Default")
      (node (ref "TSB74") (pin "1") (pinfunction "~OE_1") (pintype "passive"))
    )
    (net (code "337") (name "/~OE_B65") (class "Default")
      (node (ref "TSB81") (pin "1") (pinfunction "~OE_1") (pintype "passive"))
    )
    (net (code "338") (name "/~OE_B66") (class "Default")
      (node (ref "TSB88") (pin "1") (pinfunction "~OE_1") (pintype "passive"))
    )
    (net (code "339") (name "/~OE_B67") (class "Default")
      (node (ref "TSB95") (pin "1") (pinfunction "~OE_1") (pintype "passive"))
    )
    (net (code "340") (name "/~OE_B68") (class "Default")
      (node (ref "TSB102") (pin "1") (pinfunction "~OE_1") (pintype "passive"))
    )
    (net (code "341") (name "/~OE_B69") (class "Default")
      (node (ref "TSB109") (pin "1") (pinfunction "~OE_1") (pintype "passive"))
    )
    (net (code "342") (name "/~OE_B70") (class "Default")
      (node (ref "TSB116") (pin "1") (pinfunction "~OE_1") (pintype "passive"))
    )
    (net (code "343") (name "/~OE_B71") (class "Default")
      (node (ref "TSB123") (pin "1") (pinfunction "~OE_1") (pintype "passive"))
    )
    (net (code "344") (name "/~OE_B72") (class "Default")
      (node (ref "TSB5") (pin "1") (pinfunction "~OE_1") (pintype "passive"))
    )
    (net (code "345") (name "/~OE_B73") (class "Default")
      (node (ref "TSB12") (pin "1") (pinfunction "~OE_1") (pintype "passive"))
    )
    (net (code "346") (name "/~OE_B74") (class "Default")
      (node (ref "TSB19") (pin "1") (pinfunction "~OE_1") (pintype "passive"))
    )
    (net (code "347") (name "/~OE_B75") (class "Default")
      (node (ref "TSB26") (pin "1") (pinfunction "~OE_1") (pintype "passive"))
    )
    (net (code "348") (name "/~OE_B76") (class "Default")
      (node (ref "TSB33") (pin "1") (pinfunction "~OE_1") (pintype "passive"))
    )
    (net (code "349") (name "/~OE_B77") (class "Default")
      (node (ref "TSB40") (pin "1") (pinfunction "~OE_1") (pintype "passive"))
    )
    (net (code "350") (name "/~OE_B78") (class "Default")
      (node (ref "TSB47") (pin "1") (pinfunction "~OE_1") (pintype "passive"))
    )
    (net (code "351") (name "/~OE_B79") (class "Default")
      (node (ref "TSB54") (pin "1") (pinfunction "~OE_1") (pintype "passive"))
    )
    (net (code "352") (name "/~OE_B80") (class "Default")
      (node (ref "TSB61") (pin "1") (pinfunction "~OE_1") (pintype "passive"))
    )
    (net (code "353") (name "/~OE_B81") (class "Default")
      (node (ref "TSB68") (pin "1") (pinfunction "~OE_1") (pintype "passive"))
    )
    (net (code "354") (name "/~OE_B82") (class "Default")
      (node (ref "TSB75") (pin "1") (pinfunction "~OE_1") (pintype "passive"))
    )
    (net (code "355") (name "/~OE_B83") (class "Default")
      (node (ref "TSB82") (pin "1") (pinfunction "~OE_1") (pintype "passive"))
    )
    (net (code "356") (name "/~OE_B84") (class "Default")
      (node (ref "TSB89") (pin "1") (pinfunction "~OE_1") (pintype "passive"))
    )
    (net (code "357") (name "/~OE_B85") (class "Default")
      (node (ref "TSB96") (pin "1") (pinfunction "~OE_1") (pintype "passive"))
    )
    (net (code "358") (name "/~OE_B86") (class "Default")
      (node (ref "TSB103") (pin "1") (pinfunction "~OE_1") (pintype "passive"))
    )
    (net (code "359") (name "/~OE_B87") (class "Default")
      (node (ref "TSB110") (pin "1") (pinfunction "~OE_1") (pintype "passive"))
    )
    (net (code "360") (name "/~OE_B88") (class "Default")
      (node (ref "TSB117") (pin "1") (pinfunction "~OE_1") (pintype "passive"))
    )
    (net (code "361") (name "/~OE_B89") (class "Default")
      (node (ref "TSB124") (pin "1") (pinfunction "~OE_1") (pintype "passive"))
    )
    (net (code "362") (name "/~OE_B90") (class "Default")
      (node (ref "TSB6") (pin "1") (pinfunction "~OE_1") (pintype "passive"))
    )
    (net (code "363") (name "/~OE_B91") (class "Default")
      (node (ref "TSB13") (pin "1") (pinfunction "~OE_1") (pintype "passive"))
    )
    (net (code "364") (name "/~OE_B92") (class "Default")
      (node (ref "TSB20") (pin "1") (pinfunction "~OE_1") (pintype "passive"))
    )
    (net (code "365") (name "/~OE_B93") (class "Default")
      (node (ref "TSB27") (pin "1") (pinfunction "~OE_1") (pintype "passive"))
    )
    (net (code "366") (name "/~OE_B94") (class "Default")
      (node (ref "TSB34") (pin "1") (pinfunction "~OE_1") (pintype "passive"))
    )
    (net (code "367") (name "/~OE_B95") (class "Default")
      (node (ref "TSB41") (pin "1") (pinfunction "~OE_1") (pintype "passive"))
    )
    (net (code "368") (name "/~OE_B96") (class "Default")
      (node (ref "TSB48") (pin "1") (pinfunction "~OE_1") (pintype "passive"))
    )
    (net (code "369") (name "/~OE_B97") (class "Default")
      (node (ref "TSB55") (pin "1") (pinfunction "~OE_1") (pintype "passive"))
    )
    (net (code "370") (name "/~OE_B98") (class "Default")
      (node (ref "TSB62") (pin "1") (pinfunction "~OE_1") (pintype "passive"))
    )
    (net (code "371") (name "/~OE_B99") (class "Default")
      (node (ref "TSB69") (pin "1") (pinfunction "~OE_1") (pintype "passive"))
    )
    (net (code "372") (name "/~OE_B100") (class "Default")
      (node (ref "TSB76") (pin "1") (pinfunction "~OE_1") (pintype "passive"))
    )
    (net (code "373") (name "/~OE_B101") (class "Default")
      (node (ref "TSB83") (pin "1") (pinfunction "~OE_1") (pintype "passive"))
    )
    (net (code "374") (name "/~OE_B102") (class "Default")
      (node (ref "TSB90") (pin "1") (pinfunction "~OE_1") (pintype "passive"))
    )
    (net (code "375") (name "/~OE_B103") (class "Default")
      (node (ref "TSB97") (pin "1") (pinfunction "~OE_1") (pintype "passive"))
    )
    (net (code "376") (name "/~OE_B104") (class "Default")
      (node (ref "TSB104") (pin "1") (pinfunction "~OE_1") (pintype "passive"))
    )
    (net (code "377") (name "/~OE_B105") (class "Default")
      (node (ref "TSB111") (pin "1") (pinfunction "~OE_1") (pintype "passive"))
    )
    (net (code "378") (name "/~OE_B106") (class "Default")
      (node (ref "TSB118") (pin "1") (pinfunction "~OE_1") (pintype "passive"))
    )
    (net (code "379") (name "/~OE_B107") (class "Default")
      (node (ref "TSB125") (pin "1") (pinfunction "~OE_1") (pintype "passive"))
    )
    (net (code "380") (name "/~OE_B108") (class "Default")
      (node (ref "TSB7") (pin "1") (pinfunction "~OE_1") (pintype "passive"))
    )
    (net (code "381") (name "/~OE_B109") (class "Default")
      (node (ref "TSB14") (pin "1") (pinfunction "~OE_1") (pintype "passive"))
    )
    (net (code "382") (name "/~OE_B110") (class "Default")
      (node (ref "TSB21") (pin "1") (pinfunction "~OE_1") (pintype "passive"))
    )
    (net (code "383") (name "/~OE_B111") (class "Default")
      (node (ref "TSB28") (pin "1") (pinfunction "~OE_1") (pintype "passive"))
    )
    (net (code "384") (name "/~OE_B112") (class "Default")
      (node (ref "TSB35") (pin "1") (pinfunction "~OE_1") (pintype "passive"))
    )
    (net (code "385") (name "/~OE_B113") (class "Default")
      (node (ref "TSB42") (pin "1") (pinfunction "~OE_1") (pintype "passive"))
    )
    (net (code "386") (name "/~OE_B114") (class "Default")
      (node (ref "TSB49") (pin "1") (pinfunction "~OE_1") (pintype "passive"))
    )
    (net (code "387") (name "/~OE_B115") (class "Default")
      (node (ref "TSB56") (pin "1") (pinfunction "~OE_1") (pintype "passive"))
    )
    (net (code "388") (name "/~OE_B116") (class "Default")
      (node (ref "TSB63") (pin "1") (pinfunction "~OE_1") (pintype "passive"))
    )
    (net (code "389") (name "/~OE_B117") (class "Default")
      (node (ref "TSB70") (pin "1") (pinfunction "~OE_1") (pintype "passive"))
    )
    (net (code "390") (name "/~OE_B118") (class "Default")
      (node (ref "TSB77") (pin "1") (pinfunction "~OE_1") (pintype "passive"))
    )
    (net (code "391") (name "/~OE_B119") (class "Default")
      (node (ref "TSB84") (pin "1") (pinfunction "~OE_1") (pintype "passive"))
    )
    (net (code "392") (name "/~OE_B120") (class "Default")
      (node (ref "TSB91") (pin "1") (pinfunction "~OE_1") (pintype "passive"))
    )
    (net (code "393") (name "/~OE_B121") (class "Default")
      (node (ref "TSB98") (pin "1") (pinfunction "~OE_1") (pintype "passive"))
    )
    (net (code "394") (name "/~OE_B122") (class "Default")
      (node (ref "TSB105") (pin "1") (pinfunction "~OE_1") (pintype "passive"))
    )
    (net (code "395") (name "/~OE_B123") (class "Default")
      (node (ref "TSB112") (pin "1") (pinfunction "~OE_1") (pintype "passive"))
    )
    (net (code "396") (name "/~OE_B124") (class "Default")
      (node (ref "TSB119") (pin "1") (pinfunction "~OE_1") (pintype "passive"))
    )
    (net (code "397") (name "/~OE_B125") (class "Default")
      (node (ref "TSB126") (pin "1") (pinfunction "~OE_1") (pintype "passive"))
    )
    (net (code "398") (name "/~OE_B126") (class "Default")
      (node (ref "TSB127") (pin "1") (pinfunction "~OE_1") (pintype "passive"))
    )
    (net (code "399") (name "/~OE_B127") (class "Default")
      (node (ref "TSB128") (pin "1") (pinfunction "~OE_1") (pintype "passive"))
    )
    (net (code "408") (name "GND") (class "Default")
      (node (ref "TSB1") (pin "3") (pinfunction "GND_3") (pintype "passive"))
      (node (ref "TSB10") (pin "3") (pinfunction "GND_3") (pintype "passive"))
      (node (ref "TSB100") (pin "3") (pinfunction "GND_3") (pintype "passive"))
      (node (ref "TSB101") (pin "3") (pinfunction "GND_3") (pintype "passive"))
      (node (ref "TSB102") (pin "3") (pinfunction "GND_3") (pintype "passive"))
      (node (ref "TSB103") (pin "3") (pinfunction "GND_3") (pintype "passive"))
      (node (ref "TSB104") (pin "3") (pinfunction "GND_3") (pintype "passive"))
      (node (ref "TSB105") (pin "3") (pinfunction "GND_3") (pintype "passive"))
      (node (ref "TSB106") (pin "3") (pinfunction "GND_3") (pintype "passive"))
      (node (ref "TSB107") (pin "3") (pinfunction "GND_3") (pintype "passive"))
      (node (ref "TSB108") (pin "3") (pinfunction "GND_3") (pintype "passive"))
      (node (ref "TSB109") (pin "3") (pinfunction "GND_3") (pintype "passive"))
      (node (ref "TSB11") (pin "3") (pinfunction "GND_3") (pintype "passive"))
      (node (ref "TSB110") (pin "3") (pinfunction "GND_3") (pintype "passive"))
      (node (ref "TSB111") (pin "3") (pinfunction "GND_3") (pintype "passive"))
      (node (ref "TSB112") (pin "3") (pinfunction "GND_3") (pintype "passive"))
      (node (ref "TSB113") (pin "3") (pinfunction "GND_3") (pintype "passive"))
      (node (ref "TSB114") (pin "3") (pinfunction "GND_3") (pintype "passive"))
      (node (ref "TSB115") (pin "3") (pinfunction "GND_3") (pintype "passive"))
      (node (ref "TSB116") (pin "3") (pinfunction "GND_3") (pintype "passive"))
      (node (ref "TSB117") (pin "3") (pinfunction "GND_3") (pintype "passive"))
      (node (ref "TSB118") (pin "3") (pinfunction "GND_3") (pintype "passive"))
      (node (ref "TSB119") (pin "3") (pinfunction "GND_3") (pintype "passive"))
      (node (ref "TSB12") (pin "3") (pinfunction "GND_3") (pintype "passive"))
      (node (ref "TSB120") (pin "3") (pinfunction "GND_3") (pintype "passive"))
      (node (ref "TSB121") (pin "3") (pinfunction "GND_3") (pintype "passive"))
      (node (ref "TSB123") (pin "3") (pinfunction "GND_3") (pintype "passive"))
      (node (ref "TSB124") (pin "3") (pinfunction "GND_3") (pintype "passive"))
      (node (ref "TSB125") (pin "3") (pinfunction "GND_3") (pintype "passive"))
      (node (ref "TSB126") (pin "3") (pinfunction "GND_3") (pintype "passive"))
      (node (ref "TSB127") (pin "2") (pinfunction "A_2") (pintype "passive"))
      (node (ref "TSB127") (pin "3") (pinfunction "GND_3") (pintype "passive"))
      (node (ref "TSB128") (pin "2") (pinfunction "A_2") (pintype "passive"))
      (node (ref "TSB128") (pin "3") (pinfunction "GND_3") (pintype "passive"))
      (node (ref "TSB13") (pin "3") (pinfunction "GND_3") (pintype "passive"))
      (node (ref "TSB14") (pin "3") (pinfunction "GND_3") (pintype "passive"))
      (node (ref "TSB15") (pin "3") (pinfunction "GND_3") (pintype "passive"))
      (node (ref "TSB16") (pin "3") (pinfunction "GND_3") (pintype "passive"))
      (node (ref "TSB17") (pin "3") (pinfunction "GND_3") (pintype "passive"))
      (node (ref "TSB18") (pin "3") (pinfunction "GND_3") (pintype "passive"))
      (node (ref "TSB19") (pin "3") (pinfunction "GND_3") (pintype "passive"))
      (node (ref "TSB2") (pin "3") (pinfunction "GND_3") (pintype "passive"))
      (node (ref "TSB20") (pin "3") (pinfunction "GND_3") (pintype "passive"))
      (node (ref "TSB21") (pin "3") (pinfunction "GND_3") (pintype "passive"))
      (node (ref "TSB22") (pin "3") (pinfunction "GND_3") (pintype "passive"))
      (node (ref "TSB23") (pin "3") (pinfunction "GND_3") (pintype "passive"))
      (node (ref "TSB24") (pin "3") (pinfunction "GND_3") (pintype "passive"))
      (node (ref "TSB25") (pin "3") (pinfunction "GND_3") (pintype "passive"))
      (node (ref "TSB26") (pin "3") (pinfunction "GND_3") (pintype "passive"))
      (node (ref "TSB27") (pin "3") (pinfunction "GND_3") (pintype "passive"))
      (node (ref "TSB28") (pin "3") (pinfunction "GND_3") (pintype "passive"))
      (node (ref "TSB29") (pin "3") (pinfunction "GND_3") (pintype "passive"))
      (node (ref "TSB3") (pin "3") (pinfunction "GND_3") (pintype "passive"))
      (node (ref "TSB30") (pin "3") (pinfunction "GND_3") (pintype "passive"))
      (node (ref "TSB31") (pin "3") (pinfunction "GND_3") (pintype "passive"))
      (node (ref "TSB32") (pin "3") (pinfunction "GND_3") (pintype "passive"))
      (node (ref "TSB33") (pin "3") (pinfunction "GND_3") (pintype "passive"))
      (node (ref "TSB34") (pin "3") (pinfunction "GND_3") (pintype "passive"))
      (node (ref "TSB35") (pin "3") (pinfunction "GND_3") (pintype "passive"))
      (node (ref "TSB36") (pin "3") (pinfunction "GND_3") (pintype "passive"))
      (node (ref "TSB37") (pin "3") (pinfunction "GND_3") (pintype "passive"))
      (node (ref "TSB38") (pin "3") (pinfunction "GND_3") (pintype "passive"))
      (node (ref "TSB39") (pin "3") (pinfunction "GND_3") (pintype "passive"))
      (node (ref "TSB4") (pin "3") (pinfunction "GND_3") (pintype "passive"))
      (node (ref "TSB40") (pin "3") (pinfunction "GND_3") (pintype "passive"))
      (node (ref "TSB41") (pin "3") (pinfunction "GND_3") (pintype "passive"))
      (node (ref "TSB42") (pin "3") (pinfunction "GND_3") (pintype "passive"))
      (node (ref "TSB43") (pin "3") (pinfunction "GND_3") (pintype "passive"))
      (node (ref "TSB44") (pin "3") (pinfunction "GND_3") (pintype "passive"))
      (node (ref "TSB45") (pin "3") (pinfunction "GND_3") (pintype "passive"))
      (node (ref "TSB46") (pin "3") (pinfunction "GND_3") (pintype "passive"))
      (node (ref "TSB47") (pin "3") (pinfunction "GND_3") (pintype "passive"))
      (node (ref "TSB48") (pin "3") (pinfunction "GND_3") (pintype "passive"))
      (node (ref "TSB49") (pin "3") (pinfunction "GND_3") (pintype "passive"))
      (node (ref "TSB5") (pin "3") (pinfunction "GND_3") (pintype "passive"))
      (node (ref "TSB50") (pin "3") (pinfunction "GND_3") (pintype "passive"))
      (node (ref "TSB51") (pin "3") (pinfunction "GND_3") (pintype "passive"))
      (node (ref "TSB52") (pin "3") (pinfunction "GND_3") (pintype "passive"))
      (node (ref "TSB53") (pin "3") (pinfunction "GND_3") (pintype "passive"))
      (node (ref "TSB54") (pin "3") (pinfunction "GND_3") (pintype "passive"))
      (node (ref "TSB55") (pin "3") (pinfunction "GND_3") (pintype "passive"))
      (node (ref "TSB56") (pin "3") (pinfunction "GND_3") (pintype "passive"))
      (node (ref "TSB57") (pin "3") (pinfunction "GND_3") (pintype "passive"))
      (node (ref "TSB58") (pin "3") (pinfunction "GND_3") (pintype "passive"))
      (node (ref "TSB59") (pin "3") (pinfunction "GND_3") (pintype "passive"))
      (node (ref "TSB6") (pin "3") (pinfunction "GND_3") (pintype "passive"))
      (node (ref "TSB60") (pin "3") (pinfunction "GND_3") (pintype "passive"))
      (node (ref "TSB61") (pin "3") (pinfunction "GND_3") (pintype "passive"))
      (node (ref "TSB62") (pin "3") (pinfunction "GND_3") (pintype "passive"))
      (node (ref "TSB63") (pin "3") (pinfunction "GND_3") (pintype "passive"))
      (node (ref "TSB64") (pin "3") (pinfunction "GND_3") (pintype "passive"))
      (node (ref "TSB65") (pin "3") (pinfunction "GND_3") (pintype "passive"))
      (node (ref "TSB66") (pin "3") (pinfunction "GND_3") (pintype "passive"))
      (node (ref "TSB67") (pin "3") (pinfunction "GND_3") (pintype "passive"))
      (node (ref "TSB68") (pin "3") (pinfunction "GND_3") (pintype "passive"))
      (node (ref "TSB69") (pin "3") (pinfunction "GND_3") (pintype "passive"))
      (node (ref "TSB7") (pin "3") (pinfunction "GND_3") (pintype "passive"))
      (node (ref "TSB70") (pin "3") (pinfunction "GND_3") (pintype "passive"))
      (node (ref "TSB71") (pin "3") (pinfunction "GND_3") (pintype "passive"))
      (node (ref "TSB72") (pin "3") (pinfunction "GND_3") (pintype "passive"))
      (node (ref "TSB73") (pin "3") (pinfunction "GND_3") (pintype "passive"))
      (node (ref "TSB74") (pin "3") (pinfunction "GND_3") (pintype "passive"))
      (node (ref "TSB75") (pin "3") (pinfunction "GND_3") (pintype "passive"))
      (node (ref "TSB76") (pin "3") (pinfunction "GND_3") (pintype "passive"))
      (node (ref "TSB77") (pin "3") (pinfunction "GND_3") (pintype "passive"))
      (node (ref "TSB78") (pin "3") (pinfunction "GND_3") (pintype "passive"))
      (node (ref "TSB79") (pin "3") (pinfunction "GND_3") (pintype "passive"))
      (node (ref "TSB8") (pin "3") (pinfunction "GND_3") (pintype "passive"))
      (node (ref "TSB80") (pin "3") (pinfunction "GND_3") (pintype "passive"))
      (node (ref "TSB81") (pin "3") (pinfunction "GND_3") (pintype "passive"))
      (node (ref "TSB82") (pin "3") (pinfunction "GND_3") (pintype "passive"))
      (node (ref "TSB83") (pin "3") (pinfunction "GND_3") (pintype "passive"))
      (node (ref "TSB84") (pin "3") (pinfunction "GND_3") (pintype "passive"))
      (node (ref "TSB85") (pin "3") (pinfunction "GND_3") (pintype "passive"))
      (node (ref "TSB86") (pin "3") (pinfunction "GND_3") (pintype "passive"))
      (node (ref "TSB87") (pin "3") (pinfunction "GND_3") (pintype "passive"))
      (node (ref "TSB88") (pin "3") (pinfunction "GND_3") (pintype "passive"))
      (node (ref "TSB89") (pin "3") (pinfunction "GND_3") (pintype "passive"))
      (node (ref "TSB9") (pin "3") (pinfunction "GND_3") (pintype "passive"))
      (node (ref "TSB90") (pin "3") (pinfunction "GND_3") (pintype "passive"))
      (node (ref "TSB91") (pin "3") (pinfunction "GND_3") (pintype "passive"))
      (node (ref "TSB92") (pin "3") (pinfunction "GND_3") (pintype "passive"))
      (node (ref "TSB93") (pin "3") (pinfunction "GND_3") (pintype "passive"))
      (node (ref "TSB94") (pin "3") (pinfunction "GND_3") (pintype "passive"))
      (node (ref "TSB95") (pin "3") (pinfunction "GND_3") (pintype "passive"))
      (node (ref "TSB96") (pin "3") (pinfunction "GND_3") (pintype "passive"))
      (node (ref "TSB97") (pin "3") (pinfunction "GND_3") (pintype "passive"))
      (node (ref "TSB98") (pin "3") (pinfunction "GND_3") (pintype "passive"))
      (node (ref "TSB99") (pin "3") (pinfunction "GND_3") (pintype "passive"))
    )
    (net (code "409") (name "unconnected-(TSB120-Vcc-Pad5)") (class "Default")
      (node (ref "TSB120") (pin "5") (pinfunction "Vcc_5") (pintype "passive"))
    )
    (net (code "410") (name "unconnected-(TSB121-Vcc-Pad5)") (class "Default")
      (node (ref "TSB121") (pin "5") (pinfunction "Vcc_5") (pintype "passive"))
    )
    (net (code "411") (name "unconnected-(TSB122-GND-Pad3)") (class "Default")
      (node (ref "TSB122") (pin "3") (pinfunction "GND_3") (pintype "passive"))
    )
    (net (code "412") (name "unconnected-(TSB122-Vcc-Pad5)") (class "Default")
      (node (ref "TSB122") (pin "5") (pinfunction "Vcc_5") (pintype "passive"))
    )
    (net (code "413") (name "unconnected-(TSB123-Vcc-Pad5)") (class "Default")
      (node (ref "TSB123") (pin "5") (pinfunction "Vcc_5") (pintype "passive"))
    )
    (net (code "414") (name "unconnected-(TSB124-Vcc-Pad5)") (class "Default")
      (node (ref "TSB124") (pin "5") (pinfunction "Vcc_5") (pintype "passive"))
    )
    (net (code "415") (name "unconnected-(TSB125-Vcc-Pad5)") (class "Default")
      (node (ref "TSB125") (pin "5") (pinfunction "Vcc_5") (pintype "passive"))
    )
    (net (code "416") (name "unconnected-(TSB127-Vcc-Pad5)") (class "Default")
      (node (ref "TSB127") (pin "5") (pinfunction "Vcc_5") (pintype "passive"))
    )
    (net (code "417") (name "unconnected-(TSB128-Vcc-Pad5)") (class "Default")
      (node (ref "TSB128") (pin "5") (pinfunction "Vcc_5") (pintype "passive"))
    )
  )
)
